# PixHawk_Fire_v1_6.net
KiCad netlist of a schematic drawn in EAGLE
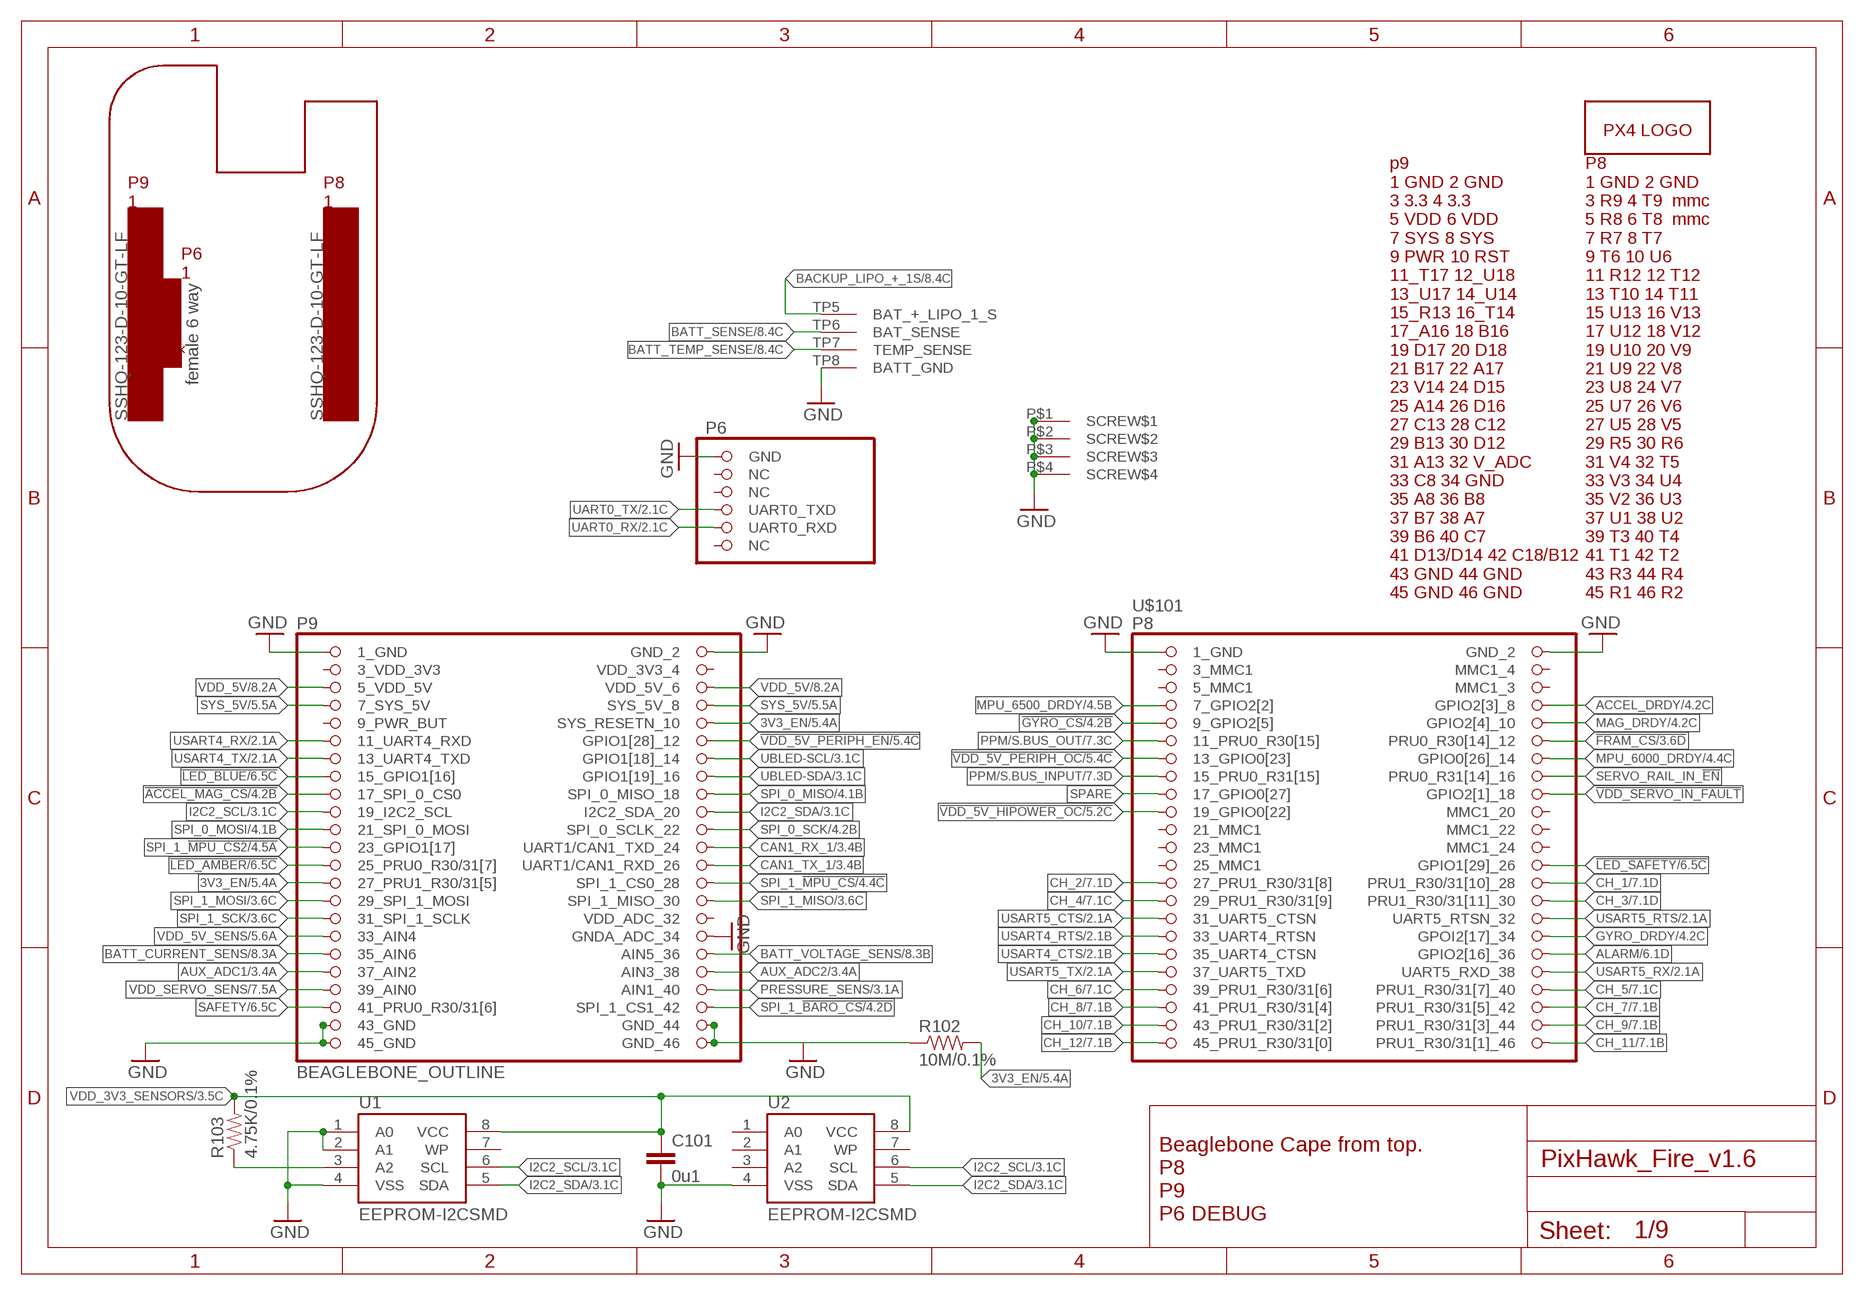
[diagram p0: schematic, sheet 1]
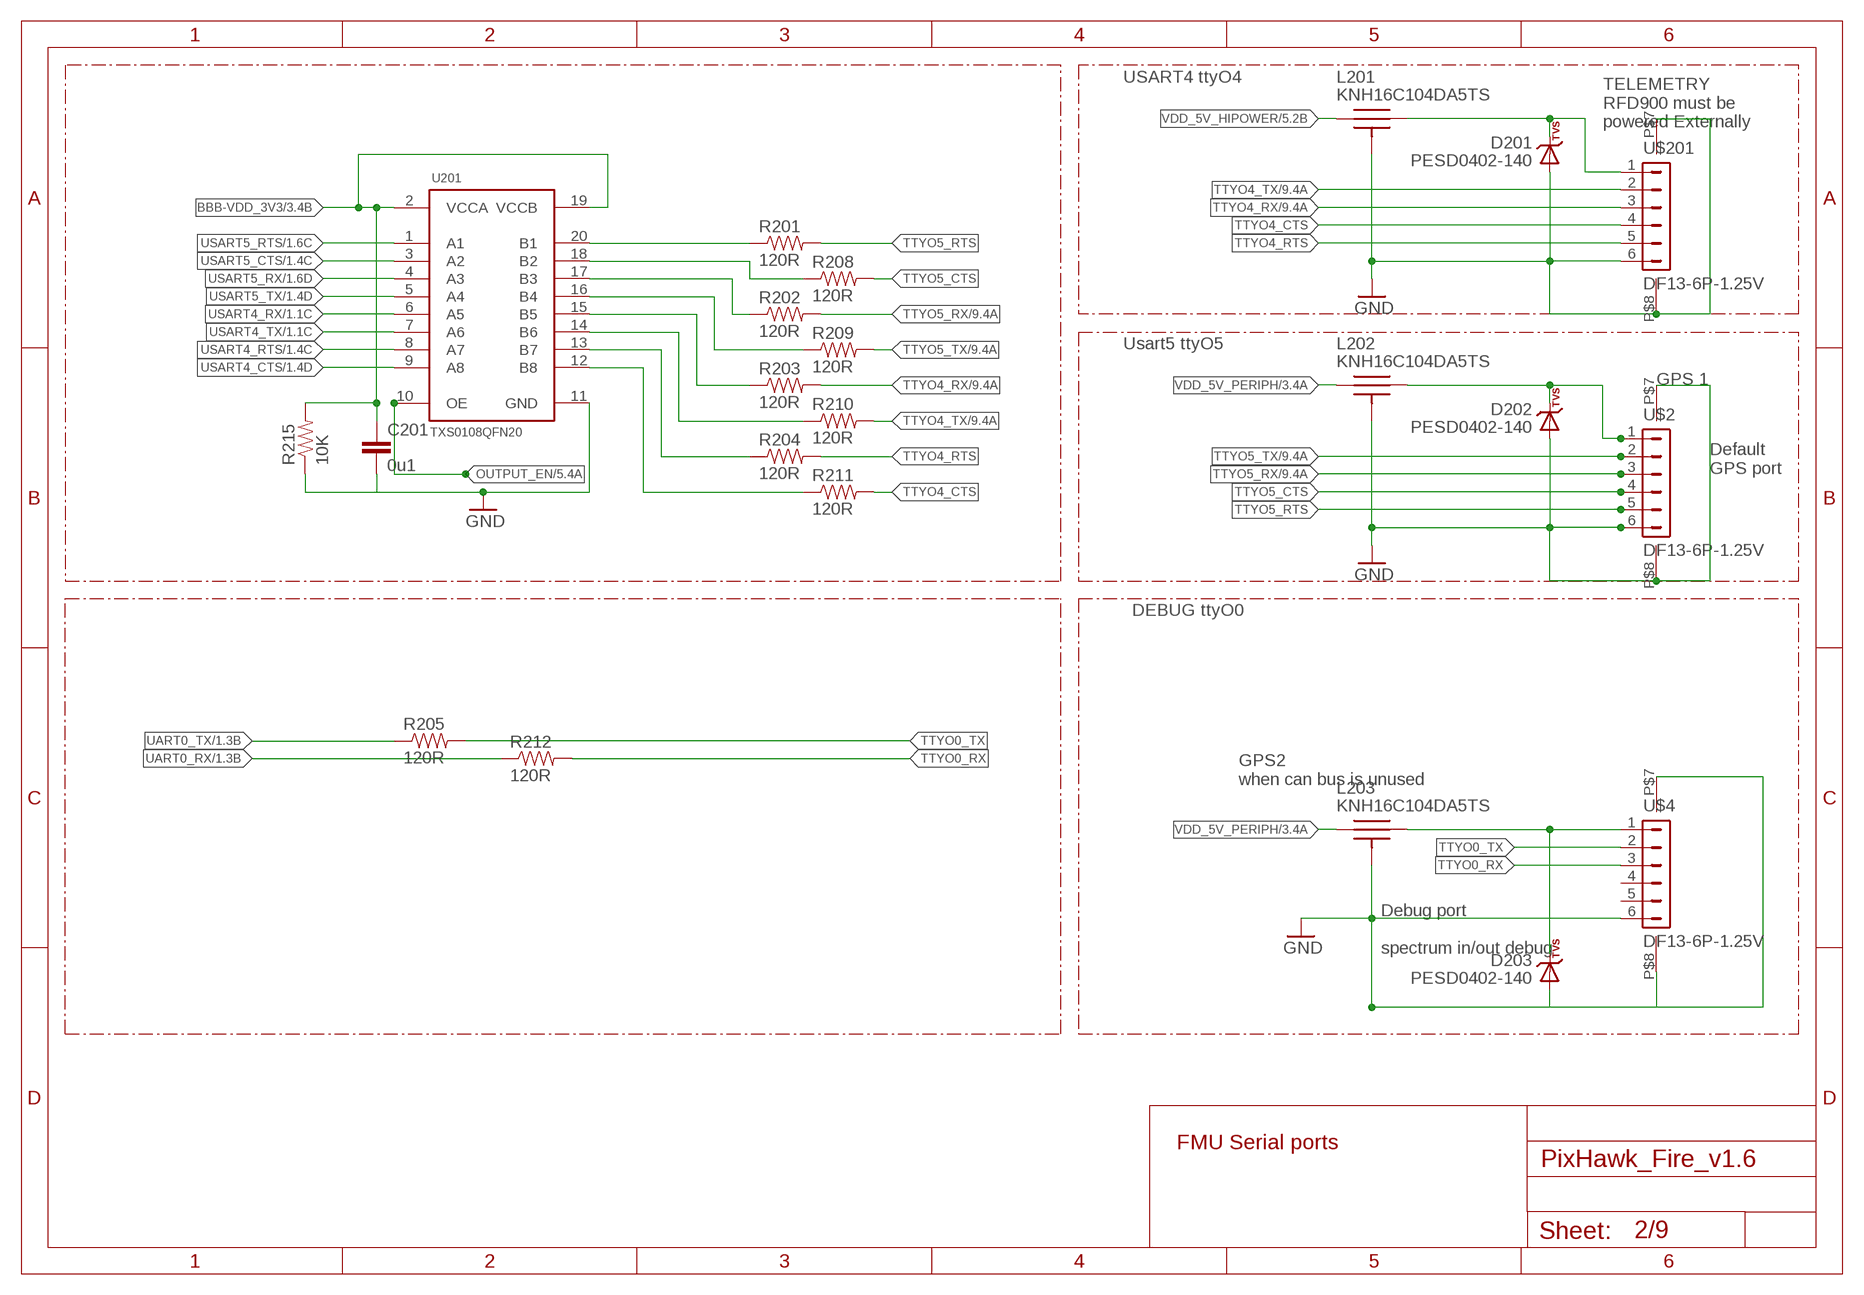
[diagram p1: schematic, sheet 2]
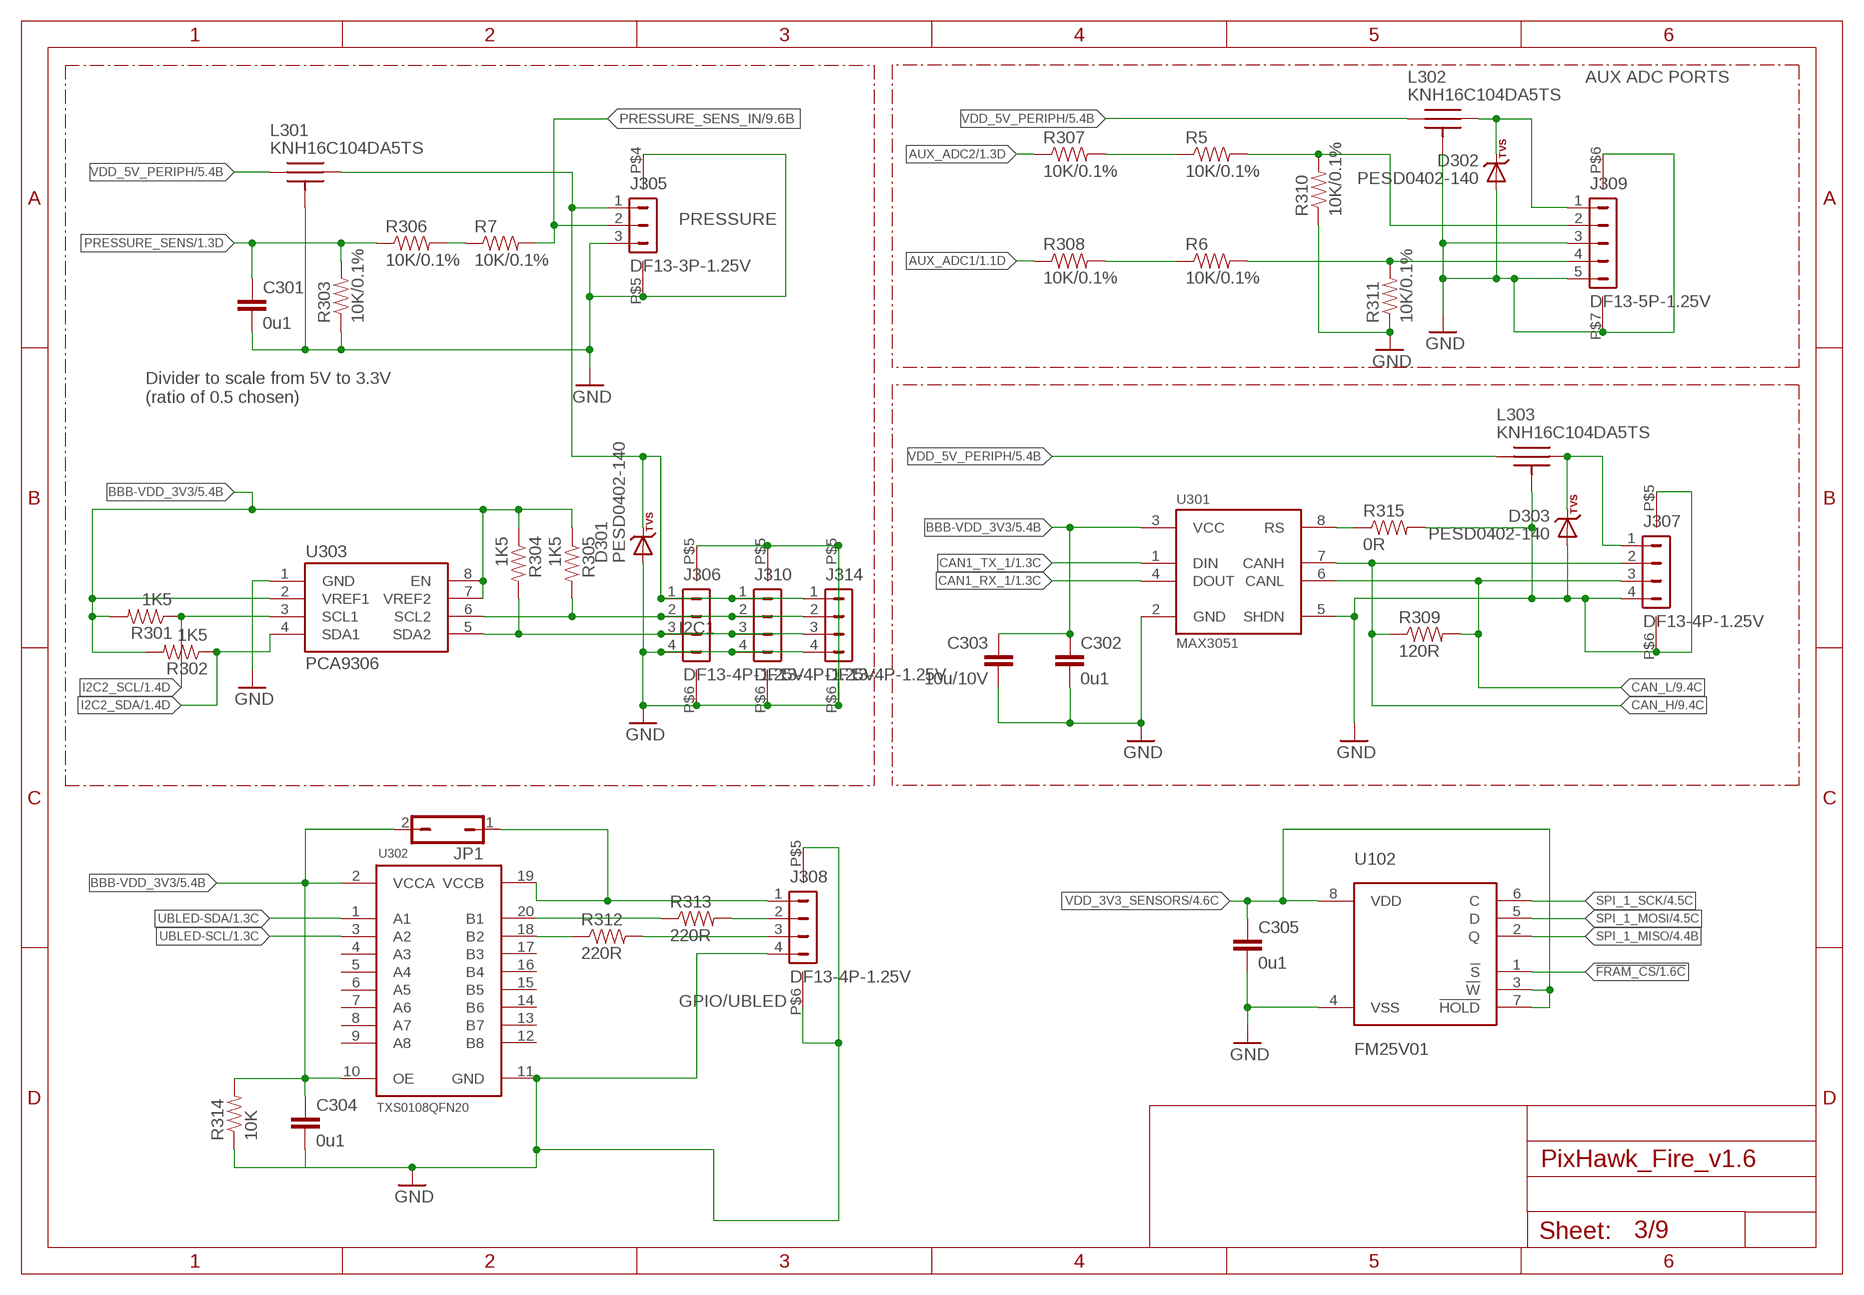
[diagram p2: schematic, sheet 3]
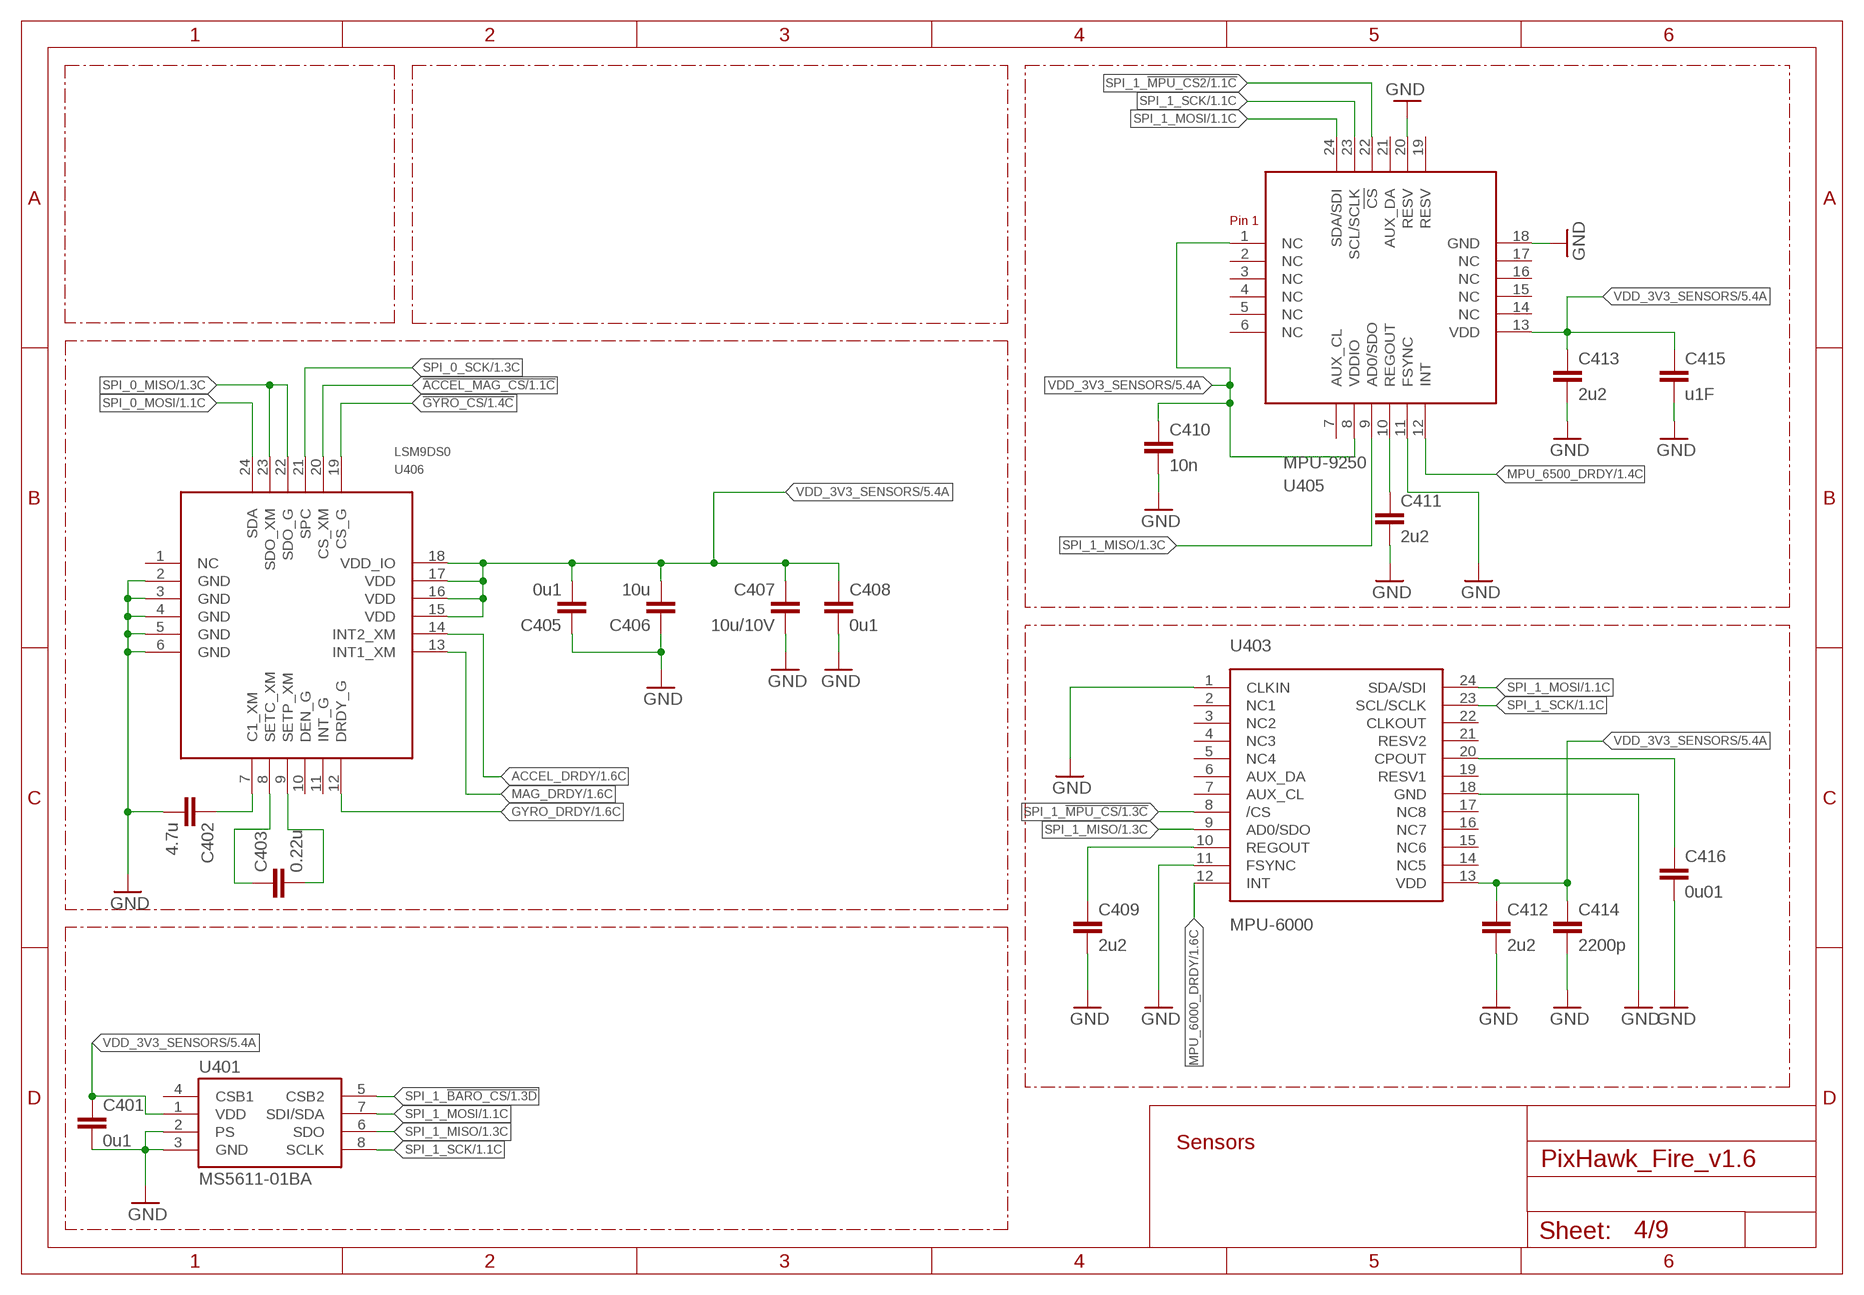
[diagram p3: schematic, sheet 4]
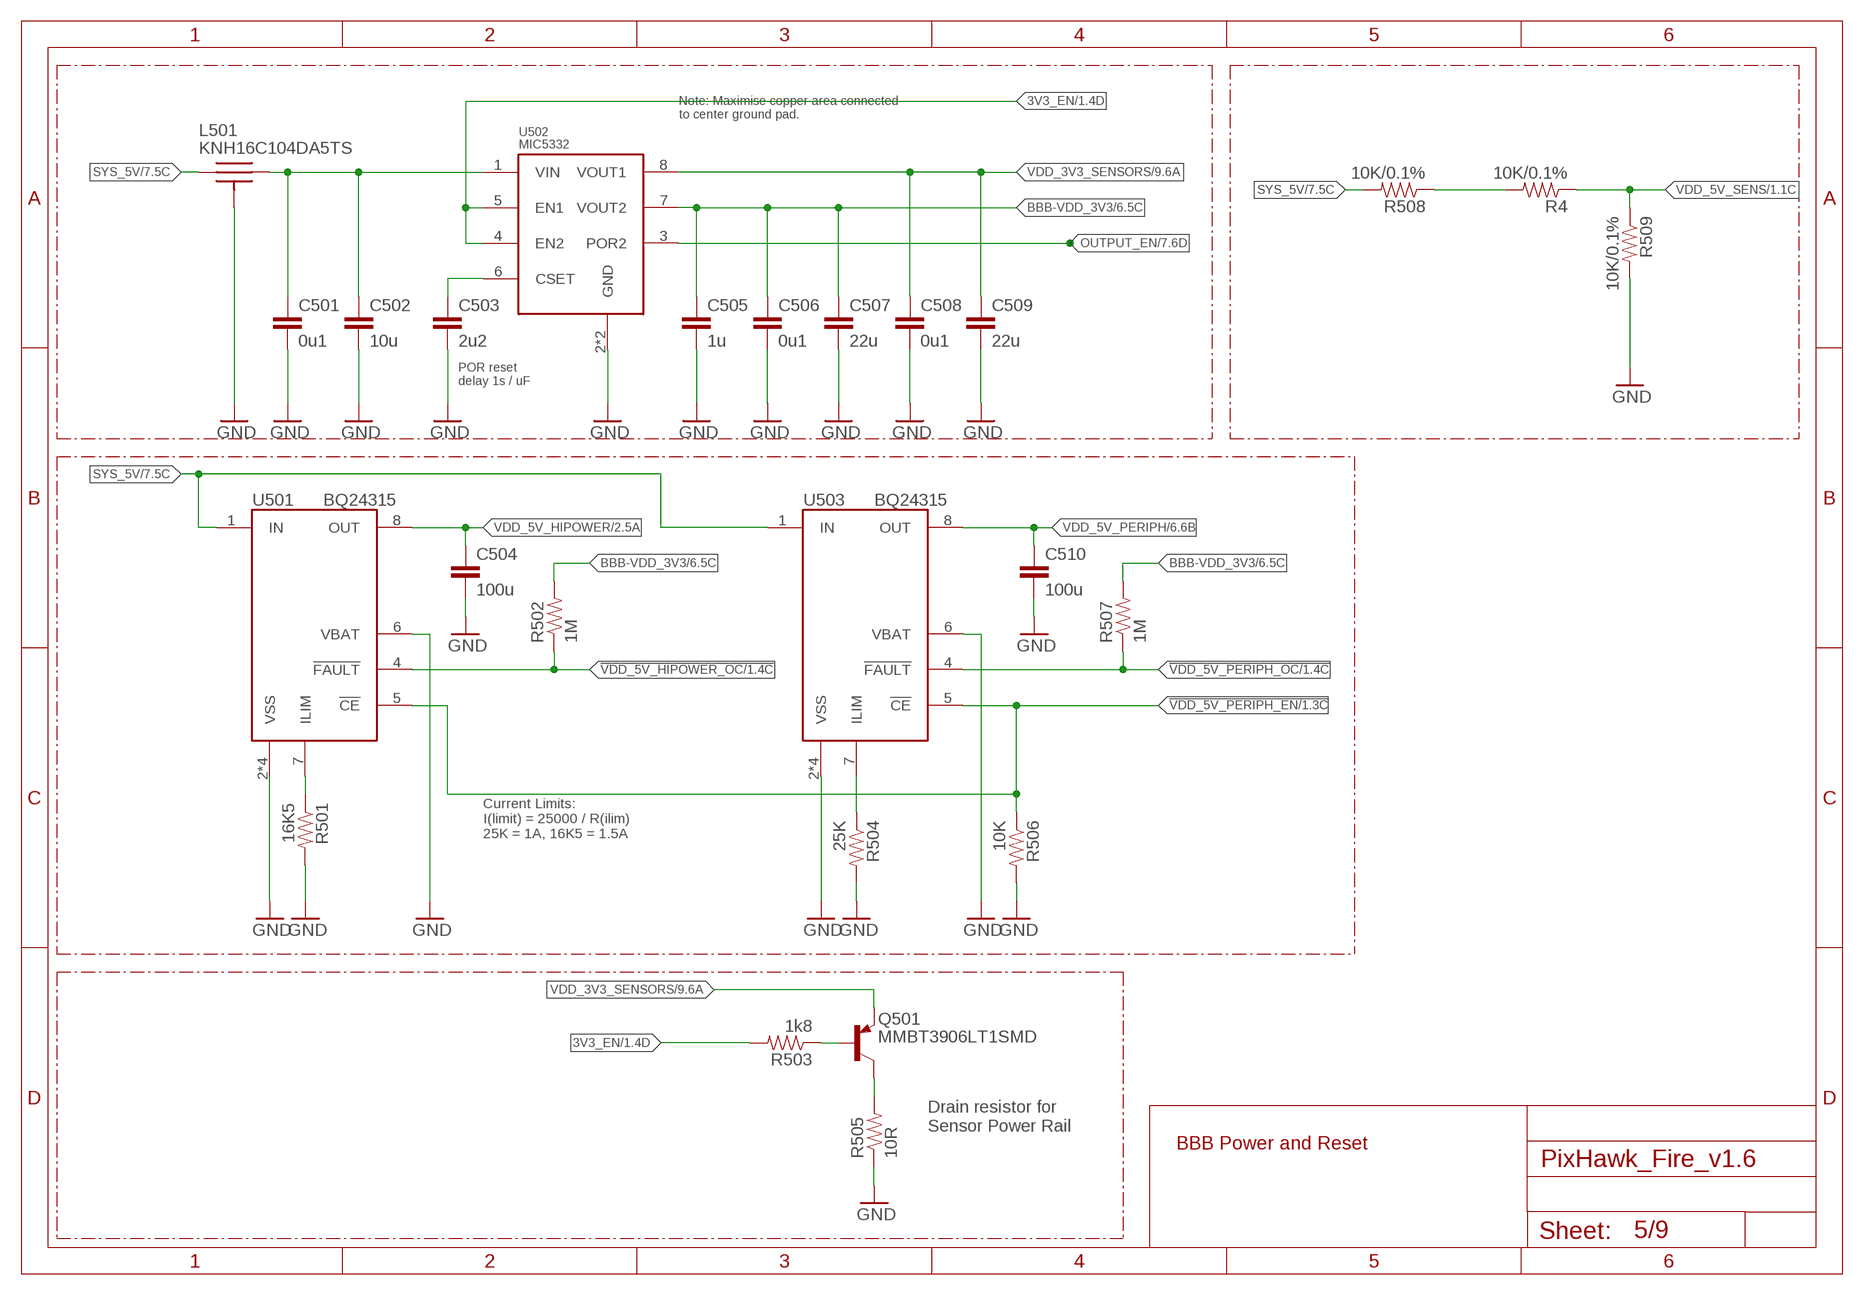
[diagram p4: schematic, sheet 5]
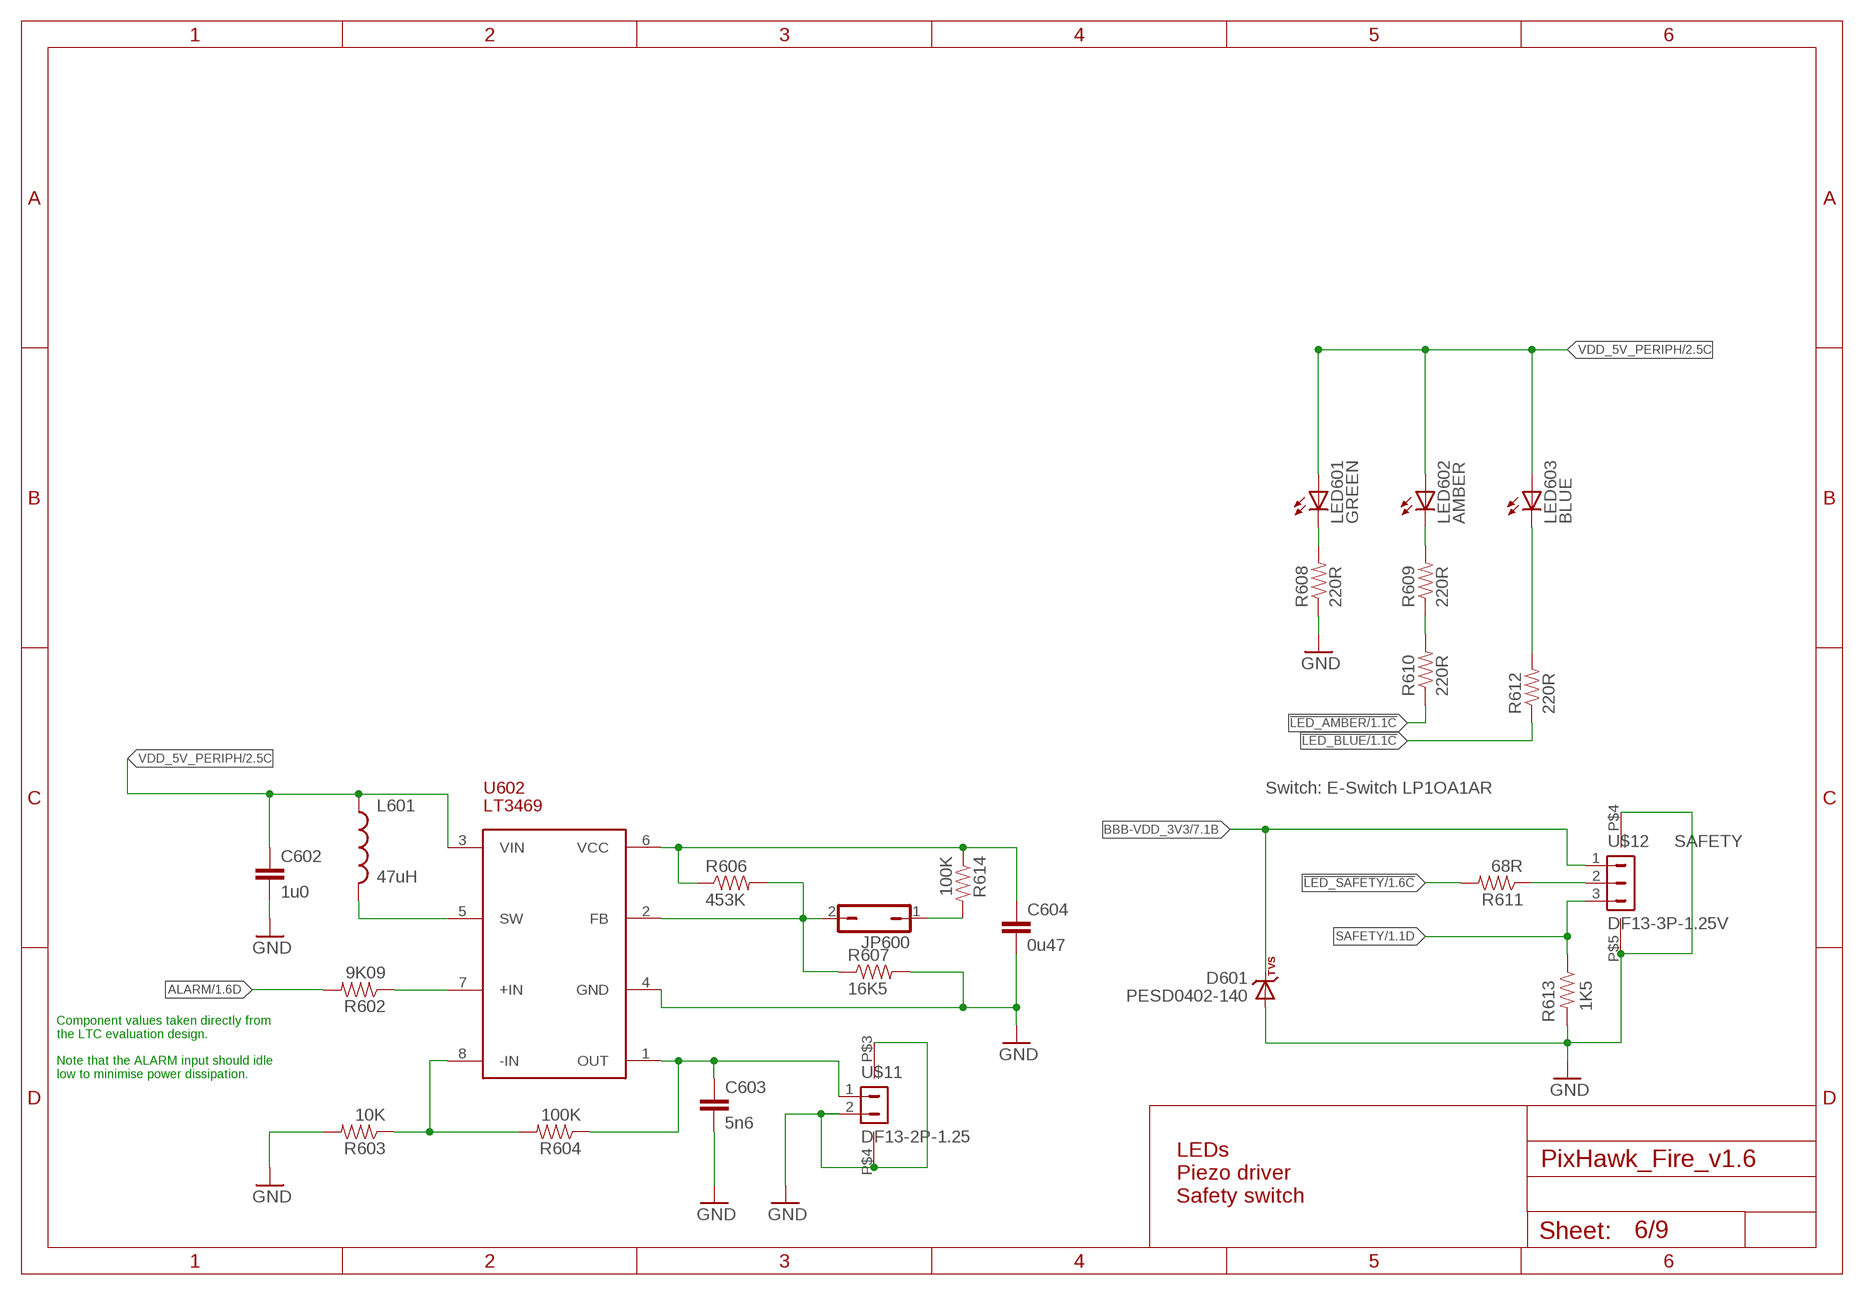
[diagram p5: schematic, sheet 6]
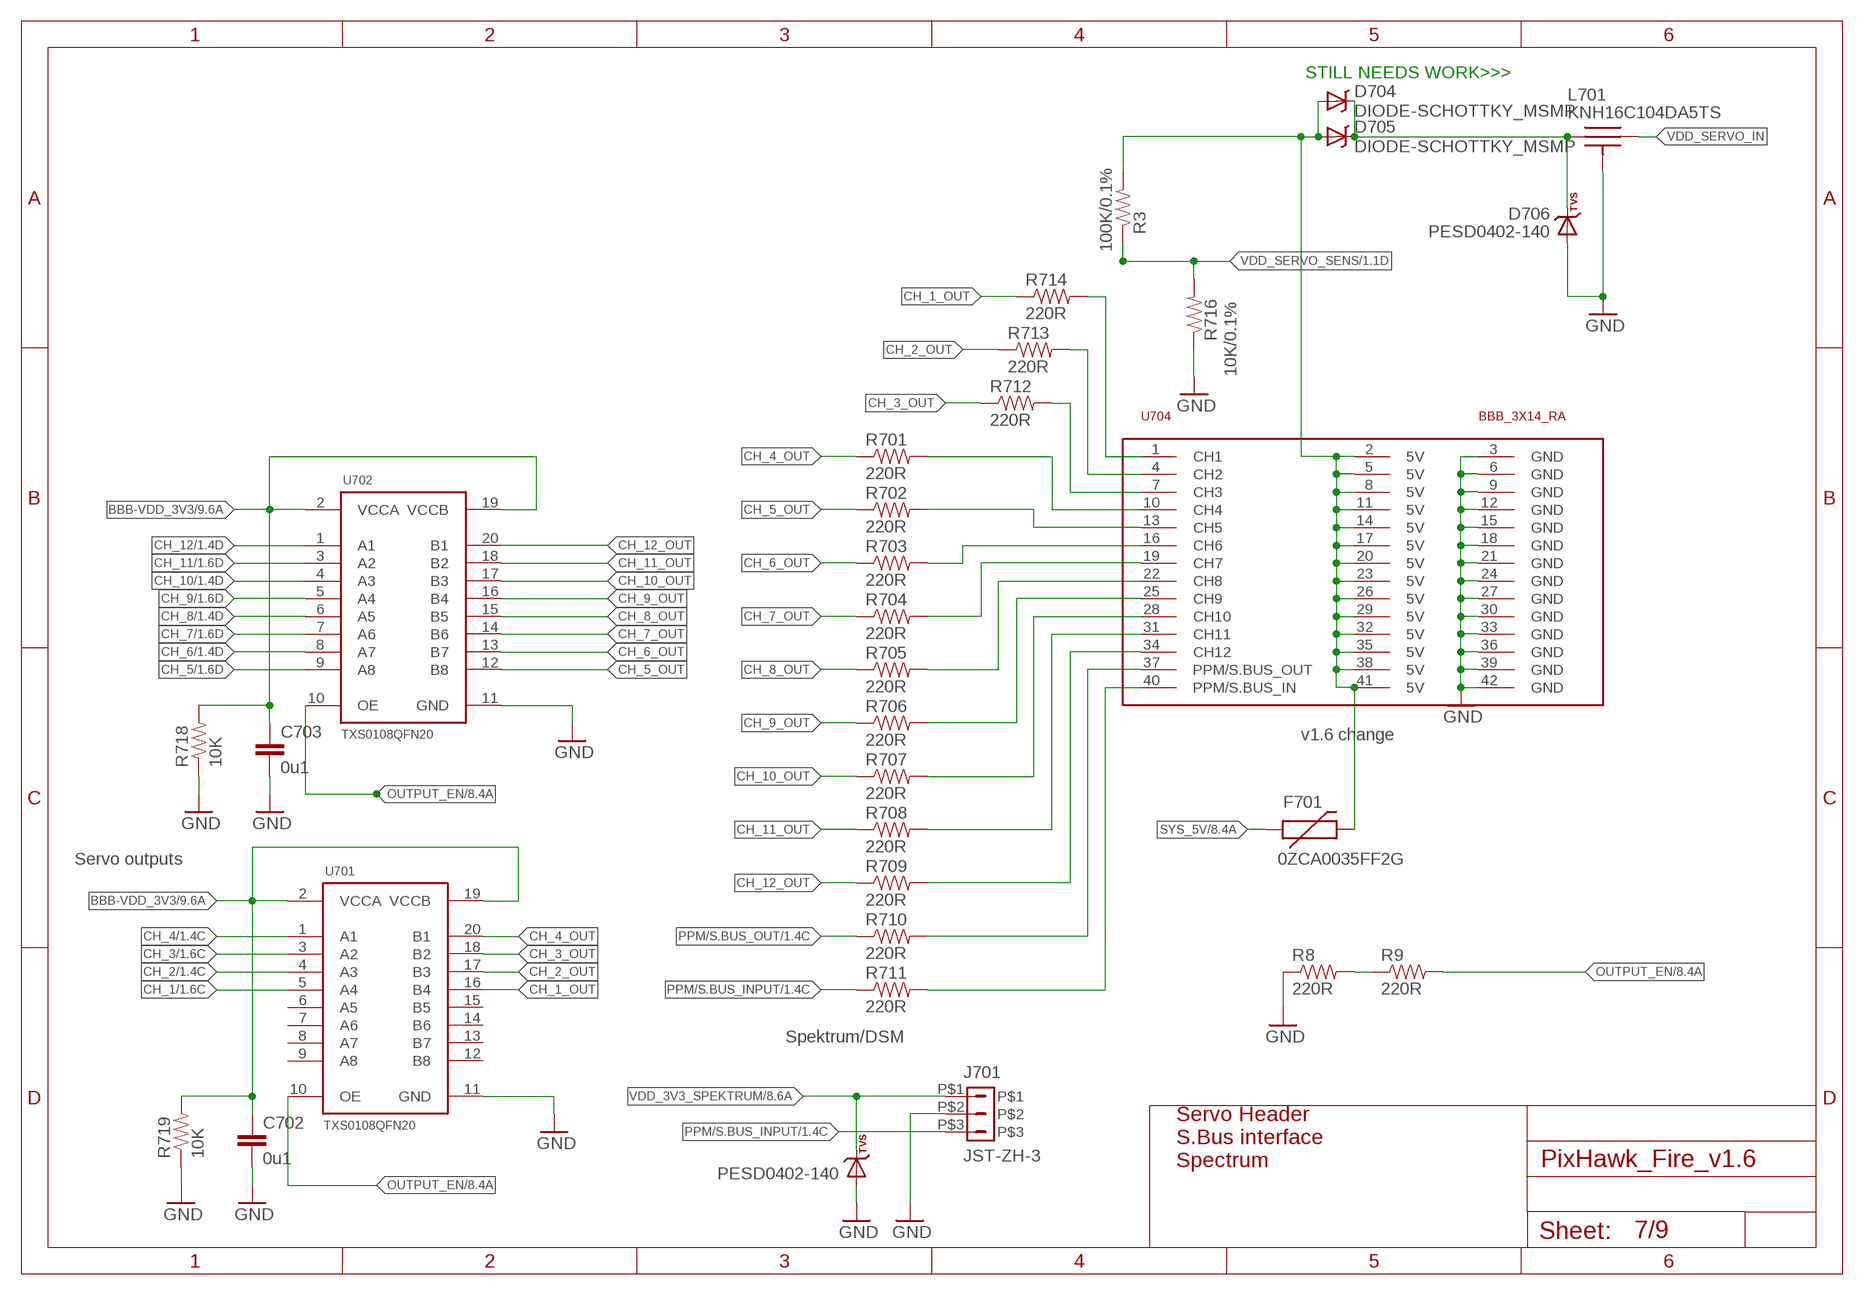
[diagram p6: schematic, sheet 7]
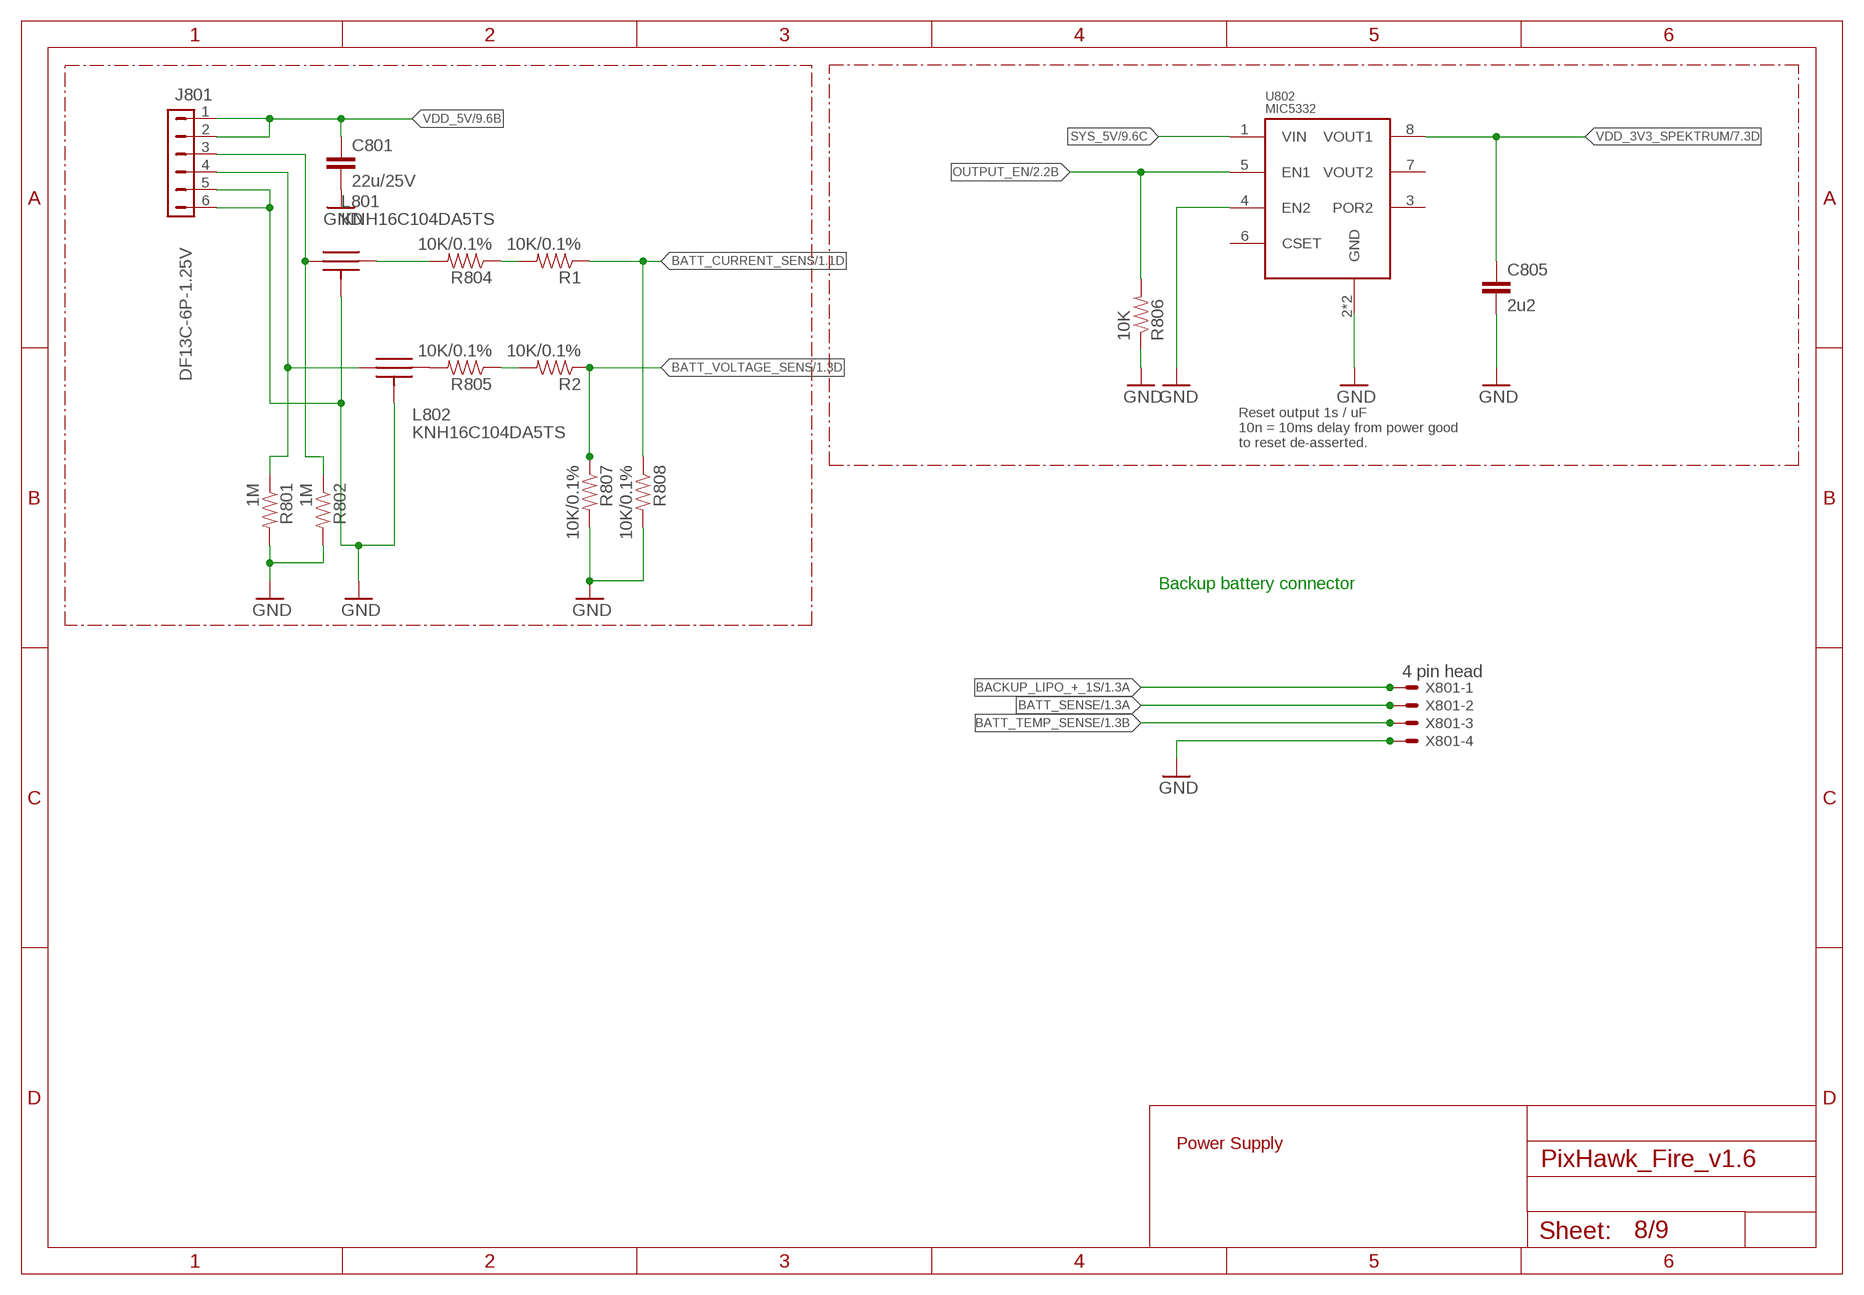
[diagram p7: schematic, sheet 8]
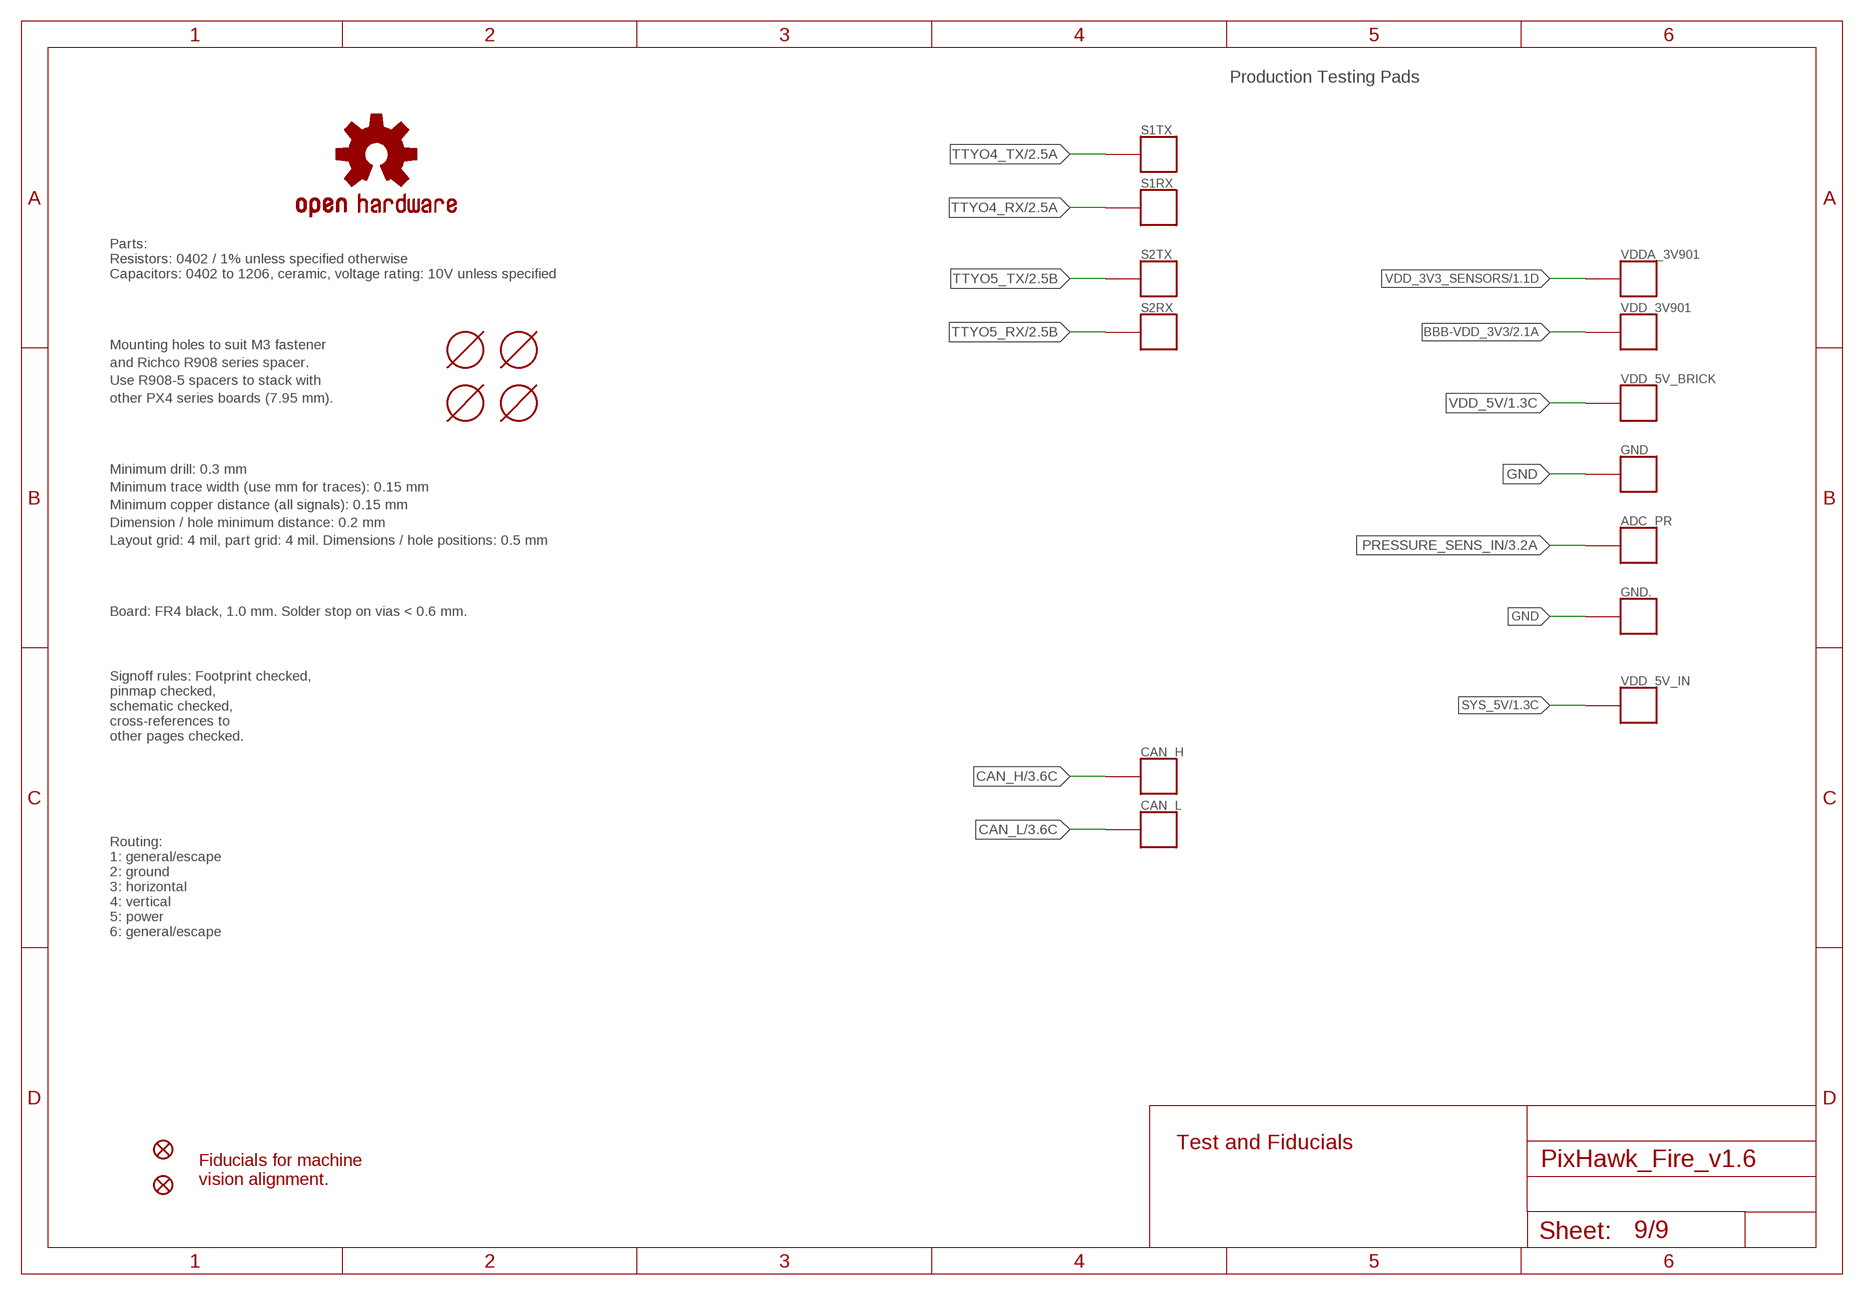
[diagram p8: schematic, sheet 9]

(export (version "E")
  (design (tool "Eeschema 10.0.6"))
  (components
    (comp (ref "C501")
      (value "0u1")
      (footprint "eagle-import:0402-CAP")
      (fields (field (name "PARTNO") "CC0402ZRY5V7BB104"))
      (libsource (lib "eagle-import") (part "CAP0402"))
    )
    (comp (ref "C502")
      (value "10u")
      (footprint "eagle-import:0805-CAP")
      (fields (field (name "PARTNO") "C1608X7S0J106M080AC"))
      (libsource (lib "eagle-import") (part "CAP0805"))
    )
    (comp (ref "C503")
      (value "2u2")
      (footprint "eagle-import:0603-CAP")
      (fields (field (name "PARTNO") "C1608X6S1C225K080AC"))
      (libsource (lib "eagle-import") (part "CAP0603"))
    )
    (comp (ref "C504")
      (value "100u")
      (footprint "eagle-import:1206-CAP")
      (fields (field (name "PARTNO") "C3216X5R1A107M160AC"))
      (libsource (lib "eagle-import") (part "CAP1206"))
    )
    (comp (ref "C505")
      (value "1u")
      (footprint "eagle-import:0603-CAP")
      (fields (field (name "PARTNO") "CC0603ZRY5V7BB105"))
      (libsource (lib "eagle-import") (part "CAP0603"))
    )
    (comp (ref "C506")
      (value "0u1")
      (footprint "eagle-import:0402-CAP")
      (fields (field (name "PARTNO") "CC0402ZRY5V7BB104"))
      (libsource (lib "eagle-import") (part "CAP0402"))
    )
    (comp (ref "C507")
      (value "22u")
      (footprint "eagle-import:0805-CAP")
      (fields (field (name "PARTNO") "CC0805MKX5R5BB226"))
      (libsource (lib "eagle-import") (part "CAP0805"))
    )
    (comp (ref "C508")
      (value "0u1")
      (footprint "eagle-import:0402-CAP")
      (fields (field (name "PARTNO") "CC0402ZRY5V7BB104"))
      (libsource (lib "eagle-import") (part "CAP0402"))
    )
    (comp (ref "C509")
      (value "22u")
      (footprint "eagle-import:0805-CAP")
      (fields (field (name "PARTNO") "CC0805MKX5R5BB226"))
      (libsource (lib "eagle-import") (part "CAP0805"))
    )
    (comp (ref "C510")
      (value "100u")
      (footprint "eagle-import:1206-CAP")
      (fields (field (name "PARTNO") "C3216X5R1A107M160AC"))
      (libsource (lib "eagle-import") (part "CAP1206"))
    )
    (comp (ref "L501")
      (value "KNH16C104DA5TS")
      (footprint "eagle-import:KYOCERA-KNH16-DA")
      (libsource (lib "eagle-import") (part "KNH16C104DA5TS"))
    )
    (comp (ref "Q501")
      (value "MMBT3906LT1SMD")
      (footprint "eagle-import:SOT23-BEC")
      (fields (field (name "PARTNO") "MMBT3906LT1G"))
      (libsource (lib "eagle-import") (part "MMBT3906SMDLT1"))
    )
    (comp (ref "R4")
      (value "10K/0.1%")
      (footprint "eagle-import:0402-RES")
      (fields (field (name "PARTNO") "ERA-2AEB103X"))
      (libsource (lib "eagle-import") (part "RESISTOR0402-RES"))
    )
    (comp (ref "R501")
      (value "16K5")
      (footprint "eagle-import:0402-RES")
      (fields (field (name "PARTNO") "RMCF0402FT16K5"))
      (libsource (lib "eagle-import") (part "RESISTOR0402-RES"))
    )
    (comp (ref "R502")
      (value "1M")
      (footprint "eagle-import:0402-RES")
      (fields (field (name "PARTNO") "MCR01MRTF1004"))
      (libsource (lib "eagle-import") (part "RESISTOR0402-RES"))
    )
    (comp (ref "R503")
      (value "1k8")
      (footprint "eagle-import:0402-RES")
      (fields (field (name "PARTNO") "RC0402FR-071K8L"))
      (libsource (lib "eagle-import") (part "RESISTOR0402-RES"))
    )
    (comp (ref "R504")
      (value "25K")
      (footprint "eagle-import:0402-RES")
      (fields (field (name "PARTNO") "RMCF0402FT25K5"))
      (libsource (lib "eagle-import") (part "RESISTOR0402-RES"))
    )
    (comp (ref "R505")
      (value "10R")
      (footprint "eagle-import:0603-RES")
      (fields (field (name "PARTNO") "RC0402FR-0710RL"))
      (libsource (lib "eagle-import") (part "RESISTOR0603-RES"))
    )
    (comp (ref "R506")
      (value "10K")
      (footprint "eagle-import:0402-RES")
      (fields (field (name "PARTNO") "ERA-2AEB103X"))
      (libsource (lib "eagle-import") (part "RESISTOR0402-RES"))
    )
    (comp (ref "R507")
      (value "1M")
      (footprint "eagle-import:0402-RES")
      (fields (field (name "PARTNO") "MCR01MRTF1004"))
      (libsource (lib "eagle-import") (part "RESISTOR0402-RES"))
    )
    (comp (ref "R508")
      (value "10K/0.1%")
      (footprint "eagle-import:0402-RES")
      (fields (field (name "PARTNO") "ERA-2AEB103X"))
      (libsource (lib "eagle-import") (part "RESISTOR0402-RES"))
    )
    (comp (ref "R509")
      (value "10K/0.1%")
      (footprint "eagle-import:0402-RES")
      (fields (field (name "PARTNO") "ERA-2AEB103X"))
      (libsource (lib "eagle-import") (part "RESISTOR0402-RES"))
    )
    (comp (ref "U501")
      (value "BQ24315")
      (footprint "eagle-import:QFN8-DSG")
      (fields (field (name "PARTNO") "BQ24315DSGR"))
      (libsource (lib "eagle-import") (part "BQ24315"))
    )
    (comp (ref "U502")
      (value "MIC5332")
      (footprint "eagle-import:MLF-8-EPAD")
      (fields (field (name "PARTNO") "MIC5332-SSYMT"))
      (libsource (lib "eagle-import") (part "MIC5332"))
    )
    (comp (ref "U503")
      (value "BQ24315")
      (footprint "eagle-import:QFN8-DSG")
      (fields (field (name "PARTNO") "BQ24315DSGR"))
      (libsource (lib "eagle-import") (part "BQ24315"))
    )
    (comp (ref "C602")
      (value "1u0")
      (footprint "eagle-import:0603-CAP")
      (fields (field (name "PARTNO") "CC0603ZRY5V7BB105"))
      (libsource (lib "eagle-import") (part "CAP0603"))
    )
    (comp (ref "C603")
      (value "5n6")
      (footprint "eagle-import:0402-CAP")
      (fields (field (name "PARTNO") "CC0402KRX7R7BB562"))
      (libsource (lib "eagle-import") (part "CAP0402"))
    )
    (comp (ref "C604")
      (value "0u47")
      (footprint "eagle-import:0402-CAP")
      (fields (field (name "PARTNO") "C1005X5R1C474K050BC"))
      (libsource (lib "eagle-import") (part "CAP0402"))
    )
    (comp (ref "D601")
      (value "PESD0402-140")
      (footprint "eagle-import:0402-TVS")
      (libsource (lib "eagle-import") (part "DIODE-TVS"))
    )
    (comp (ref "JP600")
      (value "JP1Q")
      (footprint "eagle-import:JP1")
      (fields (field (name "PARTNO") "1-87215-0"))
      (libsource (lib "eagle-import") (part "JP1Q"))
    )
    (comp (ref "L601")
      (value "47uH")
      (footprint "eagle-import:0805-IND")
      (fields (field (name "PARTNO") "MLZ2012M470W"))
      (libsource (lib "eagle-import") (part "INDUCTOR0805"))
    )
    (comp (ref "LED601")
      (value "GREEN")
      (footprint "eagle-import:0603-LED")
      (fields (field (name "PARTNO") "APTD1608CGCK"))
      (libsource (lib "eagle-import") (part "LED0603"))
    )
    (comp (ref "LED602")
      (value "AMBER")
      (footprint "eagle-import:0603-LED")
      (fields (field (name "PARTNO") "APTD1608SECK"))
      (libsource (lib "eagle-import") (part "LED0603"))
    )
    (comp (ref "LED603")
      (value "BLUE")
      (footprint "eagle-import:0603-LED")
      (fields (field (name "PARTNO") "APTD1608QBC/D"))
      (libsource (lib "eagle-import") (part "LED0603"))
    )
    (comp (ref "R602")
      (value "9K09")
      (footprint "eagle-import:0402-RES")
      (fields (field (name "PARTNO") "RMCF0402FT9K09"))
      (libsource (lib "eagle-import") (part "RESISTOR0402-RES"))
    )
    (comp (ref "R603")
      (value "10K")
      (footprint "eagle-import:0402-RES")
      (fields (field (name "PARTNO") "ERA-2AEB103X"))
      (libsource (lib "eagle-import") (part "RESISTOR0402-RES"))
    )
    (comp (ref "R604")
      (value "100K")
      (footprint "eagle-import:0402-RES")
      (fields (field (name "PARTNO") "RC0402FR-07100KL"))
      (libsource (lib "eagle-import") (part "RESISTOR0402-RES"))
    )
    (comp (ref "R606")
      (value "453K")
      (footprint "eagle-import:0402-RES")
      (fields (field (name "PARTNO") "RMCF0402FT453K"))
      (libsource (lib "eagle-import") (part "RESISTOR0402-RES"))
    )
    (comp (ref "R607")
      (value "16K5")
      (footprint "eagle-import:0402-RES")
      (fields (field (name "PARTNO") "RMCF0402FT16K5"))
      (libsource (lib "eagle-import") (part "RESISTOR0402-RES"))
    )
    (comp (ref "R608")
      (value "220R")
      (footprint "eagle-import:0402-RES")
      (fields (field (name "PARTNO") "RC0402FR-07220RL"))
      (libsource (lib "eagle-import") (part "RESISTOR0402-RES"))
    )
    (comp (ref "R609")
      (value "220R")
      (footprint "eagle-import:0402-RES")
      (fields (field (name "PARTNO") "RC0402FR-07220RL"))
      (libsource (lib "eagle-import") (part "RESISTOR0402-RES"))
    )
    (comp (ref "R610")
      (value "220R")
      (footprint "eagle-import:0402-RES")
      (fields (field (name "PARTNO") "RC0402FR-07220RL"))
      (libsource (lib "eagle-import") (part "RESISTOR0402-RES"))
    )
    (comp (ref "R611")
      (value "68R")
      (footprint "eagle-import:0402-RES")
      (fields (field (name "PARTNO") "RC0402FR-0768RL"))
      (libsource (lib "eagle-import") (part "RESISTOR0402-RES"))
    )
    (comp (ref "R612")
      (value "220R")
      (footprint "eagle-import:0402-RES")
      (fields (field (name "PARTNO") "RC0402FR-07220RL"))
      (libsource (lib "eagle-import") (part "RESISTOR0402-RES"))
    )
    (comp (ref "R613")
      (value "1K5")
      (footprint "eagle-import:0402-RES")
      (fields (field (name "PARTNO") "RC0402FR-071K5L"))
      (libsource (lib "eagle-import") (part "RESISTOR0402-RES"))
    )
    (comp (ref "R614")
      (value "100K")
      (footprint "eagle-import:0402-RES")
      (fields (field (name "PARTNO") "RC0402FR-07100KL"))
      (libsource (lib "eagle-import") (part "RESISTOR0402-RES"))
    )
    (comp (ref "U$11")
      (value "DF13-2P-1.25")
      (footprint "eagle-import:DF13C-2P-1.25V")
      (fields (field (name "PARTNO") "DF13C-2P-1.25V(20)"))
      (libsource (lib "eagle-import") (part "DF13-2P-1.25"))
    )
    (comp (ref "U$12")
      (value "DF13-3P-1.25V")
      (footprint "eagle-import:DF13C-3P-1.25V")
      (fields (field (name "PARTNO") "DF13C-3P-1.25V(20)"))
      (libsource (lib "eagle-import") (part "DF13-3P-1.25V"))
    )
    (comp (ref "U602")
      (value "LT3469")
      (footprint "eagle-import:SOT23-8")
      (fields (field (name "PARTNO") "LT3469ETS8"))
      (libsource (lib "eagle-import") (part "LT3469"))
    )
    (comp (ref "C101")
      (value "0u1")
      (footprint "eagle-import:0402-CAP")
      (fields (field (name "PARTNO") "CC0402ZRY5V7BB104"))
      (libsource (lib "eagle-import") (part "CAP0402"))
    )
    (comp (ref "R102")
      (value "10M/0.1%")
      (footprint "eagle-import:0402-RES")
      (fields (field (name "PARTNO") "RC0402FR-0710ML"))
      (libsource (lib "eagle-import") (part "RESISTOR0402-RES"))
    )
    (comp (ref "R103")
      (value "4.75K/0.1%")
      (footprint "eagle-import:0402-RES")
      (fields (field (name "PARTNO") "RC0402FR-074K75L"))
      (libsource (lib "eagle-import") (part "RESISTOR0402-RES"))
    )
    (comp (ref "U$1")
      (value "PX4-LOGO")
      (footprint "eagle-import:PIXHAWK-FIRE-LOGO-30")
      (libsource (lib "eagle-import") (part "PX4-LOGO"))
    )
    (comp (ref "U$101")
      (value "BEAGLEBONE_OUTLINE")
      (footprint "eagle-import:BEAGLEBONE_SHIELD")
      (libsource (lib "eagle-import") (part "BEAGLEBONE_OUTLINE"))
    )
    (comp (ref "U1")
      (value "EEPROM-I2CSMD")
      (footprint "eagle-import:SO08")
      (fields (field (name "PARTNO") "AT24CS32-SSHM"))
      (libsource (lib "eagle-import") (part "EEPROM-I2CSMD"))
    )
    (comp (ref "U2")
      (value "EEPROM-I2CSMD")
      (footprint "eagle-import:SO08")
      (fields (field (name "PARTNO") "ATSHA204-SH-DA-TTR-ND"))
      (libsource (lib "eagle-import") (part "EEPROM-I2CSMD"))
    )
    (comp (ref "C401")
      (value "0u1")
      (footprint "eagle-import:0402-CAP")
      (fields (field (name "PARTNO") "CC0402ZRY5V7BB104"))
      (libsource (lib "eagle-import") (part "CAP0402"))
    )
    (comp (ref "C402")
      (value "4.7u")
      (footprint "eagle-import:0603-CAP")
      (fields (field (name "PARTNO") "C1608X7S1A475K080AC"))
      (libsource (lib "eagle-import") (part "CAP0603"))
    )
    (comp (ref "C403")
      (value "0.22u")
      (footprint "eagle-import:0603-CAP")
      (fields (field (name "PARTNO") "CL10B224JP8NNNC"))
      (libsource (lib "eagle-import") (part "CAP0603"))
    )
    (comp (ref "C405")
      (value "0u1")
      (footprint "eagle-import:0603-CAP")
      (fields (field (name "PARTNO") "CL10B104JO8NNNC"))
      (libsource (lib "eagle-import") (part "CAP0603"))
    )
    (comp (ref "C406")
      (value "10u")
      (footprint "eagle-import:0603-CAP")
      (fields (field (name "PARTNO") "C1608X7S0J106M080AC"))
      (libsource (lib "eagle-import") (part "CAP0603"))
    )
    (comp (ref "C407")
      (value "10u/10V")
      (footprint "eagle-import:0805-CAP")
      (fields (field (name "PARTNO") "CC0805ZKY5V6BB106"))
      (libsource (lib "eagle-import") (part "CAP0805"))
    )
    (comp (ref "C408")
      (value "0u1")
      (footprint "eagle-import:0402-CAP")
      (fields (field (name "PARTNO") "CC0402ZRY5V7BB104"))
      (libsource (lib "eagle-import") (part "CAP0402"))
    )
    (comp (ref "C409")
      (value "2u2")
      (footprint "eagle-import:0603-CAP")
      (fields (field (name "PARTNO") "C1608X6S1C225K080AC"))
      (libsource (lib "eagle-import") (part "CAP0603"))
    )
    (comp (ref "C410")
      (value "10n")
      (footprint "eagle-import:0603-CAP")
      (fields (field (name "PARTNO") "C0603C103J5RAC7411"))
      (libsource (lib "eagle-import") (part "CAP0603"))
    )
    (comp (ref "C411")
      (value "2u2")
      (footprint "eagle-import:0603-CAP")
      (fields (field (name "PARTNO") "C1608X6S1C225K080AC"))
      (libsource (lib "eagle-import") (part "CAP0603"))
    )
    (comp (ref "C412")
      (value "2u2")
      (footprint "eagle-import:0603-CAP")
      (fields (field (name "PARTNO") "CGA3E1X7R0J225K080AC"))
      (libsource (lib "eagle-import") (part "CAP0603"))
    )
    (comp (ref "C413")
      (value "2u2")
      (footprint "eagle-import:0603-CAP")
      (libsource (lib "eagle-import") (part "CAP0603"))
    )
    (comp (ref "C414")
      (value "2200p")
      (footprint "eagle-import:0402-CAP")
      (fields (field (name "PARTNO") "C0603C222J5RACTU"))
      (libsource (lib "eagle-import") (part "CAP0402"))
    )
    (comp (ref "C415")
      (value "u1F")
      (footprint "eagle-import:0402-CAP")
      (fields (field (name "PARTNO") "CC0402ZRY5V7BB104"))
      (libsource (lib "eagle-import") (part "CAP0402"))
    )
    (comp (ref "C416")
      (value "0u01")
      (footprint "eagle-import:0603-CAP")
      (fields (field (name "PARTNO") "06033C103JAT2A"))
      (libsource (lib "eagle-import") (part "CAP0603"))
    )
    (comp (ref "U401")
      (value "MS5611-01BA")
      (footprint "eagle-import:MS5611-01BA")
      (libsource (lib "eagle-import") (part "MS5611-01BA"))
    )
    (comp (ref "U403")
      (value "MPU-6000")
      (footprint "eagle-import:QFN-24")
      (libsource (lib "eagle-import") (part "MPU-6000"))
    )
    (comp (ref "U405")
      (value "MPU-9250")
      (footprint "eagle-import:MPU-6500")
      (libsource (lib "eagle-import") (part "MPU-6500"))
    )
    (comp (ref "U406")
      (value "LSM9DS0")
      (footprint "eagle-import:LGA-24")
      (fields (field (name "PARTNO") "LSM9DS0TR"))
      (libsource (lib "eagle-import") (part "LSM9DS0"))
    )
    (comp (ref "C201")
      (value "0u1")
      (footprint "eagle-import:0402-CAP")
      (fields (field (name "PARTNO") "CC0402ZRY5V7BB104"))
      (libsource (lib "eagle-import") (part "CAP0402"))
    )
    (comp (ref "D201")
      (value "PESD0402-140")
      (footprint "eagle-import:0402-TVS")
      (libsource (lib "eagle-import") (part "DIODE-TVS"))
    )
    (comp (ref "D202")
      (value "PESD0402-140")
      (footprint "eagle-import:0402-TVS")
      (libsource (lib "eagle-import") (part "DIODE-TVS"))
    )
    (comp (ref "D203")
      (value "PESD0402-140")
      (footprint "eagle-import:0402-TVS")
      (libsource (lib "eagle-import") (part "DIODE-TVS"))
    )
    (comp (ref "L201")
      (value "KNH16C104DA5TS")
      (footprint "eagle-import:KYOCERA-KNH16-DA")
      (libsource (lib "eagle-import") (part "KNH16C104DA5TS"))
    )
    (comp (ref "L202")
      (value "KNH16C104DA5TS")
      (footprint "eagle-import:KYOCERA-KNH16-DA")
      (libsource (lib "eagle-import") (part "KNH16C104DA5TS"))
    )
    (comp (ref "L203")
      (value "KNH16C104DA5TS")
      (footprint "eagle-import:KYOCERA-KNH16-DA")
      (libsource (lib "eagle-import") (part "KNH16C104DA5TS"))
    )
    (comp (ref "R201")
      (value "120R")
      (footprint "eagle-import:0402-RES")
      (fields (field (name "PARTNO") "RC0402FR-07120RL"))
      (libsource (lib "eagle-import") (part "RESISTOR0402-RES"))
    )
    (comp (ref "R202")
      (value "120R")
      (footprint "eagle-import:0402-RES")
      (fields (field (name "PARTNO") "RC0402FR-07120RL"))
      (libsource (lib "eagle-import") (part "RESISTOR0402-RES"))
    )
    (comp (ref "R203")
      (value "120R")
      (footprint "eagle-import:0402-RES")
      (fields (field (name "PARTNO") "RC0402FR-07120RL"))
      (libsource (lib "eagle-import") (part "RESISTOR0402-RES"))
    )
    (comp (ref "R204")
      (value "120R")
      (footprint "eagle-import:0402-RES")
      (fields (field (name "PARTNO") "RC0402FR-07120RL"))
      (libsource (lib "eagle-import") (part "RESISTOR0402-RES"))
    )
    (comp (ref "R205")
      (value "120R")
      (footprint "eagle-import:0402-RES")
      (fields (field (name "PARTNO") "RC0402FR-07120RL"))
      (libsource (lib "eagle-import") (part "RESISTOR0402-RES"))
    )
    (comp (ref "R208")
      (value "120R")
      (footprint "eagle-import:0402-RES")
      (fields (field (name "PARTNO") "RC0402FR-07120RL"))
      (libsource (lib "eagle-import") (part "RESISTOR0402-RES"))
    )
    (comp (ref "R209")
      (value "120R")
      (footprint "eagle-import:0402-RES")
      (fields (field (name "PARTNO") "RC0402FR-07120RL"))
      (libsource (lib "eagle-import") (part "RESISTOR0402-RES"))
    )
    (comp (ref "R210")
      (value "120R")
      (footprint "eagle-import:0402-RES")
      (fields (field (name "PARTNO") "RC0402FR-07120RL"))
      (libsource (lib "eagle-import") (part "RESISTOR0402-RES"))
    )
    (comp (ref "R211")
      (value "120R")
      (footprint "eagle-import:0402-RES")
      (fields (field (name "PARTNO") "RC0402FR-07120RL"))
      (libsource (lib "eagle-import") (part "RESISTOR0402-RES"))
    )
    (comp (ref "R212")
      (value "120R")
      (footprint "eagle-import:0402-RES")
      (fields (field (name "PARTNO") "RC0402FR-07120RL"))
      (libsource (lib "eagle-import") (part "RESISTOR0402-RES"))
    )
    (comp (ref "R215")
      (value "10K")
      (footprint "eagle-import:0402-RES")
      (fields (field (name "PARTNO") "ERA-2AEB103X"))
      (libsource (lib "eagle-import") (part "RESISTOR0402-RES"))
    )
    (comp (ref "U$2")
      (value "DF13-6P-1.25V")
      (footprint "eagle-import:DF13C-6P-1.25V")
      (fields (field (name "PARTNO") "DF13C-6P-1.25V(20)"))
      (libsource (lib "eagle-import") (part "pxf_DF13-6P-1.25V"))
    )
    (comp (ref "U$4")
      (value "DF13-6P-1.25V")
      (footprint "eagle-import:DF13C-6P-1.25V")
      (fields (field (name "PARTNO") "DF13C-6P-1.25V(20)"))
      (libsource (lib "eagle-import") (part "pxf_DF13-6P-1.25V"))
    )
    (comp (ref "U$201")
      (value "DF13-6P-1.25V")
      (footprint "eagle-import:DF13C-6P-1.25V")
      (fields (field (name "PARTNO") "DF13C-6P-1.25V(20)"))
      (libsource (lib "eagle-import") (part "pxf_DF13-6P-1.25V"))
    )
    (comp (ref "U201")
      (value "TXS0108QFN20")
      (footprint "eagle-import:QFN20-RGY")
      (fields (field (name "PARTNO") "TXS0108ERGYR"))
      (libsource (lib "eagle-import") (part "TXS0108QFN20"))
    )
    (comp (ref "ADC_PR")
      (value "PAD.04")
      (footprint "eagle-import:PAD.04X.04")
      (libsource (lib "eagle-import") (part "PAD.04"))
    )
    (comp (ref "CAN_H")
      (value "PAD.04")
      (footprint "eagle-import:PAD.04X.04")
      (libsource (lib "eagle-import") (part "PAD.04"))
    )
    (comp (ref "CAN_L")
      (value "PAD.04")
      (footprint "eagle-import:PAD.04X.04")
      (libsource (lib "eagle-import") (part "PAD.04"))
    )
    (comp (ref "GND")
      (value "PAD.04")
      (footprint "eagle-import:PAD.04X.04")
      (libsource (lib "eagle-import") (part "PAD.04"))
    )
    (comp (ref "GND.")
      (value "PAD.04")
      (footprint "eagle-import:PAD.04X.04")
      (libsource (lib "eagle-import") (part "PAD.04"))
    )
    (comp (ref "JP901")
      (value "FIDUCIAL1.5X3")
      (footprint "eagle-import:FIDUCIAL-1.5X3")
      (libsource (lib "eagle-import") (part "FIDUCIAL1.5X3"))
    )
    (comp (ref "JP902")
      (value "FIDUCIAL1.5X3")
      (footprint "eagle-import:FIDUCIAL-1.5X3")
      (libsource (lib "eagle-import") (part "FIDUCIAL1.5X3"))
    )
    (comp (ref "M3_MOUNT901")
      (value "MOUNT-HOLE3.1MM")
      (footprint "eagle-import:MOUNT-HOLE3.1")
      (libsource (lib "eagle-import") (part "MOUNT-HOLE3.1MM"))
    )
    (comp (ref "M3_MOUNT902")
      (value "MOUNT-HOLE3.1MM")
      (footprint "eagle-import:MOUNT-HOLE3.1")
      (libsource (lib "eagle-import") (part "MOUNT-HOLE3.1MM"))
    )
    (comp (ref "M3_MOUNT903")
      (value "MOUNT-HOLE3.1MM")
      (footprint "eagle-import:MOUNT-HOLE3.1")
      (libsource (lib "eagle-import") (part "MOUNT-HOLE3.1MM"))
    )
    (comp (ref "M3_MOUNT904")
      (value "MOUNT-HOLE3.1MM")
      (footprint "eagle-import:MOUNT-HOLE3.1")
      (libsource (lib "eagle-import") (part "MOUNT-HOLE3.1MM"))
    )
    (comp (ref "OSHW_LOGO")
      (value "OSHW-LOGOS")
      (footprint "eagle-import:OSHW-LOGO-S")
      (libsource (lib "eagle-import") (part "OSHW-LOGOS"))
    )
    (comp (ref "S1RX")
      (value "PAD.04")
      (footprint "eagle-import:PAD.04X.04")
      (libsource (lib "eagle-import") (part "PAD.04"))
    )
    (comp (ref "S1TX")
      (value "PAD.04")
      (footprint "eagle-import:PAD.04X.04")
      (libsource (lib "eagle-import") (part "PAD.04"))
    )
    (comp (ref "S2RX")
      (value "PAD.04")
      (footprint "eagle-import:PAD.04X.04")
      (libsource (lib "eagle-import") (part "PAD.04"))
    )
    (comp (ref "S2TX")
      (value "PAD.04")
      (footprint "eagle-import:PAD.04X.04")
      (libsource (lib "eagle-import") (part "PAD.04"))
    )
    (comp (ref "VDDA_3V901")
      (value "PAD.04")
      (footprint "eagle-import:PAD.04X.04")
      (libsource (lib "eagle-import") (part "PAD.04"))
    )
    (comp (ref "VDD_3V901")
      (value "PAD.04")
      (footprint "eagle-import:PAD.04X.04")
      (libsource (lib "eagle-import") (part "PAD.04"))
    )
    (comp (ref "VDD_5V_BRICK")
      (value "PAD.04")
      (footprint "eagle-import:PAD.04X.04")
      (libsource (lib "eagle-import") (part "PAD.04"))
    )
    (comp (ref "VDD_5V_IN")
      (value "PAD.04")
      (footprint "eagle-import:PAD.04X.04")
      (libsource (lib "eagle-import") (part "PAD.04"))
    )
    (comp (ref "C801")
      (value "22u/25V")
      (footprint "eagle-import:0805-CAP")
      (fields (field (name "PARTNO") "CL21A226MAQNNNE"))
      (libsource (lib "eagle-import") (part "CAP0805"))
    )
    (comp (ref "C805")
      (value "2u2")
      (footprint "eagle-import:0402-CAP")
      (fields (field (name "PARTNO") "CC0603ZRY5V6BB225"))
      (libsource (lib "eagle-import") (part "CAP0402"))
    )
    (comp (ref "J801")
      (value "DF13C-6P-1.25V")
      (footprint "eagle-import:DF13C-6P-1.25V")
      (fields (field (name "PARTNO") "DF13C-6P-1.25V(20)"))
      (libsource (lib "eagle-import") (part "DF13-6P-1.25V"))
    )
    (comp (ref "L801")
      (value "KNH16C104DA5TS")
      (footprint "eagle-import:KYOCERA-KNH16-DA")
      (libsource (lib "eagle-import") (part "KNH16C104DA5TS"))
    )
    (comp (ref "L802")
      (value "KNH16C104DA5TS")
      (footprint "eagle-import:KYOCERA-KNH16-DA")
      (libsource (lib "eagle-import") (part "KNH16C104DA5TS"))
    )
    (comp (ref "R1")
      (value "10K/0.1%")
      (footprint "eagle-import:0402-RES")
      (fields (field (name "PARTNO") "ERA-2AEB103X"))
      (libsource (lib "eagle-import") (part "RESISTOR0402-RES"))
    )
    (comp (ref "R2")
      (value "10K/0.1%")
      (footprint "eagle-import:0402-RES")
      (fields (field (name "PARTNO") "ERA-2AEB103X"))
      (libsource (lib "eagle-import") (part "RESISTOR0402-RES"))
    )
    (comp (ref "R801")
      (value "1M")
      (footprint "eagle-import:0402-RES")
      (fields (field (name "PARTNO") "RC0402FR-071ML"))
      (libsource (lib "eagle-import") (part "RESISTOR0402-RES"))
    )
    (comp (ref "R802")
      (value "1M")
      (footprint "eagle-import:0402-RES")
      (fields (field (name "PARTNO") "RC0402FR-071ML"))
      (libsource (lib "eagle-import") (part "RESISTOR0402-RES"))
    )
    (comp (ref "R804")
      (value "10K/0.1%")
      (footprint "eagle-import:0402-RES")
      (fields (field (name "PARTNO") "ERA-2AEB103X"))
      (libsource (lib "eagle-import") (part "RESISTOR0402-RES"))
    )
    (comp (ref "R805")
      (value "10K/0.1%")
      (footprint "eagle-import:0402-RES")
      (fields (field (name "PARTNO") "ERA-2AEB103X"))
      (libsource (lib "eagle-import") (part "RESISTOR0402-RES"))
    )
    (comp (ref "R806")
      (value "10K")
      (footprint "eagle-import:0402-RES")
      (fields (field (name "PARTNO") "ERA-2AEB103X"))
      (libsource (lib "eagle-import") (part "RESISTOR0402-RES"))
    )
    (comp (ref "R807")
      (value "10K/0.1%")
      (footprint "eagle-import:0402-RES")
      (fields (field (name "PARTNO") "ERA-2AEB103X"))
      (libsource (lib "eagle-import") (part "RESISTOR0402-RES"))
    )
    (comp (ref "R808")
      (value "10K/0.1%")
      (footprint "eagle-import:0402-RES")
      (fields (field (name "PARTNO") "ERA-2AEB103X"))
      (libsource (lib "eagle-import") (part "RESISTOR0402-RES"))
    )
    (comp (ref "U802")
      (value "MIC5332")
      (footprint "eagle-import:MLF-8-EPAD")
      (fields (field (name "PARTNO") "MIC5332-SSYMT"))
      (libsource (lib "eagle-import") (part "MIC5332"))
    )
    (comp (ref "X801")
      (value "4 pin head")
      (footprint "eagle-import:53047-04")
      (fields (field (name "PARTNO") "53047-04"))
      (libsource (lib "eagle-import") (part "53?-04047"))
    )
    (comp (ref "C301")
      (value "0u1")
      (footprint "eagle-import:0402-CAP")
      (fields (field (name "PARTNO") "CC0402ZRY5V7BB104"))
      (libsource (lib "eagle-import") (part "CAP0402"))
    )
    (comp (ref "C302")
      (value "0u1")
      (footprint "eagle-import:0402-CAP")
      (fields (field (name "PARTNO") "CC0402ZRY5V7BB104"))
      (libsource (lib "eagle-import") (part "CAP0402"))
    )
    (comp (ref "C303")
      (value "10u/10V")
      (footprint "eagle-import:0805-CAP")
      (fields (field (name "PARTNO") "CC0805ZKY5V6BB106"))
      (libsource (lib "eagle-import") (part "CAP0805"))
    )
    (comp (ref "C304")
      (value "0u1")
      (footprint "eagle-import:0402-CAP")
      (fields (field (name "PARTNO") "CC0402ZRY5V7BB104"))
      (libsource (lib "eagle-import") (part "CAP0402"))
    )
    (comp (ref "C305")
      (value "0u1")
      (footprint "eagle-import:0402-CAP")
      (fields (field (name "PARTNO") "CC0402ZRY5V7BB104"))
      (libsource (lib "eagle-import") (part "CAP0402"))
    )
    (comp (ref "D301")
      (value "PESD0402-140")
      (footprint "eagle-import:0402-TVS")
      (libsource (lib "eagle-import") (part "DIODE-TVS"))
    )
    (comp (ref "D302")
      (value "PESD0402-140")
      (footprint "eagle-import:0402-TVS")
      (libsource (lib "eagle-import") (part "DIODE-TVS"))
    )
    (comp (ref "D303")
      (value "PESD0402-140")
      (footprint "eagle-import:0402-TVS")
      (libsource (lib "eagle-import") (part "DIODE-TVS"))
    )
    (comp (ref "J305")
      (value "DF13-3P-1.25V")
      (footprint "eagle-import:DF13C-3P-1.25V")
      (fields (field (name "PARTNO") "DF13C-3P-1.25V(20)"))
      (libsource (lib "eagle-import") (part "DF13-3P-1.25V"))
    )
    (comp (ref "J306")
      (value "DF13-4P-1.25V")
      (footprint "eagle-import:DF13C-4P-1.25V")
      (fields (field (name "PARTNO") "DF13C-4P-1.25V(20)"))
      (libsource (lib "eagle-import") (part "DF13-4P-1.25V"))
    )
    (comp (ref "J307")
      (value "DF13-4P-1.25V")
      (footprint "eagle-import:DF13C-4P-1.25V")
      (fields (field (name "PARTNO") "DF13C-4P-1.25V(20)"))
      (libsource (lib "eagle-import") (part "DF13-4P-1.25V"))
    )
    (comp (ref "J308")
      (value "DF13-4P-1.25V")
      (footprint "eagle-import:DF13C-4P-1.25V")
      (fields (field (name "PARTNO") "DF13C-4P-1.25V(20)"))
      (libsource (lib "eagle-import") (part "DF13-4P-1.25V"))
    )
    (comp (ref "J309")
      (value "DF13-5P-1.25V")
      (footprint "eagle-import:DF13C-5P-1.25V")
      (fields (field (name "PARTNO") "DF13C-5P-1.25V(20)"))
      (libsource (lib "eagle-import") (part "DF13-5P-1.25V"))
    )
    (comp (ref "J310")
      (value "DF13-4P-1.25V")
      (footprint "eagle-import:DF13C-4P-1.25V")
      (fields (field (name "PARTNO") "DF13C-4P-1.25V(20)"))
      (libsource (lib "eagle-import") (part "DF13-4P-1.25V"))
    )
    (comp (ref "J314")
      (value "DF13-4P-1.25V")
      (footprint "eagle-import:DF13C-4P-1.25V")
      (fields (field (name "PARTNO") "DF13C-4P-1.25V(20)"))
      (libsource (lib "eagle-import") (part "DF13-4P-1.25V"))
    )
    (comp (ref "JP1")
      (value "JP1Q")
      (footprint "eagle-import:JP1")
      (fields (field (name "PARTNO") "1-87215-0"))
      (libsource (lib "eagle-import") (part "JP1Q"))
    )
    (comp (ref "L301")
      (value "KNH16C104DA5TS")
      (footprint "eagle-import:KYOCERA-KNH16-DA")
      (libsource (lib "eagle-import") (part "KNH16C104DA5TS"))
    )
    (comp (ref "L302")
      (value "KNH16C104DA5TS")
      (footprint "eagle-import:KYOCERA-KNH16-DA")
      (libsource (lib "eagle-import") (part "KNH16C104DA5TS"))
    )
    (comp (ref "L303")
      (value "KNH16C104DA5TS")
      (footprint "eagle-import:KYOCERA-KNH16-DA")
      (libsource (lib "eagle-import") (part "KNH16C104DA5TS"))
    )
    (comp (ref "R5")
      (value "10K/0.1%")
      (footprint "eagle-import:0402-RES")
      (fields (field (name "PARTNO") "ERA-2AEB103X"))
      (libsource (lib "eagle-import") (part "RESISTOR0402-RES"))
    )
    (comp (ref "R6")
      (value "10K/0.1%")
      (footprint "eagle-import:0402-RES")
      (fields (field (name "PARTNO") "ERA-2AEB103X"))
      (libsource (lib "eagle-import") (part "RESISTOR0402-RES"))
    )
    (comp (ref "R7")
      (value "10K/0.1%")
      (footprint "eagle-import:0402-RES")
      (fields (field (name "PARTNO") "ERA-2AEB103X"))
      (libsource (lib "eagle-import") (part "RESISTOR0402-RES"))
    )
    (comp (ref "R301")
      (value "1K5")
      (footprint "eagle-import:0402-RES")
      (fields (field (name "PARTNO") "RC0402FR-071K5L"))
      (libsource (lib "eagle-import") (part "RESISTOR0402-RES"))
    )
    (comp (ref "R302")
      (value "1K5")
      (footprint "eagle-import:0402-RES")
      (fields (field (name "PARTNO") "RC0402FR-071K5L"))
      (libsource (lib "eagle-import") (part "RESISTOR0402-RES"))
    )
    (comp (ref "R303")
      (value "10K/0.1%")
      (footprint "eagle-import:0402-RES")
      (fields (field (name "PARTNO") "ERA-2AEB103X"))
      (libsource (lib "eagle-import") (part "RESISTOR0402-RES"))
    )
    (comp (ref "R304")
      (value "1K5")
      (footprint "eagle-import:0402-RES")
      (fields (field (name "PARTNO") "RC0402FR-071K5L"))
      (libsource (lib "eagle-import") (part "RESISTOR0402-RES"))
    )
    (comp (ref "R305")
      (value "1K5")
      (footprint "eagle-import:0402-RES")
      (fields (field (name "PARTNO") "RC0402FR-071K5L"))
      (libsource (lib "eagle-import") (part "RESISTOR0402-RES"))
    )
    (comp (ref "R306")
      (value "10K/0.1%")
      (footprint "eagle-import:0402-RES")
      (fields (field (name "PARTNO") "ERA-2AEB103X"))
      (libsource (lib "eagle-import") (part "RESISTOR0402-RES"))
    )
    (comp (ref "R307")
      (value "10K/0.1%")
      (footprint "eagle-import:0402-RES")
      (fields (field (name "PARTNO") "ERA-2AEB103X"))
      (libsource (lib "eagle-import") (part "RESISTOR0402-RES"))
    )
    (comp (ref "R308")
      (value "10K/0.1%")
      (footprint "eagle-import:0402-RES")
      (fields (field (name "PARTNO") "ERA-2AEB103X"))
      (libsource (lib "eagle-import") (part "RESISTOR0402-RES"))
    )
    (comp (ref "R309")
      (value "120R")
      (footprint "eagle-import:0402-RES")
      (fields (field (name "PARTNO") "RC0402FR-07120RL"))
      (libsource (lib "eagle-import") (part "RESISTOR0402-RES"))
    )
    (comp (ref "R310")
      (value "10K/0.1%")
      (footprint "eagle-import:0402-RES")
      (fields (field (name "PARTNO") "ERA-2AEB103X"))
      (libsource (lib "eagle-import") (part "RESISTOR0402-RES"))
    )
    (comp (ref "R311")
      (value "10K/0.1%")
      (footprint "eagle-import:0402-RES")
      (fields (field (name "PARTNO") "ERA-2AEB103X"))
      (libsource (lib "eagle-import") (part "RESISTOR0402-RES"))
    )
    (comp (ref "R312")
      (value "220R")
      (footprint "eagle-import:0402-RES")
      (fields (field (name "PARTNO") "RC0402FR-07220RL"))
      (libsource (lib "eagle-import") (part "RESISTOR0402-RES"))
    )
    (comp (ref "R313")
      (value "220R")
      (footprint "eagle-import:0402-RES")
      (fields (field (name "PARTNO") "RC0402FR-07220RL"))
      (libsource (lib "eagle-import") (part "RESISTOR0402-RES"))
    )
    (comp (ref "R314")
      (value "10K")
      (footprint "eagle-import:0402-RES")
      (fields (field (name "PARTNO") "ERA-2AEB103X"))
      (libsource (lib "eagle-import") (part "RESISTOR0402-RES"))
    )
    (comp (ref "R315")
      (value "0R")
      (footprint "eagle-import:0402-RES")
      (fields (field (name "PARTNO") "RC0402FR-070RL"))
      (libsource (lib "eagle-import") (part "RESISTOR0402-RES"))
    )
    (comp (ref "U102")
      (value "FM25V01")
      (footprint "eagle-import:SO08")
      (fields (field (name "PARTNO") "FM25V01-G"))
      (libsource (lib "eagle-import") (part "FM25V01"))
    )
    (comp (ref "U301")
      (value "MAX3051")
      (footprint "eagle-import:SOT23-8")
      (fields (field (name "PARTNO") "MAX3051EKA"))
      (libsource (lib "eagle-import") (part "MAX3051MAX3051EKA"))
    )
    (comp (ref "U302")
      (value "TXS0108QFN20")
      (footprint "eagle-import:QFN20-RGY")
      (fields (field (name "PARTNO") "TXS0108ERGYR"))
      (libsource (lib "eagle-import") (part "TXS0108QFN20"))
    )
    (comp (ref "U303")
      (value "PCA9306")
      (footprint "eagle-import:PCA9306")
      (fields (field (name "PARTNO") "PCA9306DQER"))
      (libsource (lib "eagle-import") (part "PCA9306"))
    )
    (comp (ref "C702")
      (value "0u1")
      (footprint "eagle-import:0402-CAP")
      (fields (field (name "PARTNO") "CC0402ZRY5V7BB104"))
      (libsource (lib "eagle-import") (part "CAP0402"))
    )
    (comp (ref "C703")
      (value "0u1")
      (footprint "eagle-import:0402-CAP")
      (fields (field (name "PARTNO") "CC0402ZRY5V7BB104"))
      (libsource (lib "eagle-import") (part "CAP0402"))
    )
    (comp (ref "D703")
      (value "PESD0402-140")
      (footprint "eagle-import:0402-TVS")
      (libsource (lib "eagle-import") (part "DIODE-TVS"))
    )
    (comp (ref "D704")
      (value "DIODE-SCHOTTKY_MSMP")
      (footprint "eagle-import:MICROSMP")
      (fields (field (name "PARTNO") "SS14"))
      (libsource (lib "eagle-import") (part "DIODE-SCHOTTKY_MSMP"))
    )
    (comp (ref "D705")
      (value "DIODE-SCHOTTKY_MSMP")
      (footprint "eagle-import:MICROSMP")
      (fields (field (name "PARTNO") "SS14"))
      (libsource (lib "eagle-import") (part "DIODE-SCHOTTKY_MSMP"))
    )
    (comp (ref "D706")
      (value "PESD0402-140")
      (footprint "eagle-import:0402-TVS")
      (libsource (lib "eagle-import") (part "DIODE-TVS"))
    )
    (comp (ref "F701")
      (value "0ZCA0035FF2G")
      (footprint "eagle-import:PTC-1206")
      (libsource (lib "eagle-import") (part "PTCSMD"))
    )
    (comp (ref "J701")
      (value "JST-ZH-3")
      (footprint "eagle-import:JST-ZH-SMT-VERTICAL")
      (fields (field (name "PARTNO") "B3B-ZR-SM4-TF (LF)(SN)(P)"))
      (libsource (lib "eagle-import") (part "JST-ZH-3"))
    )
    (comp (ref "L701")
      (value "KNH16C104DA5TS")
      (footprint "eagle-import:KYOCERA-KNH16-DA")
      (libsource (lib "eagle-import") (part "KNH16C104DA5TS"))
    )
    (comp (ref "R3")
      (value "100K/0.1%")
      (footprint "eagle-import:0402-RES")
      (fields (field (name "PARTNO") "ERA-2AEB104X"))
      (libsource (lib "eagle-import") (part "RESISTOR0402-RES"))
    )
    (comp (ref "R8")
      (value "220R")
      (footprint "eagle-import:0402-RES")
      (fields (field (name "PARTNO") "RC0402FR-07220RL"))
      (libsource (lib "eagle-import") (part "RESISTOR0402-RES"))
    )
    (comp (ref "R9")
      (value "220R")
      (footprint "eagle-import:0402-RES")
      (fields (field (name "PARTNO") "RC0402FR-07220RL"))
      (libsource (lib "eagle-import") (part "RESISTOR0402-RES"))
    )
    (comp (ref "R701")
      (value "220R")
      (footprint "eagle-import:0402-RES")
      (fields (field (name "PARTNO") "RC0402FR-07120RL"))
      (libsource (lib "eagle-import") (part "RESISTOR0402-RES"))
    )
    (comp (ref "R702")
      (value "220R")
      (footprint "eagle-import:0402-RES")
      (fields (field (name "PARTNO") "RC0402FR-07120RL"))
      (libsource (lib "eagle-import") (part "RESISTOR0402-RES"))
    )
    (comp (ref "R703")
      (value "220R")
      (footprint "eagle-import:0402-RES")
      (fields (field (name "PARTNO") "RC0402FR-07120RL"))
      (libsource (lib "eagle-import") (part "RESISTOR0402-RES"))
    )
    (comp (ref "R704")
      (value "220R")
      (footprint "eagle-import:0402-RES")
      (fields (field (name "PARTNO") "RC0402FR-07120RL"))
      (libsource (lib "eagle-import") (part "RESISTOR0402-RES"))
    )
    (comp (ref "R705")
      (value "220R")
      (footprint "eagle-import:0402-RES")
      (fields (field (name "PARTNO") "RC0402FR-07120RL"))
      (libsource (lib "eagle-import") (part "RESISTOR0402-RES"))
    )
    (comp (ref "R706")
      (value "220R")
      (footprint "eagle-import:0402-RES")
      (fields (field (name "PARTNO") "RC0402FR-07120RL"))
      (libsource (lib "eagle-import") (part "RESISTOR0402-RES"))
    )
    (comp (ref "R707")
      (value "220R")
      (footprint "eagle-import:0402-RES")
      (fields (field (name "PARTNO") "RC0402FR-07120RL"))
      (libsource (lib "eagle-import") (part "RESISTOR0402-RES"))
    )
    (comp (ref "R708")
      (value "220R")
      (footprint "eagle-import:0402-RES")
      (fields (field (name "PARTNO") "RC0402FR-07120RL"))
      (libsource (lib "eagle-import") (part "RESISTOR0402-RES"))
    )
    (comp (ref "R709")
      (value "220R")
      (footprint "eagle-import:0402-RES")
      (fields (field (name "PARTNO") "RC0402FR-07120RL"))
      (libsource (lib "eagle-import") (part "RESISTOR0402-RES"))
    )
    (comp (ref "R710")
      (value "220R")
      (footprint "eagle-import:0402-RES")
      (fields (field (name "PARTNO") "RC0402FR-07120RL"))
      (libsource (lib "eagle-import") (part "RESISTOR0402-RES"))
    )
    (comp (ref "R711")
      (value "220R")
      (footprint "eagle-import:0402-RES")
      (fields (field (name "PARTNO") "RC0402FR-07120RL"))
      (libsource (lib "eagle-import") (part "RESISTOR0402-RES"))
    )
    (comp (ref "R712")
      (value "220R")
      (footprint "eagle-import:0402-RES")
      (fields (field (name "PARTNO") "RC0402FR-07120RL"))
      (libsource (lib "eagle-import") (part "RESISTOR0402-RES"))
    )
    (comp (ref "R713")
      (value "220R")
      (footprint "eagle-import:0402-RES")
      (fields (field (name "PARTNO") "RC0402FR-07120RL"))
      (libsource (lib "eagle-import") (part "RESISTOR0402-RES"))
    )
    (comp (ref "R714")
      (value "220R")
      (footprint "eagle-import:0402-RES")
      (fields (field (name "PARTNO") "RC0402FR-07120RL"))
      (libsource (lib "eagle-import") (part "RESISTOR0402-RES"))
    )
    (comp (ref "R716")
      (value "10K/0.1%")
      (footprint "eagle-import:0402-RES")
      (fields (field (name "PARTNO") "ERA-2AEB103X"))
      (libsource (lib "eagle-import") (part "RESISTOR0402-RES"))
    )
    (comp (ref "R718")
      (value "10K")
      (footprint "eagle-import:0402-RES")
      (fields (field (name "PARTNO") "ERA-2AEB103X"))
      (libsource (lib "eagle-import") (part "RESISTOR0402-RES"))
    )
    (comp (ref "R719")
      (value "10K")
      (footprint "eagle-import:0402-RES")
      (fields (field (name "PARTNO") "ERA-2AEB103X"))
      (libsource (lib "eagle-import") (part "RESISTOR0402-RES"))
    )
    (comp (ref "U701")
      (value "TXS0108QFN20")
      (footprint "eagle-import:QFN20-RGY")
      (fields (field (name "PARTNO") "TXS0108ERGYR"))
      (libsource (lib "eagle-import") (part "TXS0108QFN20"))
    )
    (comp (ref "U702")
      (value "TXS0108QFN20")
      (footprint "eagle-import:QFN20-RGY")
      (fields (field (name "PARTNO") "TXS0108ERGYR"))
      (libsource (lib "eagle-import") (part "TXS0108QFN20"))
    )
    (comp (ref "U704")
      (value "BBB_3X14_RA")
      (footprint "eagle-import:3X14RA")
      (fields (field (name "PARTNO") "07579"))
      (libsource (lib "eagle-import") (part "BBB_3X14_RA"))
    )
  )
  (nets
    (net (code "1") (name "3V3_EN") (class "Default")
      (node (ref "R102") (pin "P$2") (pinfunction "2_P$2") (pintype "passive"))
      (node (ref "R503") (pin "P$2") (pinfunction "2_P$2") (pintype "passive"))
      (node (ref "U$101") (pin "56") (pinfunction "SYS_RESETN_10_56") (pintype "passive"))
      (node (ref "U$101") (pin "73") (pinfunction "27_PRU1_R30/31[5]_73") (pintype "passive"))
      (node (ref "U502") (pin "4") (pinfunction "EN2_4") (pintype "bidirectional"))
      (node (ref "U502") (pin "5") (pinfunction "EN1_5") (pintype "bidirectional"))
    )
    (net (code "2") (name "3_VDD_3V3") (class "Default")
      (node (ref "U$101") (pin "49") (pinfunction "3_VDD_3V3_49") (pintype "power_in"))
    )
    (net (code "3") (name "ACCEL_DRDY") (class "Default")
      (node (ref "U$101") (pin "8") (pinfunction "GPIO2[3]_8_8") (pintype "passive"))
      (node (ref "U406") (pin "14") (pinfunction "INT2_XM_14") (pintype "bidirectional"))
    )
    (net (code "4") (name "ALARM") (class "Default")
      (node (ref "R602") (pin "P$2") (pinfunction "2_P$2") (pintype "passive"))
      (node (ref "U$101") (pin "36") (pinfunction "GPIO2[16]_36_36") (pintype "passive"))
    )
    (net (code "5") (name "AUX_ADC1") (class "Default")
      (node (ref "R308") (pin "P$1") (pinfunction "1_P$1") (pintype "passive"))
      (node (ref "U$101") (pin "83") (pinfunction "37_AIN2_83") (pintype "passive"))
    )
    (net (code "6") (name "AUX_ADC2") (class "Default")
      (node (ref "R307") (pin "P$1") (pinfunction "1_P$1") (pintype "passive"))
      (node (ref "U$101") (pin "84") (pinfunction "AIN3_38_84") (pintype "passive"))
    )
    (net (code "7") (name "BACKUP_LIPO_+_1S") (class "Default")
      (node (ref "U$101") (pin "TP5") (pinfunction "BAT_+_LIPO_1_S_TP5") (pintype "bidirectional"))
      (node (ref "X801") (pin "1") (pinfunction "S_1") (pintype "passive"))
    )
    (net (code "8") (name "BATT_CURRENT_SENS") (class "Default")
      (node (ref "R1") (pin "P$1") (pinfunction "1_P$1") (pintype "passive"))
      (node (ref "R808") (pin "P$1") (pinfunction "1_P$1") (pintype "passive"))
      (node (ref "U$101") (pin "81") (pinfunction "35_AIN6_81") (pintype "passive"))
    )
    (net (code "9") (name "BATT_SENSE") (class "Default")
      (node (ref "U$101") (pin "TP6") (pinfunction "BAT_SENSE_TP6") (pintype "bidirectional"))
      (node (ref "X801") (pin "2") (pinfunction "S_2") (pintype "passive"))
    )
    (net (code "10") (name "BATT_TEMP_SENSE") (class "Default")
      (node (ref "U$101") (pin "TP7") (pinfunction "TEMP_SENSE_TP7") (pintype "bidirectional"))
      (node (ref "X801") (pin "3") (pinfunction "S_3") (pintype "passive"))
    )
    (net (code "11") (name "BATT_VOLTAGE_SENS") (class "Default")
      (node (ref "R2") (pin "P$1") (pinfunction "1_P$1") (pintype "passive"))
      (node (ref "R807") (pin "P$1") (pinfunction "1_P$1") (pintype "passive"))
      (node (ref "U$101") (pin "82") (pinfunction "AIN5_36_82") (pintype "passive"))
    )
    (net (code "12") (name "BBB-VDD_3V3") (class "Default")
      (node (ref "C201") (pin "P$1") (pinfunction "1_P$1") (pintype "passive"))
      (node (ref "C302") (pin "P$1") (pinfunction "1_P$1") (pintype "passive"))
      (node (ref "C303") (pin "P$1") (pinfunction "1_P$1") (pintype "passive"))
      (node (ref "C304") (pin "P$1") (pinfunction "1_P$1") (pintype "passive"))
      (node (ref "C505") (pin "P$1") (pinfunction "1_P$1") (pintype "passive"))
      (node (ref "C506") (pin "P$1") (pinfunction "1_P$1") (pintype "passive"))
      (node (ref "C507") (pin "P$1") (pinfunction "1_P$1") (pintype "passive"))
      (node (ref "C702") (pin "P$1") (pinfunction "1_P$1") (pintype "passive"))
      (node (ref "C703") (pin "P$1") (pinfunction "1_P$1") (pintype "passive"))
      (node (ref "D601") (pin "C") (pinfunction "C_C") (pintype "passive"))
      (node (ref "JP1") (pin "2") (pinfunction "2_2") (pintype "passive"))
      (node (ref "R215") (pin "P$2") (pinfunction "2_P$2") (pintype "passive"))
      (node (ref "R301") (pin "P$2") (pinfunction "2_P$2") (pintype "passive"))
      (node (ref "R302") (pin "P$2") (pinfunction "2_P$2") (pintype "passive"))
      (node (ref "R304") (pin "P$1") (pinfunction "1_P$1") (pintype "passive"))
      (node (ref "R305") (pin "P$1") (pinfunction "1_P$1") (pintype "passive"))
      (node (ref "R314") (pin "P$2") (pinfunction "2_P$2") (pintype "passive"))
      (node (ref "R502") (pin "P$2") (pinfunction "2_P$2") (pintype "passive"))
      (node (ref "R507") (pin "P$2") (pinfunction "2_P$2") (pintype "passive"))
      (node (ref "R718") (pin "P$2") (pinfunction "2_P$2") (pintype "passive"))
      (node (ref "R719") (pin "P$2") (pinfunction "2_P$2") (pintype "passive"))
      (node (ref "U$12") (pin "1") (pinfunction "1_1") (pintype "passive"))
      (node (ref "U201") (pin "19") (pinfunction "VCCB_19") (pintype "input"))
      (node (ref "U201") (pin "2") (pinfunction "VCCA_2") (pintype "input"))
      (node (ref "U301") (pin "3") (pinfunction "VCC_3") (pintype "input"))
      (node (ref "U302") (pin "10") (pinfunction "OE_10") (pintype "input"))
      (node (ref "U302") (pin "2") (pinfunction "VCCA_2") (pintype "input"))
      (node (ref "U303") (pin "2") (pinfunction "VREF1_2") (pintype "bidirectional"))
      (node (ref "U303") (pin "7") (pinfunction "VREF2_7") (pintype "bidirectional"))
      (node (ref "U303") (pin "8") (pinfunction "EN_8") (pintype "bidirectional"))
      (node (ref "U502") (pin "7") (pinfunction "VOUT2_7") (pintype "bidirectional"))
      (node (ref "U701") (pin "19") (pinfunction "VCCB_19") (pintype "input"))
      (node (ref "U701") (pin "2") (pinfunction "VCCA_2") (pintype "input"))
      (node (ref "U702") (pin "19") (pinfunction "VCCB_19") (pintype "input"))
      (node (ref "U702") (pin "2") (pinfunction "VCCA_2") (pintype "input"))
      (node (ref "VDD_3V901") (pin "P$1") (pinfunction "P$1_P$1") (pintype "passive"))
    )
    (net (code "13") (name "CAN1_RX_1") (class "Default")
      (node (ref "U$101") (pin "70") (pinfunction "UART1/CAN1_TXD_24_70") (pintype "passive"))
      (node (ref "U301") (pin "4") (pinfunction "DOUT_4") (pintype "output"))
    )
    (net (code "14") (name "CAN1_TX_1") (class "Default")
      (node (ref "U$101") (pin "72") (pinfunction "UART1/CAN1_RXD_26_72") (pintype "passive"))
      (node (ref "U301") (pin "1") (pinfunction "DIN_1") (pintype "input"))
    )
    (net (code "15") (name "CAN_H") (class "Default")
      (node (ref "CAN_H") (pin "P$1") (pinfunction "P$1_P$1") (pintype "passive"))
      (node (ref "J307") (pin "2") (pinfunction "2_2") (pintype "passive"))
      (node (ref "R309") (pin "P$1") (pinfunction "1_P$1") (pintype "passive"))
      (node (ref "U301") (pin "7") (pinfunction "CANH_7") (pintype "bidirectional"))
    )
    (net (code "16") (name "CAN_L") (class "Default")
      (node (ref "CAN_L") (pin "P$1") (pinfunction "P$1_P$1") (pintype "passive"))
      (node (ref "J307") (pin "3") (pinfunction "3_3") (pintype "passive"))
      (node (ref "R309") (pin "P$2") (pinfunction "2_P$2") (pintype "passive"))
      (node (ref "U301") (pin "6") (pinfunction "CANL_6") (pintype "bidirectional"))
    )
    (net (code "17") (name "CH_1") (class "Default")
      (node (ref "U$101") (pin "28") (pinfunction "PRU1_R30/31[10]_28_28") (pintype "passive"))
      (node (ref "U701") (pin "5") (pinfunction "A4_5") (pintype "bidirectional"))
    )
    (net (code "18") (name "CH_1_OUT") (class "Default")
      (node (ref "R714") (pin "P$1") (pinfunction "1_P$1") (pintype "passive"))
      (node (ref "U701") (pin "16") (pinfunction "B4_16") (pintype "bidirectional"))
    )
    (net (code "19") (name "CH_2") (class "Default")
      (node (ref "U$101") (pin "27") (pinfunction "27_PRU1_R30/31[8]_27") (pintype "passive"))
      (node (ref "U701") (pin "4") (pinfunction "A3_4") (pintype "bidirectional"))
    )
    (net (code "20") (name "CH_2_OUT") (class "Default")
      (node (ref "R713") (pin "P$1") (pinfunction "1_P$1") (pintype "passive"))
      (node (ref "U701") (pin "17") (pinfunction "B3_17") (pintype "bidirectional"))
    )
    (net (code "21") (name "CH_3") (class "Default")
      (node (ref "U$101") (pin "30") (pinfunction "PRU1_R30/31[11]_30_30") (pintype "passive"))
      (node (ref "U701") (pin "3") (pinfunction "A2_3") (pintype "bidirectional"))
    )
    (net (code "22") (name "CH_3_OUT") (class "Default")
      (node (ref "R712") (pin "P$1") (pinfunction "1_P$1") (pintype "passive"))
      (node (ref "U701") (pin "18") (pinfunction "B2_18") (pintype "bidirectional"))
    )
    (net (code "23") (name "CH_4") (class "Default")
      (node (ref "U$101") (pin "29") (pinfunction "29_PRU1_R30/31[9]_29") (pintype "passive"))
      (node (ref "U701") (pin "1") (pinfunction "A1_1") (pintype "bidirectional"))
    )
    (net (code "24") (name "CH_4_OUT") (class "Default")
      (node (ref "R701") (pin "P$1") (pinfunction "1_P$1") (pintype "passive"))
      (node (ref "U701") (pin "20") (pinfunction "B1_20") (pintype "bidirectional"))
    )
    (net (code "25") (name "CH_5") (class "Default")
      (node (ref "U$101") (pin "40") (pinfunction "PRU1_R30/31[7]_40_40") (pintype "passive"))
      (node (ref "U702") (pin "9") (pinfunction "A8_9") (pintype "bidirectional"))
    )
    (net (code "26") (name "CH_5_OUT") (class "Default")
      (node (ref "R702") (pin "P$1") (pinfunction "1_P$1") (pintype "passive"))
      (node (ref "U702") (pin "12") (pinfunction "B8_12") (pintype "bidirectional"))
    )
    (net (code "27") (name "CH_6") (class "Default")
      (node (ref "U$101") (pin "39") (pinfunction "39_PRU1_R30/31[6]_39") (pintype "passive"))
      (node (ref "U702") (pin "8") (pinfunction "A7_8") (pintype "bidirectional"))
    )
    (net (code "28") (name "CH_6_OUT") (class "Default")
      (node (ref "R703") (pin "P$1") (pinfunction "1_P$1") (pintype "passive"))
      (node (ref "U702") (pin "13") (pinfunction "B7_13") (pintype "bidirectional"))
    )
    (net (code "29") (name "CH_7") (class "Default")
      (node (ref "U$101") (pin "42") (pinfunction "PRU1_R30/31[5]_42_42") (pintype "passive"))
      (node (ref "U702") (pin "7") (pinfunction "A6_7") (pintype "bidirectional"))
    )
    (net (code "30") (name "CH_7_OUT") (class "Default")
      (node (ref "R704") (pin "P$1") (pinfunction "1_P$1") (pintype "passive"))
      (node (ref "U702") (pin "14") (pinfunction "B6_14") (pintype "bidirectional"))
    )
    (net (code "31") (name "CH_8") (class "Default")
      (node (ref "U$101") (pin "41") (pinfunction "41_PRU1_R30/31[4]_41") (pintype "passive"))
      (node (ref "U702") (pin "6") (pinfunction "A5_6") (pintype "bidirectional"))
    )
    (net (code "32") (name "CH_8_OUT") (class "Default")
      (node (ref "R705") (pin "P$1") (pinfunction "1_P$1") (pintype "passive"))
      (node (ref "U702") (pin "15") (pinfunction "B5_15") (pintype "bidirectional"))
    )
    (net (code "33") (name "CH_9") (class "Default")
      (node (ref "U$101") (pin "44") (pinfunction "PRU1_R30/31[3]_44_44") (pintype "passive"))
      (node (ref "U702") (pin "5") (pinfunction "A4_5") (pintype "bidirectional"))
    )
    (net (code "34") (name "CH_9_OUT") (class "Default")
      (node (ref "R706") (pin "P$1") (pinfunction "1_P$1") (pintype "passive"))
      (node (ref "U702") (pin "16") (pinfunction "B4_16") (pintype "bidirectional"))
    )
    (net (code "35") (name "CH_10") (class "Default")
      (node (ref "U$101") (pin "43") (pinfunction "43_PRU1_R30/31[2]_43") (pintype "passive"))
      (node (ref "U702") (pin "4") (pinfunction "A3_4") (pintype "bidirectional"))
    )
    (net (code "36") (name "CH_10_OUT") (class "Default")
      (node (ref "R707") (pin "P$1") (pinfunction "1_P$1") (pintype "passive"))
      (node (ref "U702") (pin "17") (pinfunction "B3_17") (pintype "bidirectional"))
    )
    (net (code "37") (name "CH_11") (class "Default")
      (node (ref "U$101") (pin "46") (pinfunction "PRU1_R30/31[1]_46_46") (pintype "passive"))
      (node (ref "U702") (pin "3") (pinfunction "A2_3") (pintype "bidirectional"))
    )
    (net (code "38") (name "CH_11_OUT") (class "Default")
      (node (ref "R708") (pin "P$1") (pinfunction "1_P$1") (pintype "passive"))
      (node (ref "U702") (pin "18") (pinfunction "B2_18") (pintype "bidirectional"))
    )
    (net (code "39") (name "CH_12") (class "Default")
      (node (ref "U$101") (pin "45") (pinfunction "45_PRU1_R30/31[0]_45") (pintype "passive"))
      (node (ref "U702") (pin "1") (pinfunction "A1_1") (pintype "bidirectional"))
    )
    (net (code "40") (name "CH_12_OUT") (class "Default")
      (node (ref "R709") (pin "P$1") (pinfunction "1_P$1") (pintype "passive"))
      (node (ref "U702") (pin "20") (pinfunction "B1_20") (pintype "bidirectional"))
    )
    (net (code "41") (name "GND") (class "Default")
      (node (ref "C101") (pin "P$2") (pinfunction "2_P$2") (pintype "passive"))
      (node (ref "C201") (pin "P$2") (pinfunction "2_P$2") (pintype "passive"))
      (node (ref "C301") (pin "P$2") (pinfunction "2_P$2") (pintype "passive"))
      (node (ref "C302") (pin "P$2") (pinfunction "2_P$2") (pintype "passive"))
      (node (ref "C303") (pin "P$2") (pinfunction "2_P$2") (pintype "passive"))
      (node (ref "C304") (pin "P$2") (pinfunction "2_P$2") (pintype "passive"))
      (node (ref "C305") (pin "P$2") (pinfunction "2_P$2") (pintype "passive"))
      (node (ref "C401") (pin "P$2") (pinfunction "2_P$2") (pintype "passive"))
      (node (ref "C402") (pin "P$2") (pinfunction "2_P$2") (pintype "passive"))
      (node (ref "C405") (pin "P$1") (pinfunction "1_P$1") (pintype "passive"))
      (node (ref "C406") (pin "P$1") (pinfunction "1_P$1") (pintype "passive"))
      (node (ref "C407") (pin "P$2") (pinfunction "2_P$2") (pintype "passive"))
      (node (ref "C408") (pin "P$2") (pinfunction "2_P$2") (pintype "passive"))
      (node (ref "C409") (pin "P$2") (pinfunction "2_P$2") (pintype "passive"))
      (node (ref "C410") (pin "P$2") (pinfunction "2_P$2") (pintype "passive"))
      (node (ref "C411") (pin "P$2") (pinfunction "2_P$2") (pintype "passive"))
      (node (ref "C412") (pin "P$2") (pinfunction "2_P$2") (pintype "passive"))
      (node (ref "C413") (pin "P$2") (pinfunction "2_P$2") (pintype "passive"))
      (node (ref "C414") (pin "P$2") (pinfunction "2_P$2") (pintype "passive"))
      (node (ref "C415") (pin "P$2") (pinfunction "2_P$2") (pintype "passive"))
      (node (ref "C416") (pin "P$2") (pinfunction "2_P$2") (pintype "passive"))
      (node (ref "C501") (pin "P$2") (pinfunction "2_P$2") (pintype "passive"))
      (node (ref "C502") (pin "P$2") (pinfunction "2_P$2") (pintype "passive"))
      (node (ref "C503") (pin "P$2") (pinfunction "2_P$2") (pintype "passive"))
      (node (ref "C504") (pin "P$2") (pinfunction "2_P$2") (pintype "passive"))
      (node (ref "C505") (pin "P$2") (pinfunction "2_P$2") (pintype "passive"))
      (node (ref "C506") (pin "P$2") (pinfunction "2_P$2") (pintype "passive"))
      (node (ref "C507") (pin "P$2") (pinfunction "2_P$2") (pintype "passive"))
      (node (ref "C508") (pin "P$2") (pinfunction "2_P$2") (pintype "passive"))
      (node (ref "C509") (pin "P$2") (pinfunction "2_P$2") (pintype "passive"))
      (node (ref "C510") (pin "P$2") (pinfunction "2_P$2") (pintype "passive"))
      (node (ref "C602") (pin "P$2") (pinfunction "2_P$2") (pintype "passive"))
      (node (ref "C603") (pin "P$2") (pinfunction "2_P$2") (pintype "passive"))
      (node (ref "C604") (pin "P$2") (pinfunction "2_P$2") (pintype "passive"))
      (node (ref "C702") (pin "P$2") (pinfunction "2_P$2") (pintype "passive"))
      (node (ref "C703") (pin "P$2") (pinfunction "2_P$2") (pintype "passive"))
      (node (ref "C801") (pin "P$2") (pinfunction "2_P$2") (pintype "passive"))
      (node (ref "C805") (pin "P$2") (pinfunction "2_P$2") (pintype "passive"))
      (node (ref "D201") (pin "A") (pinfunction "A_A") (pintype "passive"))
      (node (ref "D202") (pin "A") (pinfunction "A_A") (pintype "passive"))
      (node (ref "D203") (pin "A") (pinfunction "A_A") (pintype "passive"))
      (node (ref "D301") (pin "A") (pinfunction "A_A") (pintype "passive"))
      (node (ref "D302") (pin "A") (pinfunction "A_A") (pintype "passive"))
      (node (ref "D303") (pin "A") (pinfunction "A_A") (pintype "passive"))
      (node (ref "D601") (pin "A") (pinfunction "A_A") (pintype "passive"))
      (node (ref "D703") (pin "A") (pinfunction "A_A") (pintype "passive"))
      (node (ref "D706") (pin "A") (pinfunction "A_A") (pintype "passive"))
      (node (ref "GND") (pin "P$1") (pinfunction "P$1_P$1") (pintype "passive"))
      (node (ref "GND.") (pin "P$1") (pinfunction "P$1_P$1") (pintype "passive"))
      (node (ref "J305") (pin "3") (pinfunction "3_3") (pintype "passive"))
      (node (ref "J305") (pin "P$4") (pinfunction "P$1_P$4") (pintype "bidirectional"))
      (node (ref "J305") (pin "P$5") (pinfunction "P$2_P$5") (pintype "bidirectional"))
      (node (ref "J306") (pin "4") (pinfunction "4_4") (pintype "passive"))
      (node (ref "J306") (pin "P$5") (pinfunction "P$1_P$5") (pintype "bidirectional"))
      (node (ref "J306") (pin "P$6") (pinfunction "P$2_P$6") (pintype "bidirectional"))
      (node (ref "J307") (pin "4") (pinfunction "4_4") (pintype "passive"))
      (node (ref "J307") (pin "P$5") (pinfunction "P$1_P$5") (pintype "bidirectional"))
      (node (ref "J307") (pin "P$6") (pinfunction "P$2_P$6") (pintype "bidirectional"))
      (node (ref "J308") (pin "4") (pinfunction "4_4") (pintype "passive"))
      (node (ref "J308") (pin "P$5") (pinfunction "P$1_P$5") (pintype "bidirectional"))
      (node (ref "J308") (pin "P$6") (pinfunction "P$2_P$6") (pintype "bidirectional"))
      (node (ref "J309") (pin "3") (pinfunction "3_3") (pintype "passive"))
      (node (ref "J309") (pin "5") (pinfunction "5_5") (pintype "passive"))
      (node (ref "J309") (pin "P$6") (pinfunction "P$1_P$6") (pintype "bidirectional"))
      (node (ref "J309") (pin "P$7") (pinfunction "P$2_P$7") (pintype "bidirectional"))
      (node (ref "J310") (pin "4") (pinfunction "4_4") (pintype "passive"))
      (node (ref "J310") (pin "P$5") (pinfunction "P$1_P$5") (pintype "bidirectional"))
      (node (ref "J310") (pin "P$6") (pinfunction "P$2_P$6") (pintype "bidirectional"))
      (node (ref "J314") (pin "4") (pinfunction "4_4") (pintype "passive"))
      (node (ref "J314") (pin "P$5") (pinfunction "P$1_P$5") (pintype "bidirectional"))
      (node (ref "J314") (pin "P$6") (pinfunction "P$2_P$6") (pintype "bidirectional"))
      (node (ref "J701") (pin "P$2") (pinfunction "P$2_P$2") (pintype "bidirectional"))
      (node (ref "J801") (pin "5") (pinfunction "5_5") (pintype "passive"))
      (node (ref "J801") (pin "6") (pinfunction "6_6") (pintype "passive"))
      (node (ref "L201") (pin "P$3") (pinfunction "P$3_P$3") (pintype "bidirectional"))
      (node (ref "L201") (pin "P$4") (pinfunction "P$3_P$4") (pintype "bidirectional"))
      (node (ref "L201") (pin "P$5") (pinfunction "P$3_P$5") (pintype "bidirectional"))
      (node (ref "L202") (pin "P$3") (pinfunction "P$3_P$3") (pintype "bidirectional"))
      (node (ref "L202") (pin "P$4") (pinfunction "P$3_P$4") (pintype "bidirectional"))
      (node (ref "L202") (pin "P$5") (pinfunction "P$3_P$5") (pintype "bidirectional"))
      (node (ref "L203") (pin "P$3") (pinfunction "P$3_P$3") (pintype "bidirectional"))
      (node (ref "L203") (pin "P$4") (pinfunction "P$3_P$4") (pintype "bidirectional"))
      (node (ref "L203") (pin "P$5") (pinfunction "P$3_P$5") (pintype "bidirectional"))
      (node (ref "L301") (pin "P$3") (pinfunction "P$3_P$3") (pintype "bidirectional"))
      (node (ref "L301") (pin "P$4") (pinfunction "P$3_P$4") (pintype "bidirectional"))
      (node (ref "L301") (pin "P$5") (pinfunction "P$3_P$5") (pintype "bidirectional"))
      (node (ref "L302") (pin "P$3") (pinfunction "P$3_P$3") (pintype "bidirectional"))
      (node (ref "L302") (pin "P$4") (pinfunction "P$3_P$4") (pintype "bidirectional"))
      (node (ref "L302") (pin "P$5") (pinfunction "P$3_P$5") (pintype "bidirectional"))
      (node (ref "L303") (pin "P$3") (pinfunction "P$3_P$3") (pintype "bidirectional"))
      (node (ref "L303") (pin "P$4") (pinfunction "P$3_P$4") (pintype "bidirectional"))
      (node (ref "L303") (pin "P$5") (pinfunction "P$3_P$5") (pintype "bidirectional"))
      (node (ref "L501") (pin "P$3") (pinfunction "P$3_P$3") (pintype "bidirectional"))
      (node (ref "L501") (pin "P$4") (pinfunction "P$3_P$4") (pintype "bidirectional"))
      (node (ref "L501") (pin "P$5") (pinfunction "P$3_P$5") (pintype "bidirectional"))
      (node (ref "L701") (pin "P$3") (pinfunction "P$3_P$3") (pintype "bidirectional"))
      (node (ref "L701") (pin "P$4") (pinfunction "P$3_P$4") (pintype "bidirectional"))
      (node (ref "L701") (pin "P$5") (pinfunction "P$3_P$5") (pintype "bidirectional"))
      (node (ref "L801") (pin "P$3") (pinfunction "P$3_P$3") (pintype "bidirectional"))
      (node (ref "L801") (pin "P$4") (pinfunction "P$3_P$4") (pintype "bidirectional"))
      (node (ref "L801") (pin "P$5") (pinfunction "P$3_P$5") (pintype "bidirectional"))
      (node (ref "L802") (pin "P$3") (pinfunction "P$3_P$3") (pintype "bidirectional"))
      (node (ref "L802") (pin "P$4") (pinfunction "P$3_P$4") (pintype "bidirectional"))
      (node (ref "L802") (pin "P$5") (pinfunction "P$3_P$5") (pintype "bidirectional"))
      (node (ref "R102") (pin "P$1") (pinfunction "1_P$1") (pintype "passive"))
      (node (ref "R215") (pin "P$1") (pinfunction "1_P$1") (pintype "passive"))
      (node (ref "R303") (pin "P$1") (pinfunction "1_P$1") (pintype "passive"))
      (node (ref "R310") (pin "P$1") (pinfunction "1_P$1") (pintype "passive"))
      (node (ref "R311") (pin "P$1") (pinfunction "1_P$1") (pintype "passive"))
      (node (ref "R314") (pin "P$1") (pinfunction "1_P$1") (pintype "passive"))
      (node (ref "R315") (pin "P$2") (pinfunction "2_P$2") (pintype "passive"))
      (node (ref "R501") (pin "P$2") (pinfunction "2_P$2") (pintype "passive"))
      (node (ref "R504") (pin "P$2") (pinfunction "2_P$2") (pintype "passive"))
      (node (ref "R505") (pin "1") (pinfunction "1_1") (pintype "passive"))
      (node (ref "R506") (pin "P$2") (pinfunction "2_P$2") (pintype "passive"))
      (node (ref "R509") (pin "P$2") (pinfunction "2_P$2") (pintype "passive"))
      (node (ref "R603") (pin "P$2") (pinfunction "2_P$2") (pintype "passive"))
      (node (ref "R607") (pin "P$2") (pinfunction "2_P$2") (pintype "passive"))
      (node (ref "R608") (pin "P$1") (pinfunction "1_P$1") (pintype "passive"))
      (node (ref "R613") (pin "P$2") (pinfunction "2_P$2") (pintype "passive"))
      (node (ref "R716") (pin "P$1") (pinfunction "1_P$1") (pintype "passive"))
      (node (ref "R718") (pin "P$1") (pinfunction "1_P$1") (pintype "passive"))
      (node (ref "R719") (pin "P$1") (pinfunction "1_P$1") (pintype "passive"))
      (node (ref "R8") (pin "P$1") (pinfunction "1_P$1") (pintype "passive"))
      (node (ref "R801") (pin "P$2") (pinfunction "2_P$2") (pintype "passive"))
      (node (ref "R802") (pin "P$2") (pinfunction "2_P$2") (pintype "passive"))
      (node (ref "R806") (pin "P$1") (pinfunction "1_P$1") (pintype "passive"))
      (node (ref "R807") (pin "P$2") (pinfunction "2_P$2") (pintype "passive"))
      (node (ref "R808") (pin "P$2") (pinfunction "2_P$2") (pintype "passive"))
      (node (ref "U$101") (pin "1") (pinfunction "1_GND_1") (pintype "power_in"))
      (node (ref "U$101") (pin "2") (pinfunction "GND_2_2") (pintype "power_in"))
      (node (ref "U$101") (pin "47") (pinfunction "1_GND_47") (pintype "power_in"))
      (node (ref "U$101") (pin "48") (pinfunction "GND_2_48") (pintype "power_in"))
      (node (ref "U$101") (pin "80") (pinfunction "GNDA_ADC_34_80") (pintype "passive"))
      (node (ref "U$101") (pin "89") (pinfunction "43_GND_89") (pintype "power_in"))
      (node (ref "U$101") (pin "90") (pinfunction "GND_44_90") (pintype "power_in"))
      (node (ref "U$101") (pin "91") (pinfunction "45_GND_91") (pintype "power_in"))
      (node (ref "U$101") (pin "92") (pinfunction "GND_46_92") (pintype "power_in"))
      (node (ref "U$101") (pin "93") (pinfunction "GND_93") (pintype "bidirectional"))
      (node (ref "U$101") (pin "P$1") (pinfunction "SCREW$1_P$1") (pintype "bidirectional"))
      (node (ref "U$101") (pin "P$2") (pinfunction "SCREW$2_P$2") (pintype "bidirectional"))
      (node (ref "U$101") (pin "P$3") (pinfunction "SCREW$3_P$3") (pintype "bidirectional"))
      (node (ref "U$101") (pin "P$4") (pinfunction "SCREW$4_P$4") (pintype "bidirectional"))
      (node (ref "U$101") (pin "TP8") (pinfunction "BATT_GND_TP8") (pintype "bidirectional"))
      (node (ref "U$11") (pin "2") (pinfunction "2_2") (pintype "passive"))
      (node (ref "U$11") (pin "P$3") (pinfunction "P$1_P$3") (pintype "bidirectional"))
      (node (ref "U$11") (pin "P$4") (pinfunction "P$2_P$4") (pintype "bidirectional"))
      (node (ref "U$12") (pin "P$4") (pinfunction "P$1_P$4") (pintype "bidirectional"))
      (node (ref "U$12") (pin "P$5") (pinfunction "P$2_P$5") (pintype "bidirectional"))
      (node (ref "U$2") (pin "6") (pinfunction "6_6") (pintype "passive"))
      (node (ref "U$2") (pin "P$7") (pinfunction "P$1_P$7") (pintype "bidirectional"))
      (node (ref "U$2") (pin "P$8") (pinfunction "P$2_P$8") (pintype "bidirectional"))
      (node (ref "U$201") (pin "6") (pinfunction "6_6") (pintype "passive"))
      (node (ref "U$201") (pin "P$7") (pinfunction "P$1_P$7") (pintype "bidirectional"))
      (node (ref "U$201") (pin "P$8") (pinfunction "P$2_P$8") (pintype "bidirectional"))
      (node (ref "U$4") (pin "6") (pinfunction "6_6") (pintype "passive"))
      (node (ref "U$4") (pin "P$7") (pinfunction "P$1_P$7") (pintype "bidirectional"))
      (node (ref "U$4") (pin "P$8") (pinfunction "P$2_P$8") (pintype "bidirectional"))
      (node (ref "U1") (pin "1") (pinfunction "A0_1") (pintype "bidirectional"))
      (node (ref "U1") (pin "2") (pinfunction "A1_2") (pintype "bidirectional"))
      (node (ref "U1") (pin "4") (pinfunction "VSS_4") (pintype "power_in"))
      (node (ref "U102") (pin "4") (pinfunction "VSS_4") (pintype "bidirectional"))
      (node (ref "U2") (pin "4") (pinfunction "VSS_4") (pintype "power_in"))
      (node (ref "U201") (pin "11") (pinfunction "GND_11") (pintype "power_in"))
      (node (ref "U301") (pin "2") (pinfunction "GND_2") (pintype "power_in"))
      (node (ref "U301") (pin "5") (pinfunction "SHDN_5") (pintype "input"))
      (node (ref "U302") (pin "11") (pinfunction "GND_11") (pintype "power_in"))
      (node (ref "U303") (pin "1") (pinfunction "GND_1") (pintype "bidirectional"))
      (node (ref "U401") (pin "2") (pinfunction "PS_2") (pintype "bidirectional"))
      (node (ref "U401") (pin "3") (pinfunction "GND_3") (pintype "bidirectional"))
      (node (ref "U403") (pin "1") (pinfunction "CLKIN_1") (pintype "bidirectional"))
      (node (ref "U403") (pin "11") (pinfunction "FSYNC_11") (pintype "bidirectional"))
      (node (ref "U403") (pin "18") (pinfunction "GND_18") (pintype "bidirectional"))
      (node (ref "U405") (pin "11") (pinfunction "FSYNC_11") (pintype "bidirectional"))
      (node (ref "U405") (pin "18") (pinfunction "GND_18") (pintype "bidirectional"))
      (node (ref "U405") (pin "20") (pinfunction "RESV_20") (pintype "bidirectional"))
      (node (ref "U406") (pin "2") (pinfunction "GND_2") (pintype "bidirectional"))
      (node (ref "U406") (pin "3") (pinfunction "GND_3") (pintype "bidirectional"))
      (node (ref "U406") (pin "4") (pinfunction "GND_4") (pintype "bidirectional"))
      (node (ref "U406") (pin "5") (pinfunction "GND_5") (pintype "bidirectional"))
      (node (ref "U406") (pin "6") (pinfunction "GND_6") (pintype "bidirectional"))
      (node (ref "U501") (pin "2") (pinfunction "VSS_2") (pintype "bidirectional"))
      (node (ref "U501") (pin "6") (pinfunction "VBAT_6") (pintype "bidirectional"))
      (node (ref "U501") (pin "GND") (pinfunction "VSS_GND") (pintype "bidirectional"))
      (node (ref "U501") (pin "P$2") (pinfunction "VSS_P$2") (pintype "bidirectional"))
      (node (ref "U501") (pin "P$3") (pinfunction "VSS_P$3") (pintype "bidirectional"))
      (node (ref "U502") (pin "2") (pinfunction "GND_2") (pintype "bidirectional"))
      (node (ref "U502") (pin "GND") (pinfunction "GND_GND") (pintype "bidirectional"))
      (node (ref "U503") (pin "2") (pinfunction "VSS_2") (pintype "bidirectional"))
      (node (ref "U503") (pin "6") (pinfunction "VBAT_6") (pintype "bidirectional"))
      (node (ref "U503") (pin "GND") (pinfunction "VSS_GND") (pintype "bidirectional"))
      (node (ref "U503") (pin "P$2") (pinfunction "VSS_P$2") (pintype "bidirectional"))
      (node (ref "U503") (pin "P$3") (pinfunction "VSS_P$3") (pintype "bidirectional"))
      (node (ref "U602") (pin "4") (pinfunction "GND_4") (pintype "power_in"))
      (node (ref "U701") (pin "11") (pinfunction "GND_11") (pintype "power_in"))
      (node (ref "U702") (pin "11") (pinfunction "GND_11") (pintype "power_in"))
      (node (ref "U704") (pin "12") (pinfunction "GND_12") (pintype "bidirectional"))
      (node (ref "U704") (pin "15") (pinfunction "GND_15") (pintype "bidirectional"))
      (node (ref "U704") (pin "18") (pinfunction "GND_18") (pintype "bidirectional"))
      (node (ref "U704") (pin "21") (pinfunction "GND_21") (pintype "bidirectional"))
      (node (ref "U704") (pin "24") (pinfunction "GND_24") (pintype "bidirectional"))
      (node (ref "U704") (pin "27") (pinfunction "GND_27") (pintype "bidirectional"))
      (node (ref "U704") (pin "3") (pinfunction "GND_3") (pintype "bidirectional"))
      (node (ref "U704") (pin "30") (pinfunction "GND_30") (pintype "bidirectional"))
      (node (ref "U704") (pin "33") (pinfunction "GND_33") (pintype "bidirectional"))
      (node (ref "U704") (pin "36") (pinfunction "GND_36") (pintype "bidirectional"))
      (node (ref "U704") (pin "39") (pinfunction "GND_39") (pintype "bidirectional"))
      (node (ref "U704") (pin "42") (pinfunction "GND_42") (pintype "bidirectional"))
      (node (ref "U704") (pin "6") (pinfunction "GND_6") (pintype "bidirectional"))
      (node (ref "U704") (pin "9") (pinfunction "GND_9") (pintype "bidirectional"))
      (node (ref "U802") (pin "2") (pinfunction "GND_2") (pintype "bidirectional"))
      (node (ref "U802") (pin "4") (pinfunction "EN2_4") (pintype "bidirectional"))
      (node (ref "U802") (pin "GND") (pinfunction "GND_GND") (pintype "bidirectional"))
      (node (ref "X801") (pin "4") (pinfunction "S_4") (pintype "passive"))
    )
    (net (code "42") (name "GYRO_DRDY") (class "Default")
      (node (ref "U$101") (pin "34") (pinfunction "GPOI2[17]_34_34") (pintype "passive"))
      (node (ref "U406") (pin "12") (pinfunction "DRDY_G_12") (pintype "bidirectional"))
    )
    (net (code "43") (name "I2C2_SCL") (class "Default")
      (node (ref "R301") (pin "P$1") (pinfunction "1_P$1") (pintype "passive"))
      (node (ref "U$101") (pin "65") (pinfunction "19_I2C2_SCL_65") (pintype "passive"))
      (node (ref "U1") (pin "6") (pinfunction "SCL_6") (pintype "bidirectional"))
      (node (ref "U2") (pin "6") (pinfunction "SCL_6") (pintype "bidirectional"))
      (node (ref "U303") (pin "3") (pinfunction "SCL1_3") (pintype "bidirectional"))
    )
    (net (code "44") (name "I2C2_SDA") (class "Default")
      (node (ref "R302") (pin "P$1") (pinfunction "1_P$1") (pintype "passive"))
      (node (ref "U$101") (pin "66") (pinfunction "I2C2_SDA_20_66") (pintype "passive"))
      (node (ref "U1") (pin "5") (pinfunction "SDA_5") (pintype "bidirectional"))
      (node (ref "U2") (pin "5") (pinfunction "SDA_5") (pintype "bidirectional"))
      (node (ref "U303") (pin "4") (pinfunction "SDA1_4") (pintype "bidirectional"))
    )
    (net (code "45") (name "MAG_DRDY") (class "Default")
      (node (ref "U$101") (pin "10") (pinfunction "GPIO2[4]_10_10") (pintype "passive"))
      (node (ref "U406") (pin "13") (pinfunction "INT1_XM_13") (pintype "bidirectional"))
    )
    (net (code "46") (name "MPU_6000_DRDY") (class "Default")
      (node (ref "U$101") (pin "14") (pinfunction "GPIO0[26]_14_14") (pintype "passive"))
      (node (ref "U403") (pin "12") (pinfunction "INT_12") (pintype "bidirectional"))
    )
    (net (code "47") (name "MPU_6500_DRDY") (class "Default")
      (node (ref "U$101") (pin "7") (pinfunction "7_GPIO2[2]_7") (pintype "passive"))
      (node (ref "U405") (pin "12") (pinfunction "INT_12") (pintype "bidirectional"))
    )
    (net (code "48") (name "Net-(C402-1)") (class "Default")
      (node (ref "C402") (pin "P$1") (pinfunction "1_P$1") (pintype "passive"))
      (node (ref "U406") (pin "7") (pinfunction "C1_XM_7") (pintype "bidirectional"))
    )
    (net (code "49") (name "Net-(C403-1)") (class "Default")
      (node (ref "C403") (pin "P$1") (pinfunction "1_P$1") (pintype "passive"))
      (node (ref "U406") (pin "8") (pinfunction "SETC_XM_8") (pintype "bidirectional"))
    )
    (net (code "50") (name "Net-(C403-2)") (class "Default")
      (node (ref "C403") (pin "P$2") (pinfunction "2_P$2") (pintype "passive"))
      (node (ref "U406") (pin "9") (pinfunction "SETP_XM_9") (pintype "bidirectional"))
    )
    (net (code "51") (name "Net-(C409-1)") (class "Default")
      (node (ref "C409") (pin "P$1") (pinfunction "1_P$1") (pintype "passive"))
      (node (ref "U403") (pin "10") (pinfunction "REGOUT_10") (pintype "bidirectional"))
    )
    (net (code "52") (name "Net-(C411-1)") (class "Default")
      (node (ref "C411") (pin "P$1") (pinfunction "1_P$1") (pintype "passive"))
      (node (ref "U405") (pin "10") (pinfunction "REGOUT_10") (pintype "bidirectional"))
    )
    (net (code "53") (name "Net-(C416-1)") (class "Default")
      (node (ref "C416") (pin "P$1") (pinfunction "1_P$1") (pintype "passive"))
      (node (ref "U403") (pin "20") (pinfunction "CPOUT_20") (pintype "bidirectional"))
    )
    (net (code "54") (name "Net-(C501-1)") (class "Default")
      (node (ref "C501") (pin "P$1") (pinfunction "1_P$1") (pintype "passive"))
      (node (ref "C502") (pin "P$1") (pinfunction "1_P$1") (pintype "passive"))
      (node (ref "L501") (pin "P$2") (pinfunction "P$2_P$2") (pintype "bidirectional"))
      (node (ref "U502") (pin "1") (pinfunction "VIN_1") (pintype "bidirectional"))
    )
    (net (code "55") (name "Net-(C503-1)") (class "Default")
      (node (ref "C503") (pin "P$1") (pinfunction "1_P$1") (pintype "passive"))
      (node (ref "U502") (pin "6") (pinfunction "CSET_6") (pintype "bidirectional"))
    )
    (net (code "56") (name "Net-(C603-1)") (class "Default")
      (node (ref "C603") (pin "P$1") (pinfunction "1_P$1") (pintype "passive"))
      (node (ref "R604") (pin "P$1") (pinfunction "1_P$1") (pintype "passive"))
      (node (ref "U$11") (pin "1") (pinfunction "1_1") (pintype "passive"))
      (node (ref "U602") (pin "1") (pinfunction "OUT_1") (pintype "output"))
    )
    (net (code "57") (name "Net-(C604-1)") (class "Default")
      (node (ref "C604") (pin "P$1") (pinfunction "1_P$1") (pintype "passive"))
      (node (ref "R606") (pin "P$1") (pinfunction "1_P$1") (pintype "passive"))
      (node (ref "R614") (pin "P$1") (pinfunction "1_P$1") (pintype "passive"))
      (node (ref "U602") (pin "6") (pinfunction "VCC_6") (pintype "bidirectional"))
    )
    (net (code "58") (name "Net-(D201-PadC)") (class "Default")
      (node (ref "D201") (pin "C") (pinfunction "C_C") (pintype "passive"))
      (node (ref "L201") (pin "P$2") (pinfunction "P$2_P$2") (pintype "bidirectional"))
      (node (ref "U$201") (pin "1") (pinfunction "1_1") (pintype "passive"))
    )
    (net (code "59") (name "Net-(D202-PadC)") (class "Default")
      (node (ref "D202") (pin "C") (pinfunction "C_C") (pintype "passive"))
      (node (ref "L202") (pin "P$2") (pinfunction "P$2_P$2") (pintype "bidirectional"))
      (node (ref "U$2") (pin "1") (pinfunction "1_1") (pintype "passive"))
    )
    (net (code "60") (name "Net-(D203-PadC)") (class "Default")
      (node (ref "D203") (pin "C") (pinfunction "C_C") (pintype "passive"))
      (node (ref "L203") (pin "P$2") (pinfunction "P$2_P$2") (pintype "bidirectional"))
      (node (ref "U$4") (pin "1") (pinfunction "1_1") (pintype "passive"))
    )
    (net (code "61") (name "Net-(D301-PadC)") (class "Default")
      (node (ref "D301") (pin "C") (pinfunction "C_C") (pintype "passive"))
      (node (ref "J305") (pin "1") (pinfunction "1_1") (pintype "passive"))
      (node (ref "J306") (pin "1") (pinfunction "1_1") (pintype "passive"))
      (node (ref "J310") (pin "1") (pinfunction "1_1") (pintype "passive"))
      (node (ref "J314") (pin "1") (pinfunction "1_1") (pintype "passive"))
      (node (ref "L301") (pin "P$2") (pinfunction "P$2_P$2") (pintype "bidirectional"))
    )
    (net (code "62") (name "Net-(D302-PadC)") (class "Default")
      (node (ref "D302") (pin "C") (pinfunction "C_C") (pintype "passive"))
      (node (ref "J309") (pin "1") (pinfunction "1_1") (pintype "passive"))
      (node (ref "L302") (pin "P$2") (pinfunction "P$2_P$2") (pintype "bidirectional"))
    )
    (net (code "63") (name "Net-(D303-PadC)") (class "Default")
      (node (ref "D303") (pin "C") (pinfunction "C_C") (pintype "passive"))
      (node (ref "J307") (pin "1") (pinfunction "1_1") (pintype "passive"))
      (node (ref "L303") (pin "P$2") (pinfunction "P$2_P$2") (pintype "bidirectional"))
    )
    (net (code "64") (name "Net-(D704-A)") (class "Default")
      (node (ref "D704") (pin "ANODE") (pinfunction "A_ANODE") (pintype "passive"))
      (node (ref "D705") (pin "ANODE") (pinfunction "A_ANODE") (pintype "passive"))
      (node (ref "F701") (pin "2") (pinfunction "2_2") (pintype "bidirectional"))
      (node (ref "R3") (pin "P$2") (pinfunction "2_P$2") (pintype "passive"))
      (node (ref "U704") (pin "11") (pinfunction "5V_11") (pintype "bidirectional"))
      (node (ref "U704") (pin "14") (pinfunction "5V_14") (pintype "bidirectional"))
      (node (ref "U704") (pin "17") (pinfunction "5V_17") (pintype "bidirectional"))
      (node (ref "U704") (pin "2") (pinfunction "5V_2") (pintype "bidirectional"))
      (node (ref "U704") (pin "20") (pinfunction "5V_20") (pintype "bidirectional"))
      (node (ref "U704") (pin "23") (pinfunction "5V_23") (pintype "bidirectional"))
      (node (ref "U704") (pin "26") (pinfunction "5V_26") (pintype "bidirectional"))
      (node (ref "U704") (pin "29") (pinfunction "5V_29") (pintype "bidirectional"))
      (node (ref "U704") (pin "32") (pinfunction "5V_32") (pintype "bidirectional"))
      (node (ref "U704") (pin "35") (pinfunction "5V_35") (pintype "bidirectional"))
      (node (ref "U704") (pin "38") (pinfunction "5V_38") (pintype "bidirectional"))
      (node (ref "U704") (pin "41") (pinfunction "5V_41") (pintype "bidirectional"))
      (node (ref "U704") (pin "5") (pinfunction "5V_5") (pintype "bidirectional"))
      (node (ref "U704") (pin "8") (pinfunction "5V_8") (pintype "bidirectional"))
    )
    (net (code "65") (name "Net-(D704-C)") (class "Default")
      (node (ref "D704") (pin "CATHODE") (pinfunction "C_CATHODE") (pintype "passive"))
      (node (ref "D705") (pin "CATHODE") (pinfunction "C_CATHODE") (pintype "passive"))
      (node (ref "D706") (pin "C") (pinfunction "C_C") (pintype "passive"))
      (node (ref "L701") (pin "P$1") (pinfunction "P$1_P$1") (pintype "bidirectional"))
    )
    (net (code "66") (name "Net-(L601-2)") (class "Default")
      (node (ref "L601") (pin "P$2") (pinfunction "2_P$2") (pintype "passive"))
      (node (ref "U602") (pin "5") (pinfunction "SW_5") (pintype "passive"))
    )
    (net (code "67") (name "Net-(Q501-PadC)") (class "Default")
      (node (ref "Q501") (pin "C") (pinfunction "C_C") (pintype "passive"))
      (node (ref "R505") (pin "2") (pinfunction "2_2") (pintype "passive"))
    )
    (net (code "68") (name "Net-(R1-2)") (class "Default")
      (node (ref "R1") (pin "P$2") (pinfunction "2_P$2") (pintype "passive"))
      (node (ref "R804") (pin "P$1") (pinfunction "1_P$1") (pintype "passive"))
    )
    (net (code "69") (name "Net-(R2-2)") (class "Default")
      (node (ref "R2") (pin "P$2") (pinfunction "2_P$2") (pintype "passive"))
      (node (ref "R805") (pin "P$1") (pinfunction "1_P$1") (pintype "passive"))
    )
    (net (code "70") (name "Net-(R4-2)") (class "Default")
      (node (ref "R4") (pin "P$2") (pinfunction "2_P$2") (pintype "passive"))
      (node (ref "R508") (pin "P$1") (pinfunction "1_P$1") (pintype "passive"))
    )
    (net (code "71") (name "Net-(R8-2)") (class "Default")
      (node (ref "R8") (pin "P$2") (pinfunction "2_P$2") (pintype "passive"))
      (node (ref "R9") (pin "P$1") (pinfunction "1_P$1") (pintype "passive"))
    )
    (net (code "72") (name "Net-(R103-1)") (class "Default")
      (node (ref "R103") (pin "P$1") (pinfunction "1_P$1") (pintype "passive"))
      (node (ref "U1") (pin "3") (pinfunction "A2_3") (pintype "bidirectional"))
    )
    (net (code "73") (name "Net-(R201-1)") (class "Default")
      (node (ref "R201") (pin "P$1") (pinfunction "1_P$1") (pintype "passive"))
      (node (ref "U201") (pin "20") (pinfunction "B1_20") (pintype "bidirectional"))
    )
    (net (code "74") (name "Net-(R202-1)") (class "Default")
      (node (ref "R202") (pin "P$1") (pinfunction "1_P$1") (pintype "passive"))
      (node (ref "U201") (pin "17") (pinfunction "B3_17") (pintype "bidirectional"))
    )
    (net (code "75") (name "Net-(R203-1)") (class "Default")
      (node (ref "R203") (pin "P$1") (pinfunction "1_P$1") (pintype "passive"))
      (node (ref "U201") (pin "15") (pinfunction "B5_15") (pintype "bidirectional"))
    )
    (net (code "76") (name "Net-(R204-1)") (class "Default")
      (node (ref "R204") (pin "P$1") (pinfunction "1_P$1") (pintype "passive"))
      (node (ref "U201") (pin "13") (pinfunction "B7_13") (pintype "bidirectional"))
    )
    (net (code "77") (name "Net-(R208-1)") (class "Default")
      (node (ref "R208") (pin "P$1") (pinfunction "1_P$1") (pintype "passive"))
      (node (ref "U201") (pin "18") (pinfunction "B2_18") (pintype "bidirectional"))
    )
    (net (code "78") (name "Net-(R209-1)") (class "Default")
      (node (ref "R209") (pin "P$1") (pinfunction "1_P$1") (pintype "passive"))
      (node (ref "U201") (pin "16") (pinfunction "B4_16") (pintype "bidirectional"))
    )
    (net (code "79") (name "Net-(R210-1)") (class "Default")
      (node (ref "R210") (pin "P$1") (pinfunction "1_P$1") (pintype "passive"))
      (node (ref "U201") (pin "14") (pinfunction "B6_14") (pintype "bidirectional"))
    )
    (net (code "80") (name "Net-(R211-1)") (class "Default")
      (node (ref "R211") (pin "P$1") (pinfunction "1_P$1") (pintype "passive"))
      (node (ref "U201") (pin "12") (pinfunction "B8_12") (pintype "bidirectional"))
    )
    (net (code "81") (name "Net-(R304-2)") (class "Default")
      (node (ref "J306") (pin "3") (pinfunction "3_3") (pintype "passive"))
      (node (ref "J310") (pin "3") (pinfunction "3_3") (pintype "passive"))
      (node (ref "J314") (pin "3") (pinfunction "3_3") (pintype "passive"))
      (node (ref "R304") (pin "P$2") (pinfunction "2_P$2") (pintype "passive"))
      (node (ref "U303") (pin "5") (pinfunction "SDA2_5") (pintype "bidirectional"))
    )
    (net (code "82") (name "Net-(R305-2)") (class "Default")
      (node (ref "J306") (pin "2") (pinfunction "2_2") (pintype "passive"))
      (node (ref "J310") (pin "2") (pinfunction "2_2") (pintype "passive"))
      (node (ref "J314") (pin "2") (pinfunction "2_2") (pintype "passive"))
      (node (ref "R305") (pin "P$2") (pinfunction "2_P$2") (pintype "passive"))
      (node (ref "U303") (pin "6") (pinfunction "SCL2_6") (pintype "bidirectional"))
    )
    (net (code "83") (name "Net-(R306-2)") (class "Default")
      (node (ref "R306") (pin "P$2") (pinfunction "2_P$2") (pintype "passive"))
      (node (ref "R7") (pin "P$1") (pinfunction "1_P$1") (pintype "passive"))
    )
    (net (code "84") (name "Net-(R307-2)") (class "Default")
      (node (ref "R307") (pin "P$2") (pinfunction "2_P$2") (pintype "passive"))
      (node (ref "R5") (pin "P$1") (pinfunction "1_P$1") (pintype "passive"))
    )
    (net (code "85") (name "Net-(R308-2)") (class "Default")
      (node (ref "R308") (pin "P$2") (pinfunction "2_P$2") (pintype "passive"))
      (node (ref "R6") (pin "P$1") (pinfunction "1_P$1") (pintype "passive"))
    )
    (net (code "86") (name "Net-(R310-2)") (class "Default")
      (node (ref "J309") (pin "2") (pinfunction "2_2") (pintype "passive"))
      (node (ref "R310") (pin "P$2") (pinfunction "2_P$2") (pintype "passive"))
      (node (ref "R5") (pin "P$2") (pinfunction "2_P$2") (pintype "passive"))
    )
    (net (code "87") (name "Net-(R311-2)") (class "Default")
      (node (ref "J309") (pin "4") (pinfunction "4_4") (pintype "passive"))
      (node (ref "R311") (pin "P$2") (pinfunction "2_P$2") (pintype "passive"))
      (node (ref "R6") (pin "P$2") (pinfunction "2_P$2") (pintype "passive"))
    )
    (net (code "88") (name "Net-(R312-1)") (class "Default")
      (node (ref "R312") (pin "P$1") (pinfunction "1_P$1") (pintype "passive"))
      (node (ref "U302") (pin "18") (pinfunction "B2_18") (pintype "bidirectional"))
    )
    (net (code "89") (name "Net-(R312-2)") (class "Default")
      (node (ref "J308") (pin "3") (pinfunction "3_3") (pintype "passive"))
      (node (ref "R312") (pin "P$2") (pinfunction "2_P$2") (pintype "passive"))
    )
    (net (code "90") (name "Net-(R313-1)") (class "Default")
      (node (ref "R313") (pin "P$1") (pinfunction "1_P$1") (pintype "passive"))
      (node (ref "U302") (pin "20") (pinfunction "B1_20") (pintype "bidirectional"))
    )
    (net (code "91") (name "Net-(R313-2)") (class "Default")
      (node (ref "J308") (pin "2") (pinfunction "2_2") (pintype "passive"))
      (node (ref "R313") (pin "P$2") (pinfunction "2_P$2") (pintype "passive"))
    )
    (net (code "92") (name "Net-(R315-1)") (class "Default")
      (node (ref "R315") (pin "P$1") (pinfunction "1_P$1") (pintype "passive"))
      (node (ref "U301") (pin "8") (pinfunction "RS_8") (pintype "input"))
    )
    (net (code "93") (name "Net-(R501-1)") (class "Default")
      (node (ref "R501") (pin "P$1") (pinfunction "1_P$1") (pintype "passive"))
      (node (ref "U501") (pin "7") (pinfunction "ILIM_7") (pintype "bidirectional"))
    )
    (net (code "94") (name "Net-(R503-1)") (class "Default")
      (node (ref "Q501") (pin "B") (pinfunction "B_B") (pintype "passive"))
      (node (ref "R503") (pin "P$1") (pinfunction "1_P$1") (pintype "passive"))
    )
    (net (code "95") (name "Net-(R504-1)") (class "Default")
      (node (ref "R504") (pin "P$1") (pinfunction "1_P$1") (pintype "passive"))
      (node (ref "U503") (pin "7") (pinfunction "ILIM_7") (pintype "bidirectional"))
    )
    (net (code "96") (name "Net-(R602-1)") (class "Default")
      (node (ref "R602") (pin "P$1") (pinfunction "1_P$1") (pintype "passive"))
      (node (ref "U602") (pin "7") (pinfunction "+IN_7") (pintype "input"))
    )
    (net (code "97") (name "Net-(R603-1)") (class "Default")
      (node (ref "R603") (pin "P$1") (pinfunction "1_P$1") (pintype "passive"))
      (node (ref "R604") (pin "P$2") (pinfunction "2_P$2") (pintype "passive"))
      (node (ref "U602") (pin "8") (pinfunction "-IN_8") (pintype "input"))
    )
    (net (code "98") (name "Net-(R606-2)") (class "Default")
      (node (ref "JP600") (pin "2") (pinfunction "2_2") (pintype "passive"))
      (node (ref "R606") (pin "P$2") (pinfunction "2_P$2") (pintype "passive"))
      (node (ref "R607") (pin "P$1") (pinfunction "1_P$1") (pintype "passive"))
      (node (ref "U602") (pin "2") (pinfunction "FB_2") (pintype "bidirectional"))
    )
    (net (code "99") (name "Net-(R608-2)") (class "Default")
      (node (ref "LED601") (pin "C") (pinfunction "C_C") (pintype "passive"))
      (node (ref "R608") (pin "P$2") (pinfunction "2_P$2") (pintype "passive"))
    )
    (net (code "100") (name "Net-(R609-1)") (class "Default")
      (node (ref "R609") (pin "P$1") (pinfunction "1_P$1") (pintype "passive"))
      (node (ref "R610") (pin "P$2") (pinfunction "2_P$2") (pintype "passive"))
    )
    (net (code "101") (name "Net-(R609-2)") (class "Default")
      (node (ref "LED602") (pin "C") (pinfunction "C_C") (pintype "passive"))
      (node (ref "R609") (pin "P$2") (pinfunction "2_P$2") (pintype "passive"))
    )
    (net (code "102") (name "Net-(R611-1)") (class "Default")
      (node (ref "R611") (pin "P$1") (pinfunction "1_P$1") (pintype "passive"))
      (node (ref "U$12") (pin "2") (pinfunction "2_2") (pintype "passive"))
    )
    (net (code "103") (name "Net-(R612-2)") (class "Default")
      (node (ref "LED603") (pin "C") (pinfunction "C_C") (pintype "passive"))
      (node (ref "R612") (pin "P$2") (pinfunction "2_P$2") (pintype "passive"))
    )
    (net (code "104") (name "Net-(R614-2)") (class "Default")
      (node (ref "JP600") (pin "1") (pinfunction "1_1") (pintype "passive"))
      (node (ref "R614") (pin "P$2") (pinfunction "2_P$2") (pintype "passive"))
    )
    (net (code "105") (name "Net-(R701-2)") (class "Default")
      (node (ref "R701") (pin "P$2") (pinfunction "2_P$2") (pintype "passive"))
      (node (ref "U704") (pin "10") (pinfunction "CH4_10") (pintype "bidirectional"))
    )
    (net (code "106") (name "Net-(R702-2)") (class "Default")
      (node (ref "R702") (pin "P$2") (pinfunction "2_P$2") (pintype "passive"))
      (node (ref "U704") (pin "13") (pinfunction "CH5_13") (pintype "bidirectional"))
    )
    (net (code "107") (name "Net-(R703-2)") (class "Default")
      (node (ref "R703") (pin "P$2") (pinfunction "2_P$2") (pintype "passive"))
      (node (ref "U704") (pin "16") (pinfunction "CH6_16") (pintype "bidirectional"))
    )
    (net (code "108") (name "Net-(R704-2)") (class "Default")
      (node (ref "R704") (pin "P$2") (pinfunction "2_P$2") (pintype "passive"))
      (node (ref "U704") (pin "19") (pinfunction "CH7_19") (pintype "bidirectional"))
    )
    (net (code "109") (name "Net-(R705-2)") (class "Default")
      (node (ref "R705") (pin "P$2") (pinfunction "2_P$2") (pintype "passive"))
      (node (ref "U704") (pin "22") (pinfunction "CH8_22") (pintype "bidirectional"))
    )
    (net (code "110") (name "Net-(R706-2)") (class "Default")
      (node (ref "R706") (pin "P$2") (pinfunction "2_P$2") (pintype "passive"))
      (node (ref "U704") (pin "25") (pinfunction "CH9_25") (pintype "bidirectional"))
    )
    (net (code "111") (name "Net-(R707-2)") (class "Default")
      (node (ref "R707") (pin "P$2") (pinfunction "2_P$2") (pintype "passive"))
      (node (ref "U704") (pin "28") (pinfunction "CH10_28") (pintype "bidirectional"))
    )
    (net (code "112") (name "Net-(R708-2)") (class "Default")
      (node (ref "R708") (pin "P$2") (pinfunction "2_P$2") (pintype "passive"))
      (node (ref "U704") (pin "31") (pinfunction "CH11_31") (pintype "bidirectional"))
    )
    (net (code "113") (name "Net-(R709-2)") (class "Default")
      (node (ref "R709") (pin "P$2") (pinfunction "2_P$2") (pintype "passive"))
      (node (ref "U704") (pin "34") (pinfunction "CH12_34") (pintype "bidirectional"))
    )
    (net (code "114") (name "Net-(R710-2)") (class "Default")
      (node (ref "R710") (pin "P$2") (pinfunction "2_P$2") (pintype "passive"))
      (node (ref "U704") (pin "37") (pinfunction "PPM/S.BUS_OUT_37") (pintype "bidirectional"))
    )
    (net (code "115") (name "Net-(R711-2)") (class "Default")
      (node (ref "R711") (pin "P$2") (pinfunction "2_P$2") (pintype "passive"))
      (node (ref "U704") (pin "40") (pinfunction "PPM/S.BUS_IN_40") (pintype "bidirectional"))
    )
    (net (code "116") (name "Net-(R712-2)") (class "Default")
      (node (ref "R712") (pin "P$2") (pinfunction "2_P$2") (pintype "passive"))
      (node (ref "U704") (pin "7") (pinfunction "CH3_7") (pintype "bidirectional"))
    )
    (net (code "117") (name "Net-(R713-2)") (class "Default")
      (node (ref "R713") (pin "P$2") (pinfunction "2_P$2") (pintype "passive"))
      (node (ref "U704") (pin "4") (pinfunction "CH2_4") (pintype "bidirectional"))
    )
    (net (code "118") (name "Net-(R714-2)") (class "Default")
      (node (ref "R714") (pin "P$2") (pinfunction "2_P$2") (pintype "passive"))
      (node (ref "U704") (pin "1") (pinfunction "CH1_1") (pintype "bidirectional"))
    )
    (net (code "119") (name "Net-(R801-1)") (class "Default")
      (node (ref "J801") (pin "4") (pinfunction "4_4") (pintype "passive"))
      (node (ref "L802") (pin "P$1") (pinfunction "P$1_P$1") (pintype "bidirectional"))
      (node (ref "R801") (pin "P$1") (pinfunction "1_P$1") (pintype "passive"))
    )
    (net (code "120") (name "Net-(R802-1)") (class "Default")
      (node (ref "J801") (pin "3") (pinfunction "3_3") (pintype "passive"))
      (node (ref "L801") (pin "P$1") (pinfunction "P$1_P$1") (pintype "bidirectional"))
      (node (ref "R802") (pin "P$1") (pinfunction "1_P$1") (pintype "passive"))
    )
    (net (code "121") (name "Net-(R804-2)") (class "Default")
      (node (ref "L801") (pin "P$2") (pinfunction "P$2_P$2") (pintype "bidirectional"))
      (node (ref "R804") (pin "P$2") (pinfunction "2_P$2") (pintype "passive"))
    )
    (net (code "122") (name "Net-(R805-2)") (class "Default")
      (node (ref "L802") (pin "P$2") (pinfunction "P$2_P$2") (pintype "bidirectional"))
      (node (ref "R805") (pin "P$2") (pinfunction "2_P$2") (pintype "passive"))
    )
    (net (code "123") (name "Net-(U302-VCCB)") (class "Default")
      (node (ref "J308") (pin "1") (pinfunction "1_1") (pintype "passive"))
      (node (ref "JP1") (pin "1") (pinfunction "1_1") (pintype "passive"))
      (node (ref "U302") (pin "19") (pinfunction "VCCB_19") (pintype "input"))
    )
    (net (code "124") (name "OUTPUT_EN") (class "Default")
      (node (ref "R806") (pin "P$2") (pinfunction "2_P$2") (pintype "passive"))
      (node (ref "R9") (pin "P$2") (pinfunction "2_P$2") (pintype "passive"))
      (node (ref "U201") (pin "10") (pinfunction "OE_10") (pintype "input"))
      (node (ref "U502") (pin "3") (pinfunction "POR2_3") (pintype "bidirectional"))
      (node (ref "U701") (pin "10") (pinfunction "OE_10") (pintype "input"))
      (node (ref "U702") (pin "10") (pinfunction "OE_10") (pintype "input"))
      (node (ref "U802") (pin "5") (pinfunction "EN1_5") (pintype "bidirectional"))
    )
    (net (code "125") (name "PPM{slash}S.BUS_INPUT") (class "Default")
      (node (ref "J701") (pin "P$3") (pinfunction "P$3_P$3") (pintype "bidirectional"))
      (node (ref "R711") (pin "P$1") (pinfunction "1_P$1") (pintype "passive"))
      (node (ref "U$101") (pin "15") (pinfunction "15_PRU0_R31[15]_15") (pintype "passive"))
    )
    (net (code "126") (name "PPM{slash}S.BUS_OUT") (class "Default")
      (node (ref "R710") (pin "P$1") (pinfunction "1_P$1") (pintype "passive"))
      (node (ref "U$101") (pin "11") (pinfunction "11_PRU0_R30[15]_11") (pintype "passive"))
    )
    (net (code "127") (name "PRESSURE_SENS") (class "Default")
      (node (ref "C301") (pin "P$1") (pinfunction "1_P$1") (pintype "passive"))
      (node (ref "R303") (pin "P$2") (pinfunction "2_P$2") (pintype "passive"))
      (node (ref "R306") (pin "P$1") (pinfunction "1_P$1") (pintype "passive"))
      (node (ref "U$101") (pin "86") (pinfunction "AIN1_40_86") (pintype "passive"))
    )
    (net (code "128") (name "PRESSURE_SENS_IN") (class "Default")
      (node (ref "ADC_PR") (pin "P$1") (pinfunction "P$1_P$1") (pintype "passive"))
      (node (ref "J305") (pin "2") (pinfunction "2_2") (pintype "passive"))
      (node (ref "R7") (pin "P$2") (pinfunction "2_P$2") (pintype "passive"))
    )
    (net (code "129") (name "SAFETY") (class "Default")
      (node (ref "R613") (pin "P$1") (pinfunction "1_P$1") (pintype "passive"))
      (node (ref "U$101") (pin "87") (pinfunction "41_PRU0_R30/31[6]_87") (pintype "input"))
      (node (ref "U$12") (pin "3") (pinfunction "3_3") (pintype "passive"))
    )
    (net (code "130") (name "SERVO_RAIL_IN_~{EN}") (class "Default")
      (node (ref "U$101") (pin "16") (pinfunction "PRU0_R31[14]_16_16") (pintype "passive"))
    )
    (net (code "131") (name "SPARE") (class "Default")
      (node (ref "U$101") (pin "17") (pinfunction "17_GPIO0[27]_17") (pintype "passive"))
    )
    (net (code "132") (name "SPI_0_MISO") (class "Default")
      (node (ref "U$101") (pin "64") (pinfunction "SPI_0_MISO_18_64") (pintype "passive"))
      (node (ref "U406") (pin "22") (pinfunction "SDO_G_22") (pintype "bidirectional"))
      (node (ref "U406") (pin "23") (pinfunction "SDO_XM_23") (pintype "bidirectional"))
    )
    (net (code "133") (name "SPI_0_MOSI") (class "Default")
      (node (ref "U$101") (pin "67") (pinfunction "21_SPI_0_MOSI_67") (pintype "passive"))
      (node (ref "U406") (pin "24") (pinfunction "SDA_24") (pintype "bidirectional"))
    )
    (net (code "134") (name "SPI_0_SCK") (class "Default")
      (node (ref "U$101") (pin "68") (pinfunction "SPI_0_SCLK_22_68") (pintype "passive"))
      (node (ref "U406") (pin "21") (pinfunction "SPC_21") (pintype "bidirectional"))
    )
    (net (code "135") (name "SPI_1_MISO") (class "Default")
      (node (ref "U$101") (pin "76") (pinfunction "SPI_1_MISO_30_76") (pintype "passive"))
      (node (ref "U102") (pin "2") (pinfunction "Q_2") (pintype "bidirectional"))
      (node (ref "U401") (pin "6") (pinfunction "SDO_6") (pintype "bidirectional"))
      (node (ref "U403") (pin "9") (pinfunction "AD0/SDO_9") (pintype "bidirectional"))
      (node (ref "U405") (pin "9") (pinfunction "AD0/SDO_9") (pintype "bidirectional"))
    )
    (net (code "136") (name "SPI_1_MOSI") (class "Default")
      (node (ref "U$101") (pin "75") (pinfunction "29_SPI_1_MOSI_75") (pintype "passive"))
      (node (ref "U102") (pin "5") (pinfunction "D_5") (pintype "bidirectional"))
      (node (ref "U401") (pin "7") (pinfunction "SDI/SDA_7") (pintype "bidirectional"))
      (node (ref "U403") (pin "24") (pinfunction "SDA/SDI_24") (pintype "bidirectional"))
      (node (ref "U405") (pin "24") (pinfunction "SDA/SDI_24") (pintype "bidirectional"))
    )
    (net (code "137") (name "SPI_1_SCK") (class "Default")
      (node (ref "U$101") (pin "77") (pinfunction "31_SPI_1_SCLK_77") (pintype "passive"))
      (node (ref "U102") (pin "6") (pinfunction "C_6") (pintype "bidirectional"))
      (node (ref "U401") (pin "8") (pinfunction "SCLK_8") (pintype "bidirectional"))
      (node (ref "U403") (pin "23") (pinfunction "SCL/SCLK_23") (pintype "bidirectional"))
      (node (ref "U405") (pin "23") (pinfunction "SCL/SCLK_23") (pintype "bidirectional"))
    )
    (net (code "138") (name "SPI_1_~{BARO_CS}") (class "Default")
      (node (ref "U$101") (pin "88") (pinfunction "SPI_1_CS1_42_88") (pintype "passive"))
      (node (ref "U401") (pin "5") (pinfunction "CSB2_5") (pintype "bidirectional"))
    )
    (net (code "139") (name "SPI_1_~{MPU_CS2}") (class "Default")
      (node (ref "U$101") (pin "69") (pinfunction "23_GPIO1[17]_69") (pintype "passive"))
      (node (ref "U405") (pin "22") (pinfunction "~{CS}_22") (pintype "bidirectional"))
    )
    (net (code "140") (name "SPI_1_~{MPU_CS}") (class "Default")
      (node (ref "U$101") (pin "74") (pinfunction "SPI_1_CS0_28_74") (pintype "passive"))
      (node (ref "U403") (pin "8") (pinfunction "/CS_8") (pintype "bidirectional"))
    )
    (net (code "141") (name "SYS_5V") (class "Default")
      (node (ref "F701") (pin "1") (pinfunction "1_1") (pintype "bidirectional"))
      (node (ref "L501") (pin "P$1") (pinfunction "P$1_P$1") (pintype "bidirectional"))
      (node (ref "R508") (pin "P$2") (pinfunction "2_P$2") (pintype "passive"))
      (node (ref "U$101") (pin "53") (pinfunction "7_SYS_5V_53") (pintype "power_in"))
      (node (ref "U$101") (pin "54") (pinfunction "SYS_5V_8_54") (pintype "passive"))
      (node (ref "U501") (pin "1") (pinfunction "IN_1") (pintype "bidirectional"))
      (node (ref "U503") (pin "1") (pinfunction "IN_1") (pintype "bidirectional"))
      (node (ref "U802") (pin "1") (pinfunction "VIN_1") (pintype "bidirectional"))
      (node (ref "VDD_5V_IN") (pin "P$1") (pinfunction "P$1_P$1") (pintype "passive"))
    )
    (net (code "142") (name "TTYO0_RX") (class "Default")
      (node (ref "R212") (pin "P$2") (pinfunction "2_P$2") (pintype "passive"))
      (node (ref "U$4") (pin "3") (pinfunction "3_3") (pintype "passive"))
    )
    (net (code "143") (name "TTYO0_TX") (class "Default")
      (node (ref "R205") (pin "P$2") (pinfunction "2_P$2") (pintype "passive"))
      (node (ref "U$4") (pin "2") (pinfunction "2_2") (pintype "passive"))
    )
    (net (code "144") (name "TTYO4_CTS") (class "Default")
      (node (ref "R211") (pin "P$2") (pinfunction "2_P$2") (pintype "passive"))
      (node (ref "U$201") (pin "4") (pinfunction "4_4") (pintype "passive"))
    )
    (net (code "145") (name "TTYO4_RTS") (class "Default")
      (node (ref "R204") (pin "P$2") (pinfunction "2_P$2") (pintype "passive"))
      (node (ref "U$201") (pin "5") (pinfunction "5_5") (pintype "passive"))
    )
    (net (code "146") (name "TTYO4_RX") (class "Default")
      (node (ref "R203") (pin "P$2") (pinfunction "2_P$2") (pintype "passive"))
      (node (ref "S1RX") (pin "P$1") (pinfunction "P$1_P$1") (pintype "passive"))
      (node (ref "U$201") (pin "3") (pinfunction "3_3") (pintype "passive"))
    )
    (net (code "147") (name "TTYO4_TX") (class "Default")
      (node (ref "R210") (pin "P$2") (pinfunction "2_P$2") (pintype "passive"))
      (node (ref "S1TX") (pin "P$1") (pinfunction "P$1_P$1") (pintype "passive"))
      (node (ref "U$201") (pin "2") (pinfunction "2_2") (pintype "passive"))
    )
    (net (code "148") (name "TTYO5_CTS") (class "Default")
      (node (ref "R208") (pin "P$2") (pinfunction "2_P$2") (pintype "passive"))
      (node (ref "U$2") (pin "4") (pinfunction "4_4") (pintype "passive"))
    )
    (net (code "149") (name "TTYO5_RTS") (class "Default")
      (node (ref "R201") (pin "P$2") (pinfunction "2_P$2") (pintype "passive"))
      (node (ref "U$2") (pin "5") (pinfunction "5_5") (pintype "passive"))
    )
    (net (code "150") (name "TTYO5_RX") (class "Default")
      (node (ref "R202") (pin "P$2") (pinfunction "2_P$2") (pintype "passive"))
      (node (ref "S2RX") (pin "P$1") (pinfunction "P$1_P$1") (pintype "passive"))
      (node (ref "U$2") (pin "3") (pinfunction "3_3") (pintype "passive"))
    )
    (net (code "151") (name "TTYO5_TX") (class "Default")
      (node (ref "R209") (pin "P$2") (pinfunction "2_P$2") (pintype "passive"))
      (node (ref "S2TX") (pin "P$1") (pinfunction "P$1_P$1") (pintype "passive"))
      (node (ref "U$2") (pin "2") (pinfunction "2_2") (pintype "passive"))
    )
    (net (code "152") (name "UART0_RX") (class "Default")
      (node (ref "R212") (pin "P$1") (pinfunction "1_P$1") (pintype "passive"))
      (node (ref "U$101") (pin "97") (pinfunction "UART0_RXD_97") (pintype "bidirectional"))
    )
    (net (code "153") (name "UART0_TX") (class "Default")
      (node (ref "R205") (pin "P$1") (pinfunction "1_P$1") (pintype "passive"))
      (node (ref "U$101") (pin "96") (pinfunction "UART0_TXD_96") (pintype "bidirectional"))
    )
    (net (code "154") (name "UBLED-SCL") (class "Default")
      (node (ref "U$101") (pin "60") (pinfunction "GPIO1[18]_14_60") (pintype "passive"))
      (node (ref "U302") (pin "3") (pinfunction "A2_3") (pintype "bidirectional"))
    )
    (net (code "155") (name "UBLED-SDA") (class "Default")
      (node (ref "U$101") (pin "62") (pinfunction "GPIO1[19]_16_62") (pintype "passive"))
      (node (ref "U302") (pin "1") (pinfunction "A1_1") (pintype "bidirectional"))
    )
    (net (code "156") (name "USART4_CTS") (class "Default")
      (node (ref "U$101") (pin "35") (pinfunction "35_UART4_CTSN_35") (pintype "passive"))
      (node (ref "U201") (pin "9") (pinfunction "A8_9") (pintype "bidirectional"))
    )
    (net (code "157") (name "USART4_RTS") (class "Default")
      (node (ref "U$101") (pin "33") (pinfunction "33_UART4_RTSN_33") (pintype "passive"))
      (node (ref "U201") (pin "8") (pinfunction "A7_8") (pintype "bidirectional"))
    )
    (net (code "158") (name "USART4_RX") (class "Default")
      (node (ref "U$101") (pin "57") (pinfunction "11_UART4_RXD_57") (pintype "passive"))
      (node (ref "U201") (pin "6") (pinfunction "A5_6") (pintype "bidirectional"))
    )
    (net (code "159") (name "USART4_TX") (class "Default")
      (node (ref "U$101") (pin "59") (pinfunction "13_UART4_TXD_59") (pintype "passive"))
      (node (ref "U201") (pin "7") (pinfunction "A6_7") (pintype "bidirectional"))
    )
    (net (code "160") (name "USART5_CTS") (class "Default")
      (node (ref "U$101") (pin "31") (pinfunction "31_UART5_CTSN_31") (pintype "passive"))
      (node (ref "U201") (pin "3") (pinfunction "A2_3") (pintype "bidirectional"))
    )
    (net (code "161") (name "USART5_RTS") (class "Default")
      (node (ref "U$101") (pin "32") (pinfunction "UART5_RTSN_32_32") (pintype "passive"))
      (node (ref "U201") (pin "1") (pinfunction "A1_1") (pintype "bidirectional"))
    )
    (net (code "162") (name "USART5_RX") (class "Default")
      (node (ref "U$101") (pin "38") (pinfunction "UART5_RXD_38_38") (pintype "passive"))
      (node (ref "U201") (pin "4") (pinfunction "A3_4") (pintype "bidirectional"))
    )
    (net (code "163") (name "USART5_TX") (class "Default")
      (node (ref "U$101") (pin "37") (pinfunction "37_UART5_TXD_37") (pintype "passive"))
      (node (ref "U201") (pin "5") (pinfunction "A4_5") (pintype "bidirectional"))
    )
    (net (code "164") (name "VDD_3V3_4") (class "Default")
      (node (ref "U$101") (pin "50") (pinfunction "VDD_3V3_4_50") (pintype "power_in"))
    )
    (net (code "165") (name "VDD_3V3_SENSORS") (class "Default")
      (node (ref "C101") (pin "P$1") (pinfunction "1_P$1") (pintype "passive"))
      (node (ref "C305") (pin "P$1") (pinfunction "1_P$1") (pintype "passive"))
      (node (ref "C401") (pin "P$1") (pinfunction "1_P$1") (pintype "passive"))
      (node (ref "C405") (pin "P$2") (pinfunction "2_P$2") (pintype "passive"))
      (node (ref "C406") (pin "P$2") (pinfunction "2_P$2") (pintype "passive"))
      (node (ref "C407") (pin "P$1") (pinfunction "1_P$1") (pintype "passive"))
      (node (ref "C408") (pin "P$1") (pinfunction "1_P$1") (pintype "passive"))
      (node (ref "C410") (pin "P$1") (pinfunction "1_P$1") (pintype "passive"))
      (node (ref "C412") (pin "P$1") (pinfunction "1_P$1") (pintype "passive"))
      (node (ref "C413") (pin "P$1") (pinfunction "1_P$1") (pintype "passive"))
      (node (ref "C414") (pin "P$1") (pinfunction "1_P$1") (pintype "passive"))
      (node (ref "C415") (pin "P$1") (pinfunction "1_P$1") (pintype "passive"))
      (node (ref "C508") (pin "P$1") (pinfunction "1_P$1") (pintype "passive"))
      (node (ref "C509") (pin "P$1") (pinfunction "1_P$1") (pintype "passive"))
      (node (ref "Q501") (pin "E") (pinfunction "E_E") (pintype "passive"))
      (node (ref "R103") (pin "P$2") (pinfunction "2_P$2") (pintype "passive"))
      (node (ref "U1") (pin "8") (pinfunction "VCC_8") (pintype "power_in"))
      (node (ref "U102") (pin "3") (pinfunction "~{W}_3") (pintype "bidirectional"))
      (node (ref "U102") (pin "7") (pinfunction "~{HOLD}_7") (pintype "bidirectional"))
      (node (ref "U102") (pin "8") (pinfunction "VDD_8") (pintype "bidirectional"))
      (node (ref "U2") (pin "8") (pinfunction "VCC_8") (pintype "power_in"))
      (node (ref "U401") (pin "1") (pinfunction "VDD_1") (pintype "bidirectional"))
      (node (ref "U403") (pin "13") (pinfunction "VDD_13") (pintype "bidirectional"))
      (node (ref "U405") (pin "1") (pinfunction "NC_1") (pintype "bidirectional"))
      (node (ref "U405") (pin "13") (pinfunction "VDD_13") (pintype "bidirectional"))
      (node (ref "U405") (pin "8") (pinfunction "VDDIO_8") (pintype "bidirectional"))
      (node (ref "U406") (pin "15") (pinfunction "VDD_15") (pintype "bidirectional"))
      (node (ref "U406") (pin "16") (pinfunction "VDD_16") (pintype "bidirectional"))
      (node (ref "U406") (pin "17") (pinfunction "VDD_17") (pintype "bidirectional"))
      (node (ref "U406") (pin "18") (pinfunction "VDD_IO_18") (pintype "bidirectional"))
      (node (ref "U502") (pin "8") (pinfunction "VOUT1_8") (pintype "bidirectional"))
      (node (ref "VDDA_3V901") (pin "P$1") (pinfunction "P$1_P$1") (pintype "passive"))
    )
    (net (code "166") (name "VDD_3V3_SPEKTRUM") (class "Default")
      (node (ref "C805") (pin "P$1") (pinfunction "1_P$1") (pintype "passive"))
      (node (ref "D703") (pin "C") (pinfunction "C_C") (pintype "passive"))
      (node (ref "J701") (pin "P$1") (pinfunction "P$1_P$1") (pintype "bidirectional"))
      (node (ref "U802") (pin "8") (pinfunction "VOUT1_8") (pintype "bidirectional"))
    )
    (net (code "167") (name "VDD_5V") (class "Default")
      (node (ref "C801") (pin "P$1") (pinfunction "1_P$1") (pintype "passive"))
      (node (ref "J801") (pin "1") (pinfunction "1_1") (pintype "passive"))
      (node (ref "J801") (pin "2") (pinfunction "2_2") (pintype "passive"))
      (node (ref "U$101") (pin "51") (pinfunction "5_VDD_5V_51") (pintype "power_in"))
      (node (ref "U$101") (pin "52") (pinfunction "VDD_5V_6_52") (pintype "power_in"))
      (node (ref "VDD_5V_BRICK") (pin "P$1") (pinfunction "P$1_P$1") (pintype "passive"))
    )
    (net (code "168") (name "VDD_5V_HIPOWER") (class "Default")
      (node (ref "C504") (pin "P$1") (pinfunction "1_P$1") (pintype "passive"))
      (node (ref "L201") (pin "P$1") (pinfunction "P$1_P$1") (pintype "bidirectional"))
      (node (ref "U501") (pin "8") (pinfunction "OUT_8") (pintype "bidirectional"))
    )
    (net (code "169") (name "VDD_5V_PERIPH") (class "Default")
      (node (ref "C510") (pin "P$1") (pinfunction "1_P$1") (pintype "passive"))
      (node (ref "C602") (pin "P$1") (pinfunction "1_P$1") (pintype "passive"))
      (node (ref "L202") (pin "P$1") (pinfunction "P$1_P$1") (pintype "bidirectional"))
      (node (ref "L203") (pin "P$1") (pinfunction "P$1_P$1") (pintype "bidirectional"))
      (node (ref "L301") (pin "P$1") (pinfunction "P$1_P$1") (pintype "bidirectional"))
      (node (ref "L302") (pin "P$1") (pinfunction "P$1_P$1") (pintype "bidirectional"))
      (node (ref "L303") (pin "P$1") (pinfunction "P$1_P$1") (pintype "bidirectional"))
      (node (ref "L601") (pin "P$1") (pinfunction "1_P$1") (pintype "passive"))
      (node (ref "LED601") (pin "A") (pinfunction "A_A") (pintype "passive"))
      (node (ref "LED602") (pin "A") (pinfunction "A_A") (pintype "passive"))
      (node (ref "LED603") (pin "A") (pinfunction "A_A") (pintype "passive"))
      (node (ref "U503") (pin "8") (pinfunction "OUT_8") (pintype "bidirectional"))
      (node (ref "U602") (pin "3") (pinfunction "VIN_3") (pintype "power_in"))
    )
    (net (code "170") (name "VDD_5V_SENS") (class "Default")
      (node (ref "R4") (pin "P$1") (pinfunction "1_P$1") (pintype "passive"))
      (node (ref "R509") (pin "P$1") (pinfunction "1_P$1") (pintype "passive"))
      (node (ref "U$101") (pin "79") (pinfunction "33_AIN4_79") (pintype "passive"))
    )
    (net (code "171") (name "VDD_SERVO_IN") (class "Default")
      (node (ref "L701") (pin "P$2") (pinfunction "P$2_P$2") (pintype "bidirectional"))
    )
    (net (code "172") (name "VDD_SERVO_SENS") (class "Default")
      (node (ref "R3") (pin "P$1") (pinfunction "1_P$1") (pintype "passive"))
      (node (ref "R716") (pin "P$2") (pinfunction "2_P$2") (pintype "passive"))
      (node (ref "U$101") (pin "85") (pinfunction "39_AIN0_85") (pintype "power_in"))
    )
    (net (code "173") (name "unconnected-(U$4-Pad4)") (class "Default")
      (node (ref "U$4") (pin "4") (pinfunction "4_4") (pintype "passive"))
    )
    (net (code "174") (name "unconnected-(U$4-Pad5)") (class "Default")
      (node (ref "U$4") (pin "5") (pinfunction "5_5") (pintype "passive"))
    )
    (net (code "175") (name "unconnected-(U$101-3_MMC1-Pad3)") (class "Default")
      (node (ref "U$101") (pin "3") (pinfunction "3_MMC1_3") (pintype "passive"))
    )
    (net (code "176") (name "unconnected-(U$101-5_MMC1-Pad5)") (class "Default")
      (node (ref "U$101") (pin "5") (pinfunction "5_MMC1_5") (pintype "passive"))
    )
    (net (code "177") (name "unconnected-(U$101-9_PWR_BUT-Pad55)") (class "Default")
      (node (ref "U$101") (pin "55") (pinfunction "9_PWR_BUT_55") (pintype "passive"))
    )
    (net (code "178") (name "unconnected-(U$101-21_MMC1-Pad21)") (class "Default")
      (node (ref "U$101") (pin "21") (pinfunction "21_MMC1_21") (pintype "passive"))
    )
    (net (code "179") (name "unconnected-(U$101-23_MMC1-Pad23)") (class "Default")
      (node (ref "U$101") (pin "23") (pinfunction "23_MMC1_23") (pintype "passive"))
    )
    (net (code "180") (name "unconnected-(U$101-25_MMC1-Pad25)") (class "Default")
      (node (ref "U$101") (pin "25") (pinfunction "25_MMC1_25") (pintype "passive"))
    )
    (net (code "181") (name "unconnected-(U$101-MMC1_3-Pad6)") (class "Default")
      (node (ref "U$101") (pin "6") (pinfunction "MMC1_3_6") (pintype "passive"))
    )
    (net (code "182") (name "unconnected-(U$101-MMC1_4-Pad4)") (class "Default")
      (node (ref "U$101") (pin "4") (pinfunction "MMC1_4_4") (pintype "passive"))
    )
    (net (code "183") (name "unconnected-(U$101-MMC1_20-Pad20)") (class "Default")
      (node (ref "U$101") (pin "20") (pinfunction "MMC1_20_20") (pintype "passive"))
    )
    (net (code "184") (name "unconnected-(U$101-MMC1_22-Pad22)") (class "Default")
      (node (ref "U$101") (pin "22") (pinfunction "MMC1_22_22") (pintype "passive"))
    )
    (net (code "185") (name "unconnected-(U$101-MMC1_24-Pad24)") (class "Default")
      (node (ref "U$101") (pin "24") (pinfunction "MMC1_24_24") (pintype "passive"))
    )
    (net (code "186") (name "unconnected-(U$101-NC-Pad94)") (class "Default")
      (node (ref "U$101") (pin "94") (pinfunction "NC_94") (pintype "bidirectional"))
    )
    (net (code "187") (name "unconnected-(U$101-NC-Pad95)") (class "Default")
      (node (ref "U$101") (pin "95") (pinfunction "NC_95") (pintype "bidirectional"))
    )
    (net (code "188") (name "unconnected-(U$101-NC-Pad98)") (class "Default")
      (node (ref "U$101") (pin "98") (pinfunction "NC_98") (pintype "bidirectional"))
    )
    (net (code "189") (name "unconnected-(U$101-VDD_ADC_32-Pad78)") (class "Default")
      (node (ref "U$101") (pin "78") (pinfunction "VDD_ADC_32_78") (pintype "passive"))
    )
    (net (code "190") (name "unconnected-(U1-WP-Pad7)") (class "Default")
      (node (ref "U1") (pin "7") (pinfunction "WP_7") (pintype "bidirectional"))
    )
    (net (code "191") (name "unconnected-(U2-A0-Pad1)") (class "Default")
      (node (ref "U2") (pin "1") (pinfunction "A0_1") (pintype "bidirectional"))
    )
    (net (code "192") (name "unconnected-(U2-A1-Pad2)") (class "Default")
      (node (ref "U2") (pin "2") (pinfunction "A1_2") (pintype "bidirectional"))
    )
    (net (code "193") (name "unconnected-(U2-A2-Pad3)") (class "Default")
      (node (ref "U2") (pin "3") (pinfunction "A2_3") (pintype "bidirectional"))
    )
    (net (code "194") (name "unconnected-(U2-WP-Pad7)") (class "Default")
      (node (ref "U2") (pin "7") (pinfunction "WP_7") (pintype "bidirectional"))
    )
    (net (code "195") (name "unconnected-(U302-A3-Pad4)") (class "Default")
      (node (ref "U302") (pin "4") (pinfunction "A3_4") (pintype "bidirectional"))
    )
    (net (code "196") (name "unconnected-(U302-A4-Pad5)") (class "Default")
      (node (ref "U302") (pin "5") (pinfunction "A4_5") (pintype "bidirectional"))
    )
    (net (code "197") (name "unconnected-(U302-A5-Pad6)") (class "Default")
      (node (ref "U302") (pin "6") (pinfunction "A5_6") (pintype "bidirectional"))
    )
    (net (code "198") (name "unconnected-(U302-A6-Pad7)") (class "Default")
      (node (ref "U302") (pin "7") (pinfunction "A6_7") (pintype "bidirectional"))
    )
    (net (code "199") (name "unconnected-(U302-A7-Pad8)") (class "Default")
      (node (ref "U302") (pin "8") (pinfunction "A7_8") (pintype "bidirectional"))
    )
    (net (code "200") (name "unconnected-(U302-A8-Pad9)") (class "Default")
      (node (ref "U302") (pin "9") (pinfunction "A8_9") (pintype "bidirectional"))
    )
    (net (code "201") (name "unconnected-(U302-B3-Pad17)") (class "Default")
      (node (ref "U302") (pin "17") (pinfunction "B3_17") (pintype "bidirectional"))
    )
    (net (code "202") (name "unconnected-(U302-B4-Pad16)") (class "Default")
      (node (ref "U302") (pin "16") (pinfunction "B4_16") (pintype "bidirectional"))
    )
    (net (code "203") (name "unconnected-(U302-B5-Pad15)") (class "Default")
      (node (ref "U302") (pin "15") (pinfunction "B5_15") (pintype "bidirectional"))
    )
    (net (code "204") (name "unconnected-(U302-B6-Pad14)") (class "Default")
      (node (ref "U302") (pin "14") (pinfunction "B6_14") (pintype "bidirectional"))
    )
    (net (code "205") (name "unconnected-(U302-B7-Pad13)") (class "Default")
      (node (ref "U302") (pin "13") (pinfunction "B7_13") (pintype "bidirectional"))
    )
    (net (code "206") (name "unconnected-(U302-B8-Pad12)") (class "Default")
      (node (ref "U302") (pin "12") (pinfunction "B8_12") (pintype "bidirectional"))
    )
    (net (code "207") (name "unconnected-(U401-CSB1-Pad4)") (class "Default")
      (node (ref "U401") (pin "4") (pinfunction "CSB1_4") (pintype "bidirectional"))
    )
    (net (code "208") (name "unconnected-(U403-AUX_CL-Pad7)") (class "Default")
      (node (ref "U403") (pin "7") (pinfunction "AUX_CL_7") (pintype "bidirectional"))
    )
    (net (code "209") (name "unconnected-(U403-AUX_DA-Pad6)") (class "Default")
      (node (ref "U403") (pin "6") (pinfunction "AUX_DA_6") (pintype "bidirectional"))
    )
    (net (code "210") (name "unconnected-(U403-CLKOUT-Pad22)") (class "Default")
      (node (ref "U403") (pin "22") (pinfunction "CLKOUT_22") (pintype "bidirectional"))
    )
    (net (code "211") (name "unconnected-(U403-NC1-Pad2)") (class "Default")
      (node (ref "U403") (pin "2") (pinfunction "NC1_2") (pintype "bidirectional"))
    )
    (net (code "212") (name "unconnected-(U403-NC2-Pad3)") (class "Default")
      (node (ref "U403") (pin "3") (pinfunction "NC2_3") (pintype "bidirectional"))
    )
    (net (code "213") (name "unconnected-(U403-NC3-Pad4)") (class "Default")
      (node (ref "U403") (pin "4") (pinfunction "NC3_4") (pintype "bidirectional"))
    )
    (net (code "214") (name "unconnected-(U403-NC4-Pad5)") (class "Default")
      (node (ref "U403") (pin "5") (pinfunction "NC4_5") (pintype "bidirectional"))
    )
    (net (code "215") (name "unconnected-(U403-NC5-Pad14)") (class "Default")
      (node (ref "U403") (pin "14") (pinfunction "NC5_14") (pintype "bidirectional"))
    )
    (net (code "216") (name "unconnected-(U403-NC6-Pad15)") (class "Default")
      (node (ref "U403") (pin "15") (pinfunction "NC6_15") (pintype "bidirectional"))
    )
    (net (code "217") (name "unconnected-(U403-NC7-Pad16)") (class "Default")
      (node (ref "U403") (pin "16") (pinfunction "NC7_16") (pintype "bidirectional"))
    )
    (net (code "218") (name "unconnected-(U403-NC8-Pad17)") (class "Default")
      (node (ref "U403") (pin "17") (pinfunction "NC8_17") (pintype "bidirectional"))
    )
    (net (code "219") (name "unconnected-(U403-RESV1-Pad19)") (class "Default")
      (node (ref "U403") (pin "19") (pinfunction "RESV1_19") (pintype "bidirectional"))
    )
    (net (code "220") (name "unconnected-(U403-RESV2-Pad21)") (class "Default")
      (node (ref "U403") (pin "21") (pinfunction "RESV2_21") (pintype "bidirectional"))
    )
    (net (code "221") (name "unconnected-(U405-AUX_CL-Pad7)") (class "Default")
      (node (ref "U405") (pin "7") (pinfunction "AUX_CL_7") (pintype "bidirectional"))
    )
    (net (code "222") (name "unconnected-(U405-AUX_DA-Pad21)") (class "Default")
      (node (ref "U405") (pin "21") (pinfunction "AUX_DA_21") (pintype "bidirectional"))
    )
    (net (code "223") (name "unconnected-(U405-NC-Pad2)") (class "Default")
      (node (ref "U405") (pin "2") (pinfunction "NC_2") (pintype "bidirectional"))
    )
    (net (code "224") (name "unconnected-(U405-NC-Pad3)") (class "Default")
      (node (ref "U405") (pin "3") (pinfunction "NC_3") (pintype "bidirectional"))
    )
    (net (code "225") (name "unconnected-(U405-NC-Pad4)") (class "Default")
      (node (ref "U405") (pin "4") (pinfunction "NC_4") (pintype "bidirectional"))
    )
    (net (code "226") (name "unconnected-(U405-NC-Pad5)") (class "Default")
      (node (ref "U405") (pin "5") (pinfunction "NC_5") (pintype "bidirectional"))
    )
    (net (code "227") (name "unconnected-(U405-NC-Pad6)") (class "Default")
      (node (ref "U405") (pin "6") (pinfunction "NC_6") (pintype "bidirectional"))
    )
    (net (code "228") (name "unconnected-(U405-NC-Pad14)") (class "Default")
      (node (ref "U405") (pin "14") (pinfunction "NC_14") (pintype "bidirectional"))
    )
    (net (code "229") (name "unconnected-(U405-NC-Pad15)") (class "Default")
      (node (ref "U405") (pin "15") (pinfunction "NC_15") (pintype "bidirectional"))
    )
    (net (code "230") (name "unconnected-(U405-NC-Pad16)") (class "Default")
      (node (ref "U405") (pin "16") (pinfunction "NC_16") (pintype "bidirectional"))
    )
    (net (code "231") (name "unconnected-(U405-NC-Pad17)") (class "Default")
      (node (ref "U405") (pin "17") (pinfunction "NC_17") (pintype "bidirectional"))
    )
    (net (code "232") (name "unconnected-(U405-RESV-Pad19)") (class "Default")
      (node (ref "U405") (pin "19") (pinfunction "RESV_19") (pintype "bidirectional"))
    )
    (net (code "233") (name "unconnected-(U406-DEN_G-Pad10)") (class "Default")
      (node (ref "U406") (pin "10") (pinfunction "DEN_G_10") (pintype "bidirectional"))
    )
    (net (code "234") (name "unconnected-(U406-INT_G-Pad11)") (class "Default")
      (node (ref "U406") (pin "11") (pinfunction "INT_G_11") (pintype "bidirectional"))
    )
    (net (code "235") (name "unconnected-(U406-NC-Pad1)") (class "Default")
      (node (ref "U406") (pin "1") (pinfunction "NC_1") (pintype "bidirectional"))
    )
    (net (code "236") (name "unconnected-(U701-A5-Pad6)") (class "Default")
      (node (ref "U701") (pin "6") (pinfunction "A5_6") (pintype "bidirectional"))
    )
    (net (code "237") (name "unconnected-(U701-A6-Pad7)") (class "Default")
      (node (ref "U701") (pin "7") (pinfunction "A6_7") (pintype "bidirectional"))
    )
    (net (code "238") (name "unconnected-(U701-A7-Pad8)") (class "Default")
      (node (ref "U701") (pin "8") (pinfunction "A7_8") (pintype "bidirectional"))
    )
    (net (code "239") (name "unconnected-(U701-A8-Pad9)") (class "Default")
      (node (ref "U701") (pin "9") (pinfunction "A8_9") (pintype "bidirectional"))
    )
    (net (code "240") (name "unconnected-(U701-B5-Pad15)") (class "Default")
      (node (ref "U701") (pin "15") (pinfunction "B5_15") (pintype "bidirectional"))
    )
    (net (code "241") (name "unconnected-(U701-B6-Pad14)") (class "Default")
      (node (ref "U701") (pin "14") (pinfunction "B6_14") (pintype "bidirectional"))
    )
    (net (code "242") (name "unconnected-(U701-B7-Pad13)") (class "Default")
      (node (ref "U701") (pin "13") (pinfunction "B7_13") (pintype "bidirectional"))
    )
    (net (code "243") (name "unconnected-(U701-B8-Pad12)") (class "Default")
      (node (ref "U701") (pin "12") (pinfunction "B8_12") (pintype "bidirectional"))
    )
    (net (code "244") (name "unconnected-(U802-CSET-Pad6)") (class "Default")
      (node (ref "U802") (pin "6") (pinfunction "CSET_6") (pintype "bidirectional"))
    )
    (net (code "245") (name "unconnected-(U802-POR2-Pad3)") (class "Default")
      (node (ref "U802") (pin "3") (pinfunction "POR2_3") (pintype "bidirectional"))
    )
    (net (code "246") (name "unconnected-(U802-VOUT2-Pad7)") (class "Default")
      (node (ref "U802") (pin "7") (pinfunction "VOUT2_7") (pintype "bidirectional"))
    )
    (net (code "247") (name "~{ACCEL_MAG_CS}") (class "Default")
      (node (ref "U$101") (pin "63") (pinfunction "17_SPI_0_CS0_63") (pintype "passive"))
      (node (ref "U406") (pin "20") (pinfunction "CS_XM_20") (pintype "bidirectional"))
    )
    (net (code "248") (name "~{FRAM_CS}") (class "Default")
      (node (ref "U$101") (pin "12") (pinfunction "PRU0_R30[14]_12_12") (pintype "passive"))
      (node (ref "U102") (pin "1") (pinfunction "~{S}_1") (pintype "bidirectional"))
    )
    (net (code "249") (name "~{GYRO_CS}") (class "Default")
      (node (ref "U$101") (pin "9") (pinfunction "9_GPIO2[5]_9") (pintype "passive"))
      (node (ref "U406") (pin "19") (pinfunction "CS_G_19") (pintype "bidirectional"))
    )
    (net (code "250") (name "~{LED_AMBER}") (class "Default")
      (node (ref "R610") (pin "P$1") (pinfunction "1_P$1") (pintype "passive"))
      (node (ref "U$101") (pin "71") (pinfunction "25_PRU0_R30/31[7]_71") (pintype "passive"))
    )
    (net (code "251") (name "~{LED_BLUE}") (class "Default")
      (node (ref "R612") (pin "P$1") (pinfunction "1_P$1") (pintype "passive"))
      (node (ref "U$101") (pin "61") (pinfunction "15_GPIO1[16]_61") (pintype "passive"))
    )
    (net (code "252") (name "~{LED_SAFETY}") (class "Default")
      (node (ref "R611") (pin "P$2") (pinfunction "2_P$2") (pintype "passive"))
      (node (ref "U$101") (pin "26") (pinfunction "GPIO1[29]_26_26") (pintype "passive"))
    )
    (net (code "253") (name "~{VDD_5V_HIPOWER_OC}") (class "Default")
      (node (ref "R502") (pin "P$1") (pinfunction "1_P$1") (pintype "passive"))
      (node (ref "U$101") (pin "19") (pinfunction "19_GPIO0[22]_19") (pintype "passive"))
      (node (ref "U501") (pin "4") (pinfunction "~{FAULT}_4") (pintype "bidirectional"))
    )
    (net (code "254") (name "~{VDD_5V_PERIPH_EN}") (class "Default")
      (node (ref "R506") (pin "P$1") (pinfunction "1_P$1") (pintype "passive"))
      (node (ref "U$101") (pin "58") (pinfunction "GPIO1[28]_12_58") (pintype "passive"))
      (node (ref "U501") (pin "5") (pinfunction "~{CE}_5") (pintype "bidirectional"))
      (node (ref "U503") (pin "5") (pinfunction "~{CE}_5") (pintype "bidirectional"))
    )
    (net (code "255") (name "~{VDD_5V_PERIPH_OC}") (class "Default")
      (node (ref "R507") (pin "P$1") (pinfunction "1_P$1") (pintype "passive"))
      (node (ref "U$101") (pin "13") (pinfunction "13_GPIO0[23]_13") (pintype "passive"))
      (node (ref "U503") (pin "4") (pinfunction "~{FAULT}_4") (pintype "bidirectional"))
    )
    (net (code "256") (name "~{VDD_SERVO_IN_FAULT}") (class "Default")
      (node (ref "U$101") (pin "18") (pinfunction "GPIO2[1]_18_18") (pintype "passive"))
    )
  )
)
